# DrumidySynth.net
KiCad netlist of a schematic drawn in EAGLE
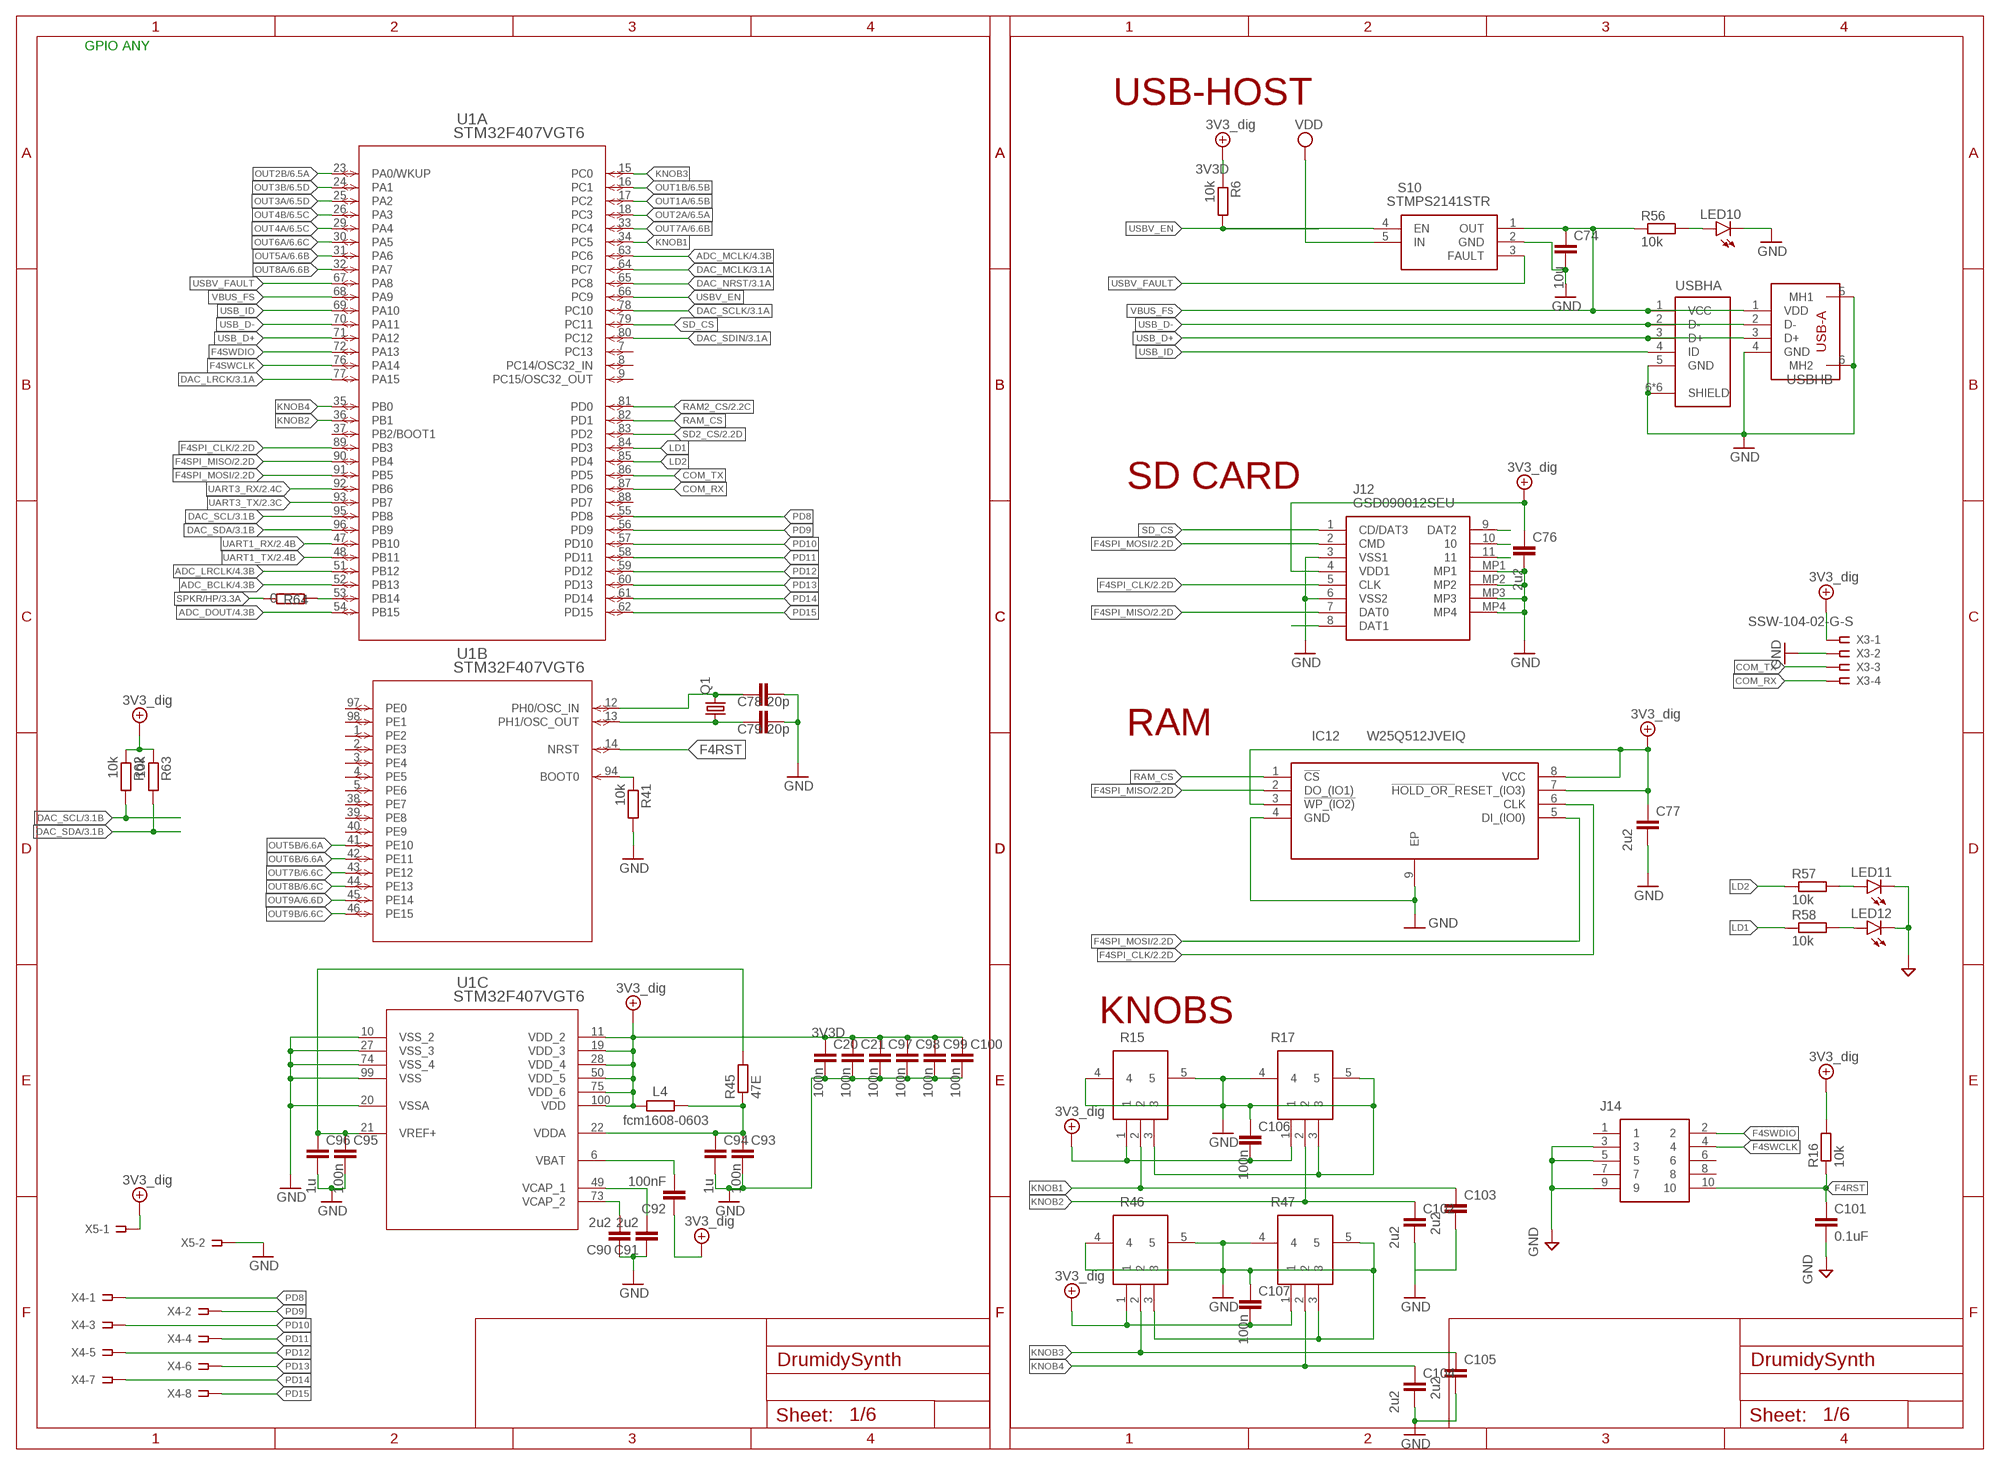
[diagram p0: schematic, sheet 1]
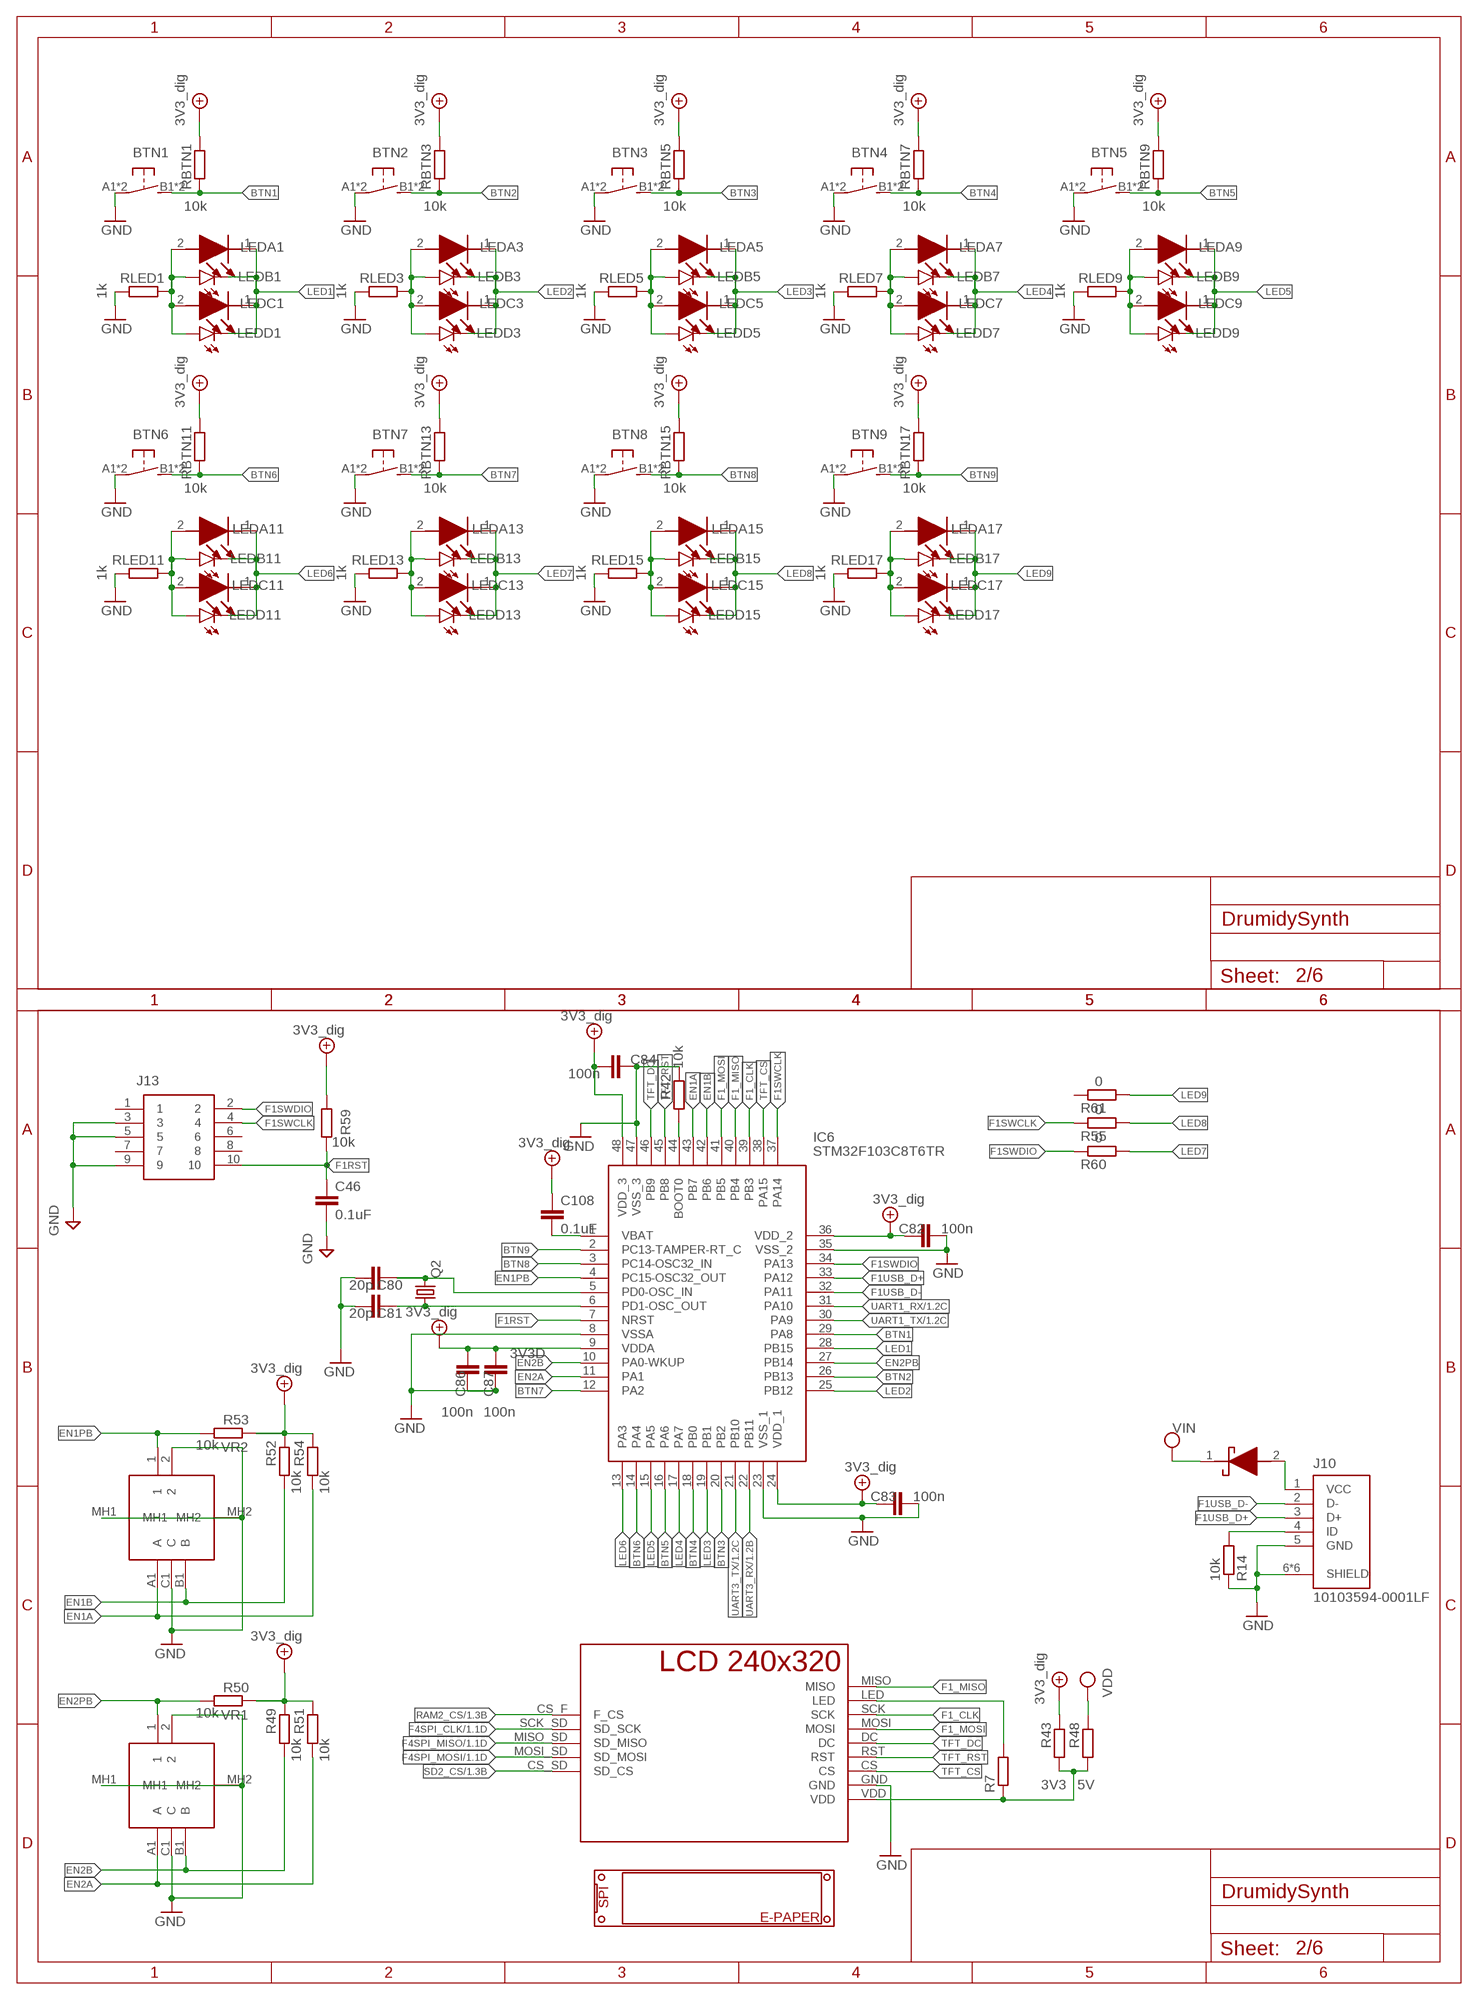
[diagram p1: schematic, sheet 2]
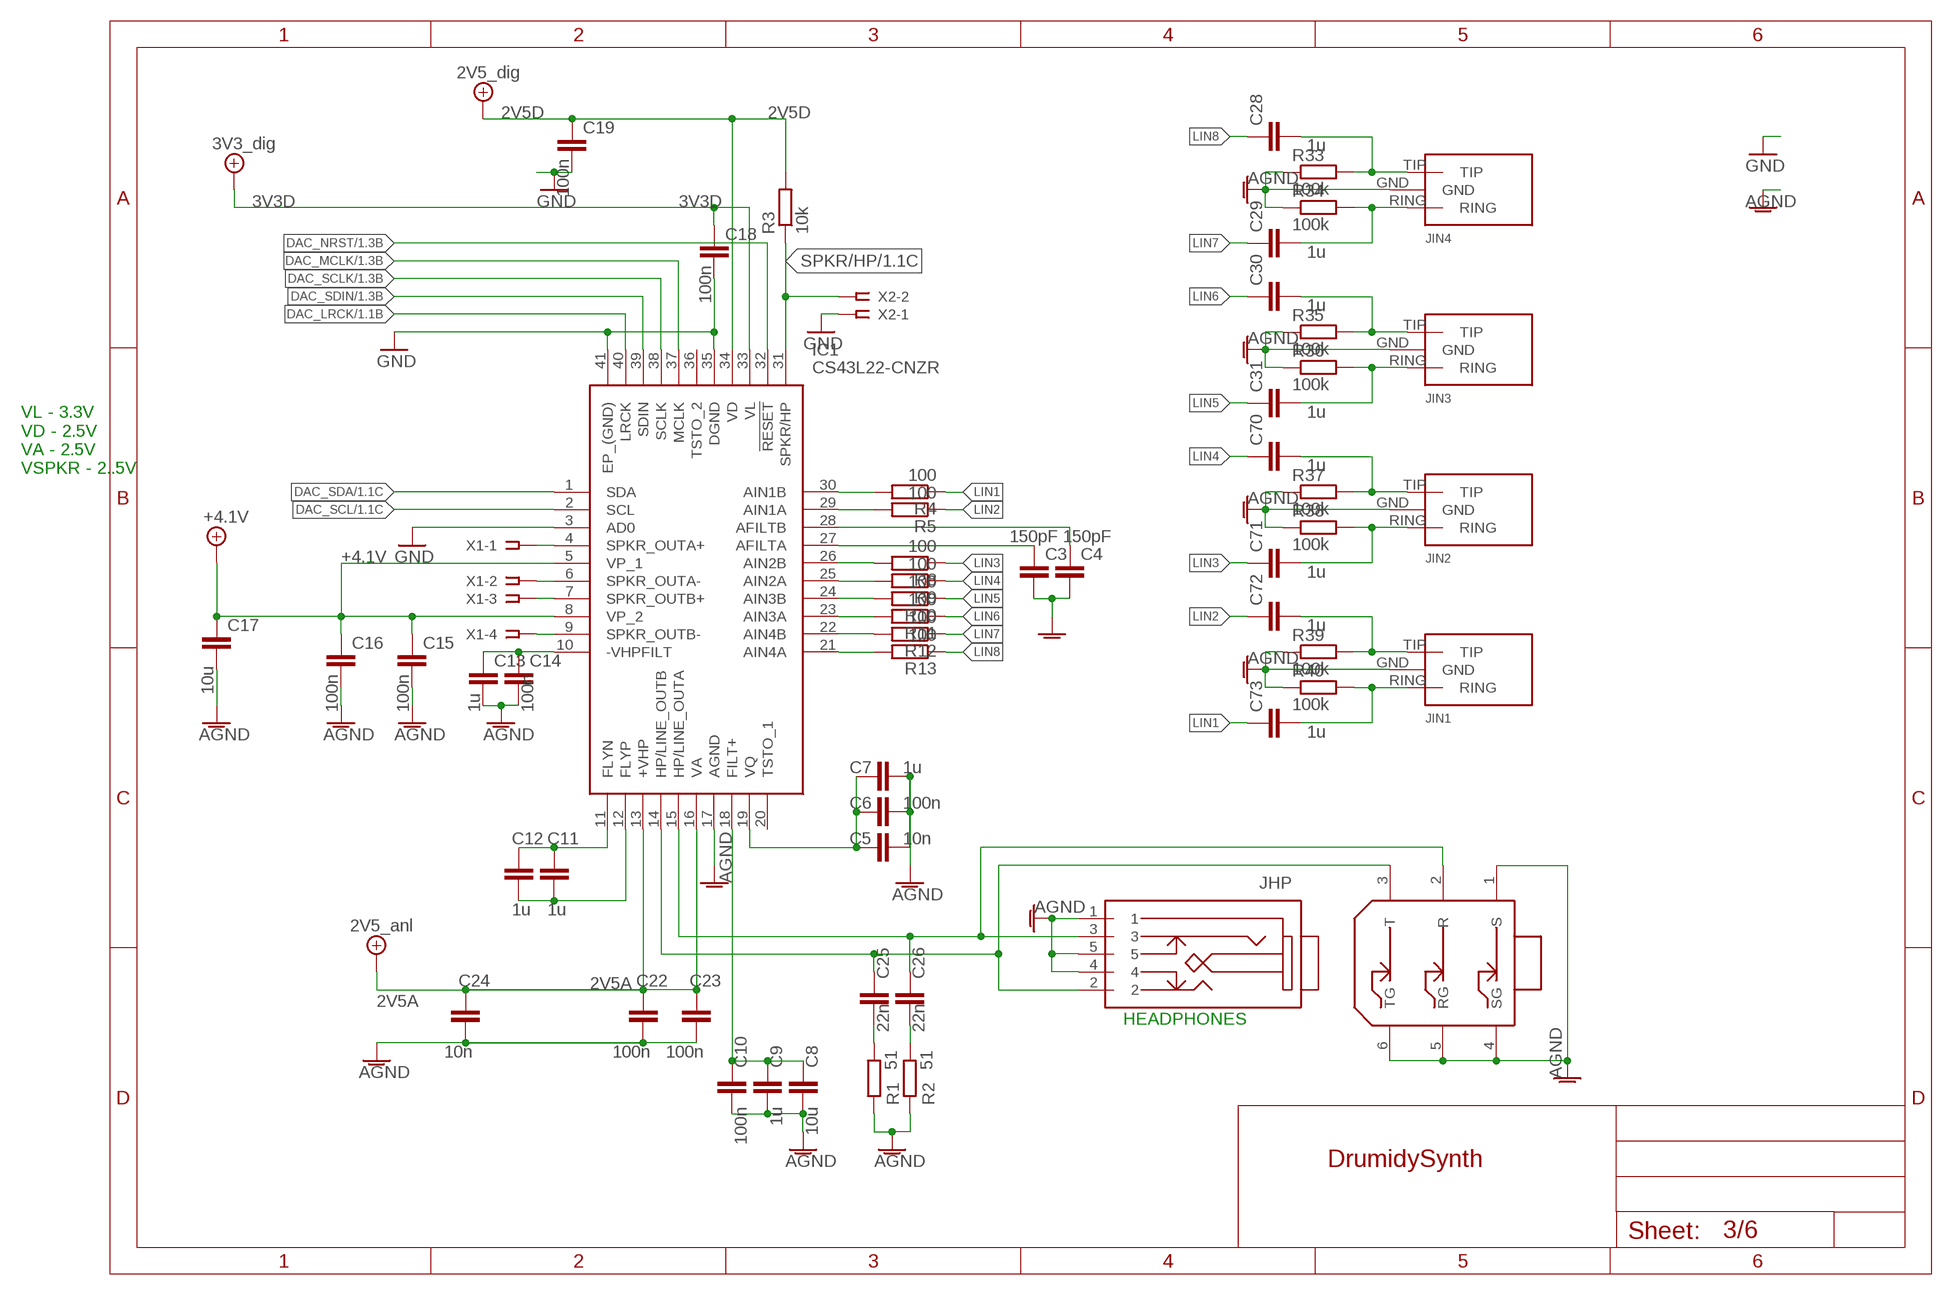
[diagram p2: schematic, sheet 3]
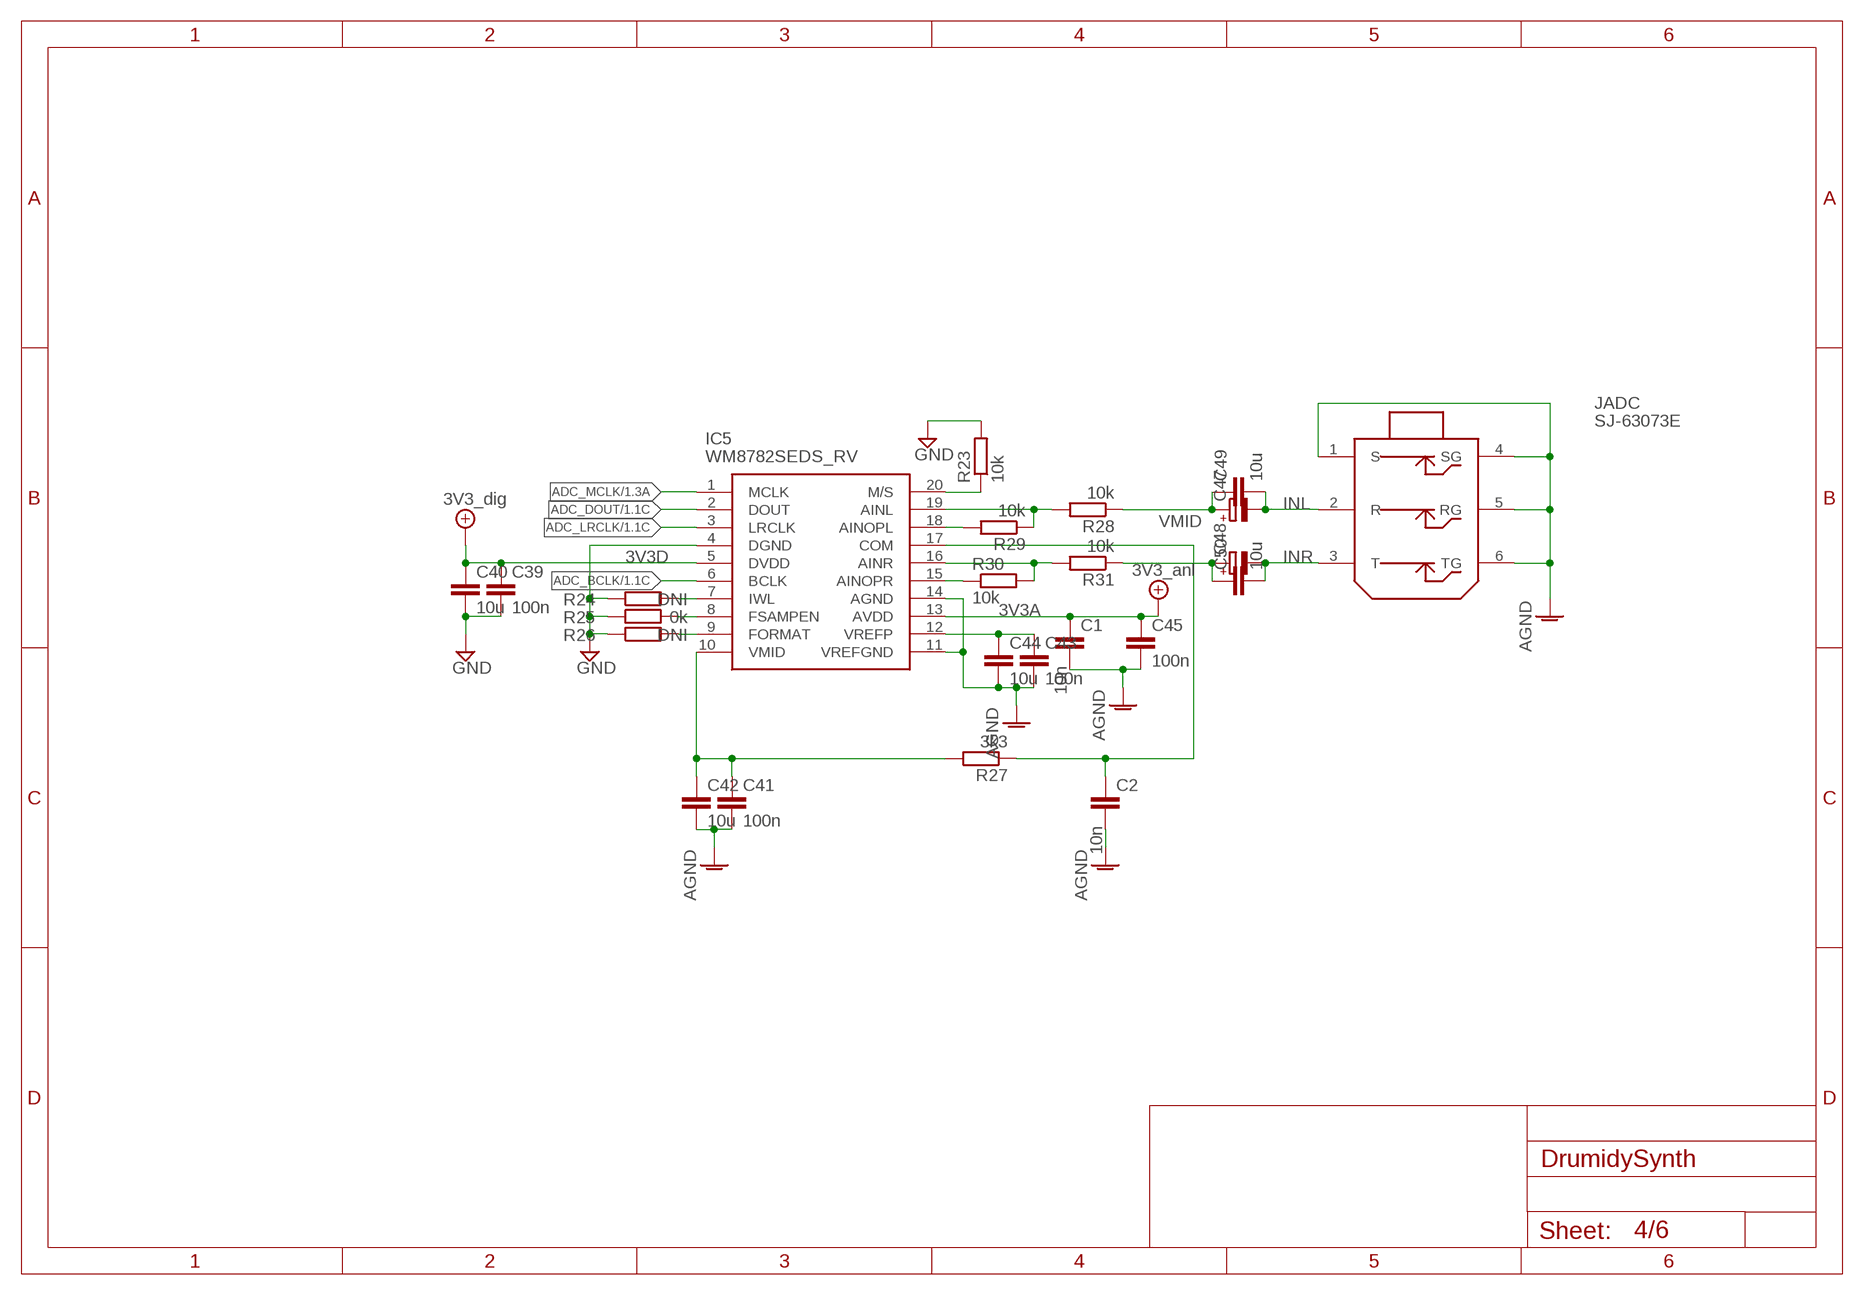
[diagram p3: schematic, sheet 4]
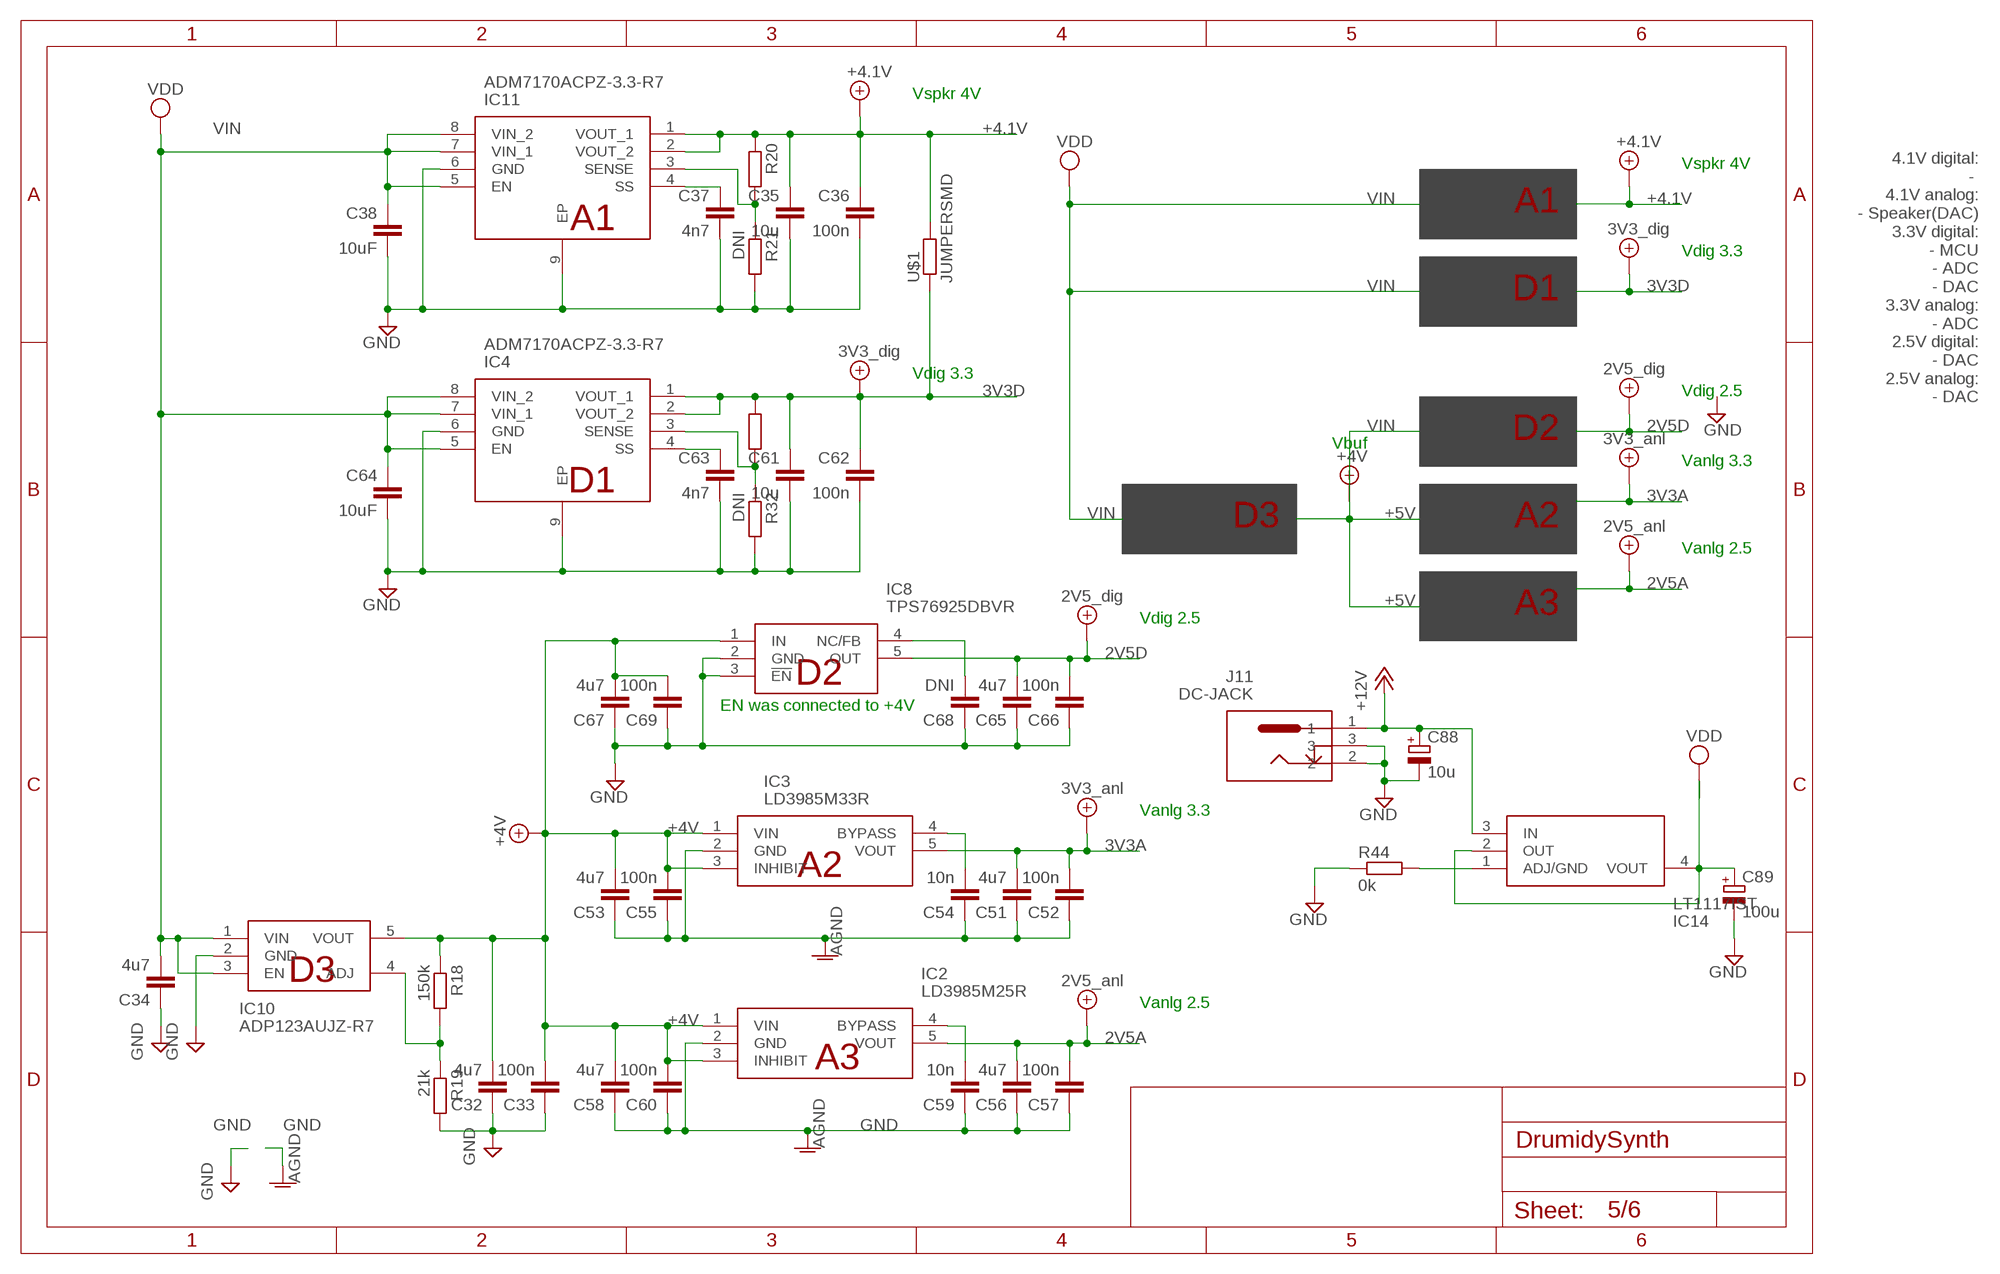
[diagram p4: schematic, sheet 5]
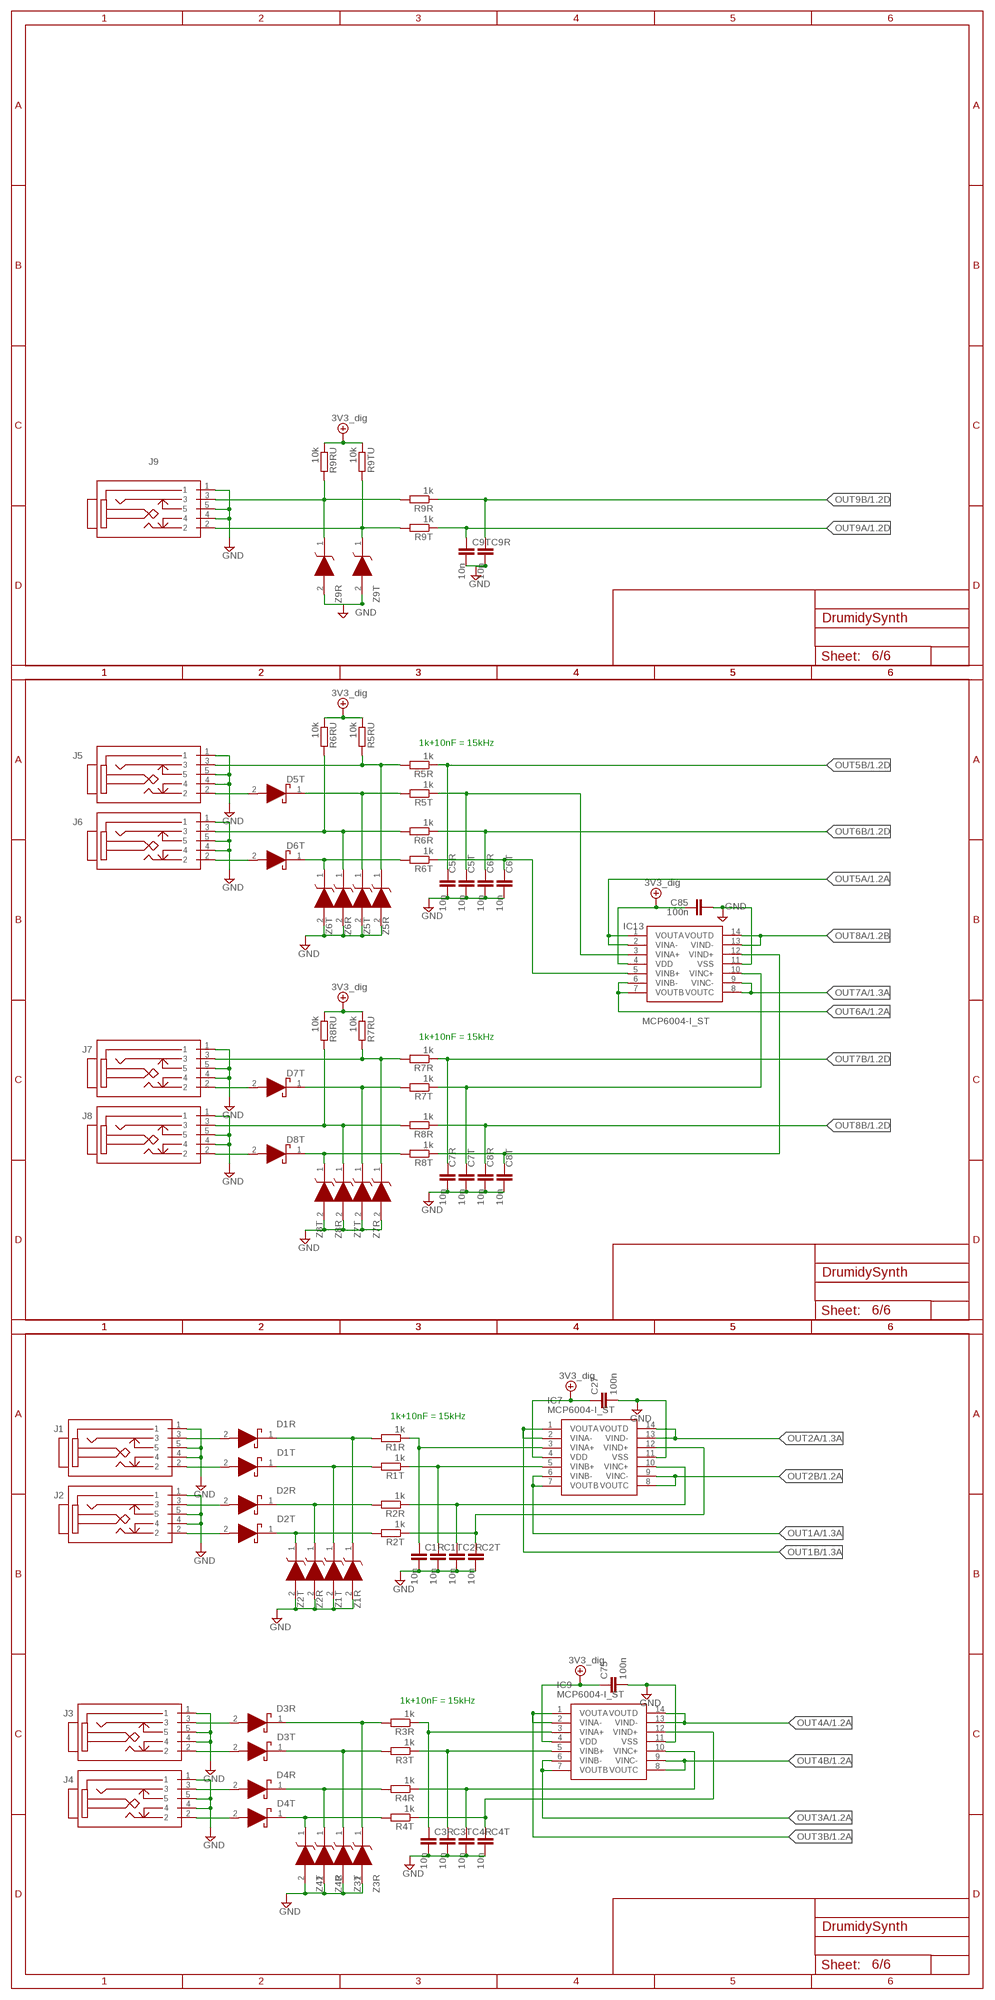
[diagram p5: schematic, sheet 6]

(export (version "E")
  (design (tool "Eeschema 10.0.6"))
  (components
    (comp (ref "C20")
      (value "100n")
      (footprint "eagle-import:C0603K")
      (libsource (lib "eagle-import") (part "C-EUC0603K"))
    )
    (comp (ref "C21")
      (value "100n")
      (footprint "eagle-import:C0603K")
      (libsource (lib "eagle-import") (part "C-EUC0603K"))
    )
    (comp (ref "C74")
      (value "10u")
      (footprint "eagle-import:C0805K")
      (libsource (lib "eagle-import") (part "C-EUC0805K"))
    )
    (comp (ref "C76")
      (value "2u2")
      (footprint "eagle-import:C0805K")
      (libsource (lib "eagle-import") (part "C-EUC0805K"))
    )
    (comp (ref "C77")
      (value "2u2")
      (footprint "eagle-import:C0805K")
      (libsource (lib "eagle-import") (part "C-EUC0805K"))
    )
    (comp (ref "C78")
      (value "20p")
      (footprint "eagle-import:C0402K")
      (libsource (lib "eagle-import") (part "C-EUC0402K"))
    )
    (comp (ref "C79")
      (value "20p")
      (footprint "eagle-import:C0402K")
      (libsource (lib "eagle-import") (part "C-EUC0402K"))
    )
    (comp (ref "C90")
      (value "2u2")
      (footprint "eagle-import:C0603K")
      (libsource (lib "eagle-import") (part "C-EUC0603K"))
    )
    (comp (ref "C91")
      (value "2u2")
      (footprint "eagle-import:C0603K")
      (libsource (lib "eagle-import") (part "C-EUC0603K"))
    )
    (comp (ref "C92")
      (value "100nF")
      (footprint "eagle-import:C0603K")
      (libsource (lib "eagle-import") (part "C-EUC0603K"))
    )
    (comp (ref "C93")
      (value "100n")
      (footprint "eagle-import:C0603K")
      (libsource (lib "eagle-import") (part "C-EUC0603K"))
    )
    (comp (ref "C94")
      (value "1u")
      (footprint "eagle-import:C0805K")
      (libsource (lib "eagle-import") (part "C-EUC0805K"))
    )
    (comp (ref "C95")
      (value "100n")
      (footprint "eagle-import:C0603K")
      (libsource (lib "eagle-import") (part "C-EUC0603K"))
    )
    (comp (ref "C96")
      (value "1u")
      (footprint "eagle-import:C0805K")
      (libsource (lib "eagle-import") (part "C-EUC0805K"))
    )
    (comp (ref "C97")
      (value "100n")
      (footprint "eagle-import:C0603K")
      (libsource (lib "eagle-import") (part "C-EUC0603K"))
    )
    (comp (ref "C98")
      (value "100n")
      (footprint "eagle-import:C0603K")
      (libsource (lib "eagle-import") (part "C-EUC0603K"))
    )
    (comp (ref "C99")
      (value "100n")
      (footprint "eagle-import:C0603K")
      (libsource (lib "eagle-import") (part "C-EUC0603K"))
    )
    (comp (ref "C100")
      (value "100n")
      (footprint "eagle-import:C0603K")
      (libsource (lib "eagle-import") (part "C-EUC0603K"))
    )
    (comp (ref "C101")
      (value "0.1uF")
      (footprint "eagle-import:C0402")
      (libsource (lib "eagle-import") (part "C-EUC0402"))
    )
    (comp (ref "C102")
      (value "2u2")
      (footprint "eagle-import:C0805K")
      (libsource (lib "eagle-import") (part "C-EUC0805K"))
    )
    (comp (ref "C103")
      (value "2u2")
      (footprint "eagle-import:C0805K")
      (libsource (lib "eagle-import") (part "C-EUC0805K"))
    )
    (comp (ref "C104")
      (value "2u2")
      (footprint "eagle-import:C0805K")
      (libsource (lib "eagle-import") (part "C-EUC0805K"))
    )
    (comp (ref "C105")
      (value "2u2")
      (footprint "eagle-import:C0805K")
      (libsource (lib "eagle-import") (part "C-EUC0805K"))
    )
    (comp (ref "C106")
      (value "100n")
      (footprint "eagle-import:C0603K")
      (libsource (lib "eagle-import") (part "C-EUC0603K"))
    )
    (comp (ref "C107")
      (value "100n")
      (footprint "eagle-import:C0603K")
      (libsource (lib "eagle-import") (part "C-EUC0603K"))
    )
    (comp (ref "IC12")
      (value "W25Q512JVEIQ")
      (footprint "eagle-import:SON127P800X600X80-9N")
      (fields (field (name "MOUSER_PART_NUMBER") "454-W25Q512JVEIQ"))
      (libsource (lib "eagle-import") (part "W25Q512JVEIQ"))
    )
    (comp (ref "J12")
      (value "GSD090012SEU")
      (footprint "eagle-import:GSD090012SEU")
      (fields (field (name "RS_PART_NUMBER") "2208512"))
      (libsource (lib "eagle-import") (part "GSD090012SEU"))
    )
    (comp (ref "J14")
      (value "FTSH-105-01-F-DV-K-A-P-TR")
      (footprint "eagle-import:FTSH-105-XX-YYY-DV-K-A-P-TR")
      (fields (field (name "MOUSER_PART_NUMBER") "200-FTSH1051FDVKAPTR"))
      (libsource (lib "eagle-import") (part "FTSH-105-01-F-DV-K-A-P-TR"))
    )
    (comp (ref "L4")
      (value "fcm1608-0603")
      (footprint "eagle-import:R0603")
      (libsource (lib "eagle-import") (part "R-EU_R0603"))
    )
    (comp (ref "LED10")
      (value "LEDCHIP-LED0603")
      (footprint "eagle-import:CHIP-LED0603")
      (libsource (lib "eagle-import") (part "LEDCHIP-LED0603"))
    )
    (comp (ref "LED11")
      (value "LEDCHIP-LED0603")
      (footprint "eagle-import:CHIP-LED0603")
      (libsource (lib "eagle-import") (part "LEDCHIP-LED0603"))
    )
    (comp (ref "LED12")
      (value "LEDCHIP-LED0603")
      (footprint "eagle-import:CHIP-LED0603")
      (libsource (lib "eagle-import") (part "LEDCHIP-LED0603"))
    )
    (comp (ref "Q1")
      (value "CRYSTALHC49S")
      (footprint "eagle-import:HC49_S")
      (libsource (lib "eagle-import") (part "CRYSTALHC49S"))
    )
    (comp (ref "R6")
      (value "10k")
      (footprint "eagle-import:R0603")
      (libsource (lib "eagle-import") (part "R-EU_R0603"))
    )
    (comp (ref "R15")
      (value "PTV09A-4025U-B103")
      (footprint "eagle-import:PTV09A4020FB103")
      (libsource (lib "eagle-import") (part "PTV09A-4025U-B103"))
    )
    (comp (ref "R16")
      (value "10k")
      (footprint "eagle-import:R0603")
      (libsource (lib "eagle-import") (part "R-EU_R0603"))
    )
    (comp (ref "R17")
      (value "PTV09A-4025U-B103")
      (footprint "eagle-import:PTV09A4020FB103")
      (libsource (lib "eagle-import") (part "PTV09A-4025U-B103"))
    )
    (comp (ref "R41")
      (value "10k")
      (footprint "eagle-import:R0603")
      (libsource (lib "eagle-import") (part "R-EU_R0603"))
    )
    (comp (ref "R45")
      (value "47E")
      (footprint "eagle-import:R0603")
      (libsource (lib "eagle-import") (part "R-EU_R0603"))
    )
    (comp (ref "R46")
      (value "PTV09A-4025U-B103")
      (footprint "eagle-import:PTV09A4020FB103")
      (libsource (lib "eagle-import") (part "PTV09A-4025U-B103"))
    )
    (comp (ref "R47")
      (value "PTV09A-4025U-B103")
      (footprint "eagle-import:PTV09A4020FB103")
      (libsource (lib "eagle-import") (part "PTV09A-4025U-B103"))
    )
    (comp (ref "R56")
      (value "10k")
      (footprint "eagle-import:R0603")
      (libsource (lib "eagle-import") (part "R-EU_R0603"))
    )
    (comp (ref "R57")
      (value "10k")
      (footprint "eagle-import:R0603")
      (libsource (lib "eagle-import") (part "R-EU_R0603"))
    )
    (comp (ref "R58")
      (value "10k")
      (footprint "eagle-import:R0603")
      (libsource (lib "eagle-import") (part "R-EU_R0603"))
    )
    (comp (ref "R62")
      (value "10k")
      (footprint "eagle-import:R0603")
      (libsource (lib "eagle-import") (part "R-EU_R0603"))
    )
    (comp (ref "R63")
      (value "10k")
      (footprint "eagle-import:R0603")
      (libsource (lib "eagle-import") (part "R-EU_R0603"))
    )
    (comp (ref "R64")
      (value "0")
      (footprint "eagle-import:R0603")
      (libsource (lib "eagle-import") (part "R-EU_R0603"))
    )
    (comp (ref "S10")
      (value "STMPS2141STR")
      (footprint "eagle-import:SOT95P280X145-5N")
      (fields (field (name "RS_PART_NUMBER") "8805406P"))
      (libsource (lib "eagle-import") (part "STMPS2141STR"))
    )
    (comp (ref "U1")
      (value "STM32F407VGT6")
      (footprint "eagle-import:LQFP100-14X14MM")
      (fields (field (name "COPYRIGHT") "Copyright (C) 2022 Ultra Librarian. All rights reserved."))
      (libsource (lib "eagle-import") (part "STM32F407VGT6"))
    )
    (comp (ref "USBHA")
      (value "10103594-0001LF")
      (footprint "eagle-import:AMPHENOL_10103594-0001LF")
      (fields (field (name "DIGI-KEY_PART_NUMBER") "609-4050-1-ND") (field (name "MF") "Amphenol ICC"))
      (libsource (lib "eagle-import") (part "10103594-0001LF"))
    )
    (comp (ref "USBHB")
      (value "USB-A(292303-7)")
      (footprint "eagle-import:2923037")
      (fields (field (name "MANUFACTURER_PART_NUMBER") "292303-7") (field (name "RS_PART_NUMBER") "9097864"))
      (libsource (lib "eagle-import") (part "USB-A(292303-7)"))
    )
    (comp (ref "X3")
      (value "SSW-104-02-G-S")
      (footprint "eagle-import:SSW-104-02-G-S")
      (fields (field (name "MF") "Samtec Inc."))
      (libsource (lib "eagle-import") (part "SSW-104-02-G-S"))
    )
    (comp (ref "X4")
      (value "SSW-104-02-G-D")
      (footprint "eagle-import:SSW-104-02-G-D")
      (fields (field (name "MF") "Samtec Inc."))
      (libsource (lib "eagle-import") (part "SSW-104-02-G-D"))
    )
    (comp (ref "X5")
      (value "SSW-102-02-G-S")
      (footprint "eagle-import:SSW-102-02-G-S")
      (fields (field (name "MF") "Samtec Inc."))
      (libsource (lib "eagle-import") (part "SSW-102-02-G-S"))
    )
    (comp (ref "C3")
      (value "150pF")
      (footprint "eagle-import:C0402K")
      (libsource (lib "eagle-import") (part "C-EUC0402K"))
    )
    (comp (ref "C4")
      (value "150pF")
      (footprint "eagle-import:C0402K")
      (libsource (lib "eagle-import") (part "C-EUC0402K"))
    )
    (comp (ref "C5")
      (value "10n")
      (footprint "eagle-import:C0402K")
      (libsource (lib "eagle-import") (part "C-EUC0402K"))
    )
    (comp (ref "C6")
      (value "100n")
      (footprint "eagle-import:C0603K")
      (libsource (lib "eagle-import") (part "C-EUC0603K"))
    )
    (comp (ref "C7")
      (value "1u")
      (footprint "eagle-import:C0603K")
      (libsource (lib "eagle-import") (part "C-EUC0603K"))
    )
    (comp (ref "C8")
      (value "10u")
      (footprint "eagle-import:C0805K")
      (libsource (lib "eagle-import") (part "C-EUC0805K"))
    )
    (comp (ref "C9")
      (value "1u")
      (footprint "eagle-import:C0603K")
      (libsource (lib "eagle-import") (part "C-EUC0603K"))
    )
    (comp (ref "C10")
      (value "100n")
      (footprint "eagle-import:C0603K")
      (libsource (lib "eagle-import") (part "C-EUC0603K"))
    )
    (comp (ref "C11")
      (value "1u")
      (footprint "eagle-import:C0603K")
      (libsource (lib "eagle-import") (part "C-EUC0603K"))
    )
    (comp (ref "C12")
      (value "1u")
      (footprint "eagle-import:C0603K")
      (libsource (lib "eagle-import") (part "C-EUC0603K"))
    )
    (comp (ref "C13")
      (value "1u")
      (footprint "eagle-import:C0603K")
      (libsource (lib "eagle-import") (part "C-EUC0603K"))
    )
    (comp (ref "C14")
      (value "100n")
      (footprint "eagle-import:C0603K")
      (libsource (lib "eagle-import") (part "C-EUC0603K"))
    )
    (comp (ref "C15")
      (value "100n")
      (footprint "eagle-import:C0603K")
      (libsource (lib "eagle-import") (part "C-EUC0603K"))
    )
    (comp (ref "C16")
      (value "100n")
      (footprint "eagle-import:C0603K")
      (libsource (lib "eagle-import") (part "C-EUC0603K"))
    )
    (comp (ref "C17")
      (value "10u")
      (footprint "eagle-import:C0805K")
      (libsource (lib "eagle-import") (part "C-EUC0805K"))
    )
    (comp (ref "C18")
      (value "100n")
      (footprint "eagle-import:C0603K")
      (libsource (lib "eagle-import") (part "C-EUC0603K"))
    )
    (comp (ref "C19")
      (value "100n")
      (footprint "eagle-import:C0603K")
      (libsource (lib "eagle-import") (part "C-EUC0603K"))
    )
    (comp (ref "C22")
      (value "100n")
      (footprint "eagle-import:C0603K")
      (libsource (lib "eagle-import") (part "C-EUC0603K"))
    )
    (comp (ref "C23")
      (value "100n")
      (footprint "eagle-import:C0603K")
      (libsource (lib "eagle-import") (part "C-EUC0603K"))
    )
    (comp (ref "C24")
      (value "10n")
      (footprint "eagle-import:C0402K")
      (libsource (lib "eagle-import") (part "C-EUC0402K"))
    )
    (comp (ref "C25")
      (value "22n")
      (footprint "eagle-import:C0603K")
      (libsource (lib "eagle-import") (part "C-EUC0603K"))
    )
    (comp (ref "C26")
      (value "22n")
      (footprint "eagle-import:C0603K")
      (libsource (lib "eagle-import") (part "C-EUC0603K"))
    )
    (comp (ref "C28")
      (value "1u")
      (footprint "eagle-import:C0603K")
      (libsource (lib "eagle-import") (part "C-EUC0603K"))
    )
    (comp (ref "C29")
      (value "1u")
      (footprint "eagle-import:C0603K")
      (libsource (lib "eagle-import") (part "C-EUC0603K"))
    )
    (comp (ref "C30")
      (value "1u")
      (footprint "eagle-import:C0603K")
      (libsource (lib "eagle-import") (part "C-EUC0603K"))
    )
    (comp (ref "C31")
      (value "1u")
      (footprint "eagle-import:C0603K")
      (libsource (lib "eagle-import") (part "C-EUC0603K"))
    )
    (comp (ref "C70")
      (value "1u")
      (footprint "eagle-import:C0603K")
      (libsource (lib "eagle-import") (part "C-EUC0603K"))
    )
    (comp (ref "C71")
      (value "1u")
      (footprint "eagle-import:C0603K")
      (libsource (lib "eagle-import") (part "C-EUC0603K"))
    )
    (comp (ref "C72")
      (value "1u")
      (footprint "eagle-import:C0603K")
      (libsource (lib "eagle-import") (part "C-EUC0603K"))
    )
    (comp (ref "C73")
      (value "1u")
      (footprint "eagle-import:C0603K")
      (libsource (lib "eagle-import") (part "C-EUC0603K"))
    )
    (comp (ref "IC1")
      (value "CS43L22-CNZR")
      (footprint "eagle-import:QFN50P600X600X100-41N")
      (libsource (lib "eagle-import") (part "CS43L22-CNZR"))
    )
    (comp (ref "JHP")
      (value "35RAPC2AVN4")
      (footprint "eagle-import:35RAPC2AVN4")
      (libsource (lib "eagle-import") (part "35RAPC2AVN4"))
    )
    (comp (ref "JIN1")
      (value "JACK35VERT")
      (footprint "eagle-import:JACK35VERT")
      (libsource (lib "eagle-import") (part "JACK35VERT"))
    )
    (comp (ref "JIN2")
      (value "JACK35VERT")
      (footprint "eagle-import:JACK35VERT")
      (libsource (lib "eagle-import") (part "JACK35VERT"))
    )
    (comp (ref "JIN3")
      (value "JACK35VERT")
      (footprint "eagle-import:JACK35VERT")
      (libsource (lib "eagle-import") (part "JACK35VERT"))
    )
    (comp (ref "JIN4")
      (value "JACK35VERT")
      (footprint "eagle-import:JACK35VERT")
      (libsource (lib "eagle-import") (part "JACK35VERT"))
    )
    (comp (ref "JOUT")
      (value "SJ-63073E")
      (footprint "eagle-import:SJ63073E")
      (fields (field (name "MOUSER_PART_NUMBER") "490-SJ-63073E"))
      (libsource (lib "eagle-import") (part "SJ-63073E"))
    )
    (comp (ref "R1")
      (value "51")
      (footprint "eagle-import:R0603")
      (libsource (lib "eagle-import") (part "R-EU_R0603"))
    )
    (comp (ref "R2")
      (value "51")
      (footprint "eagle-import:R0603")
      (libsource (lib "eagle-import") (part "R-EU_R0603"))
    )
    (comp (ref "R3")
      (value "10k")
      (footprint "eagle-import:R0603")
      (libsource (lib "eagle-import") (part "R-EU_R0603"))
    )
    (comp (ref "R4")
      (value "100")
      (footprint "eagle-import:R0603")
      (libsource (lib "eagle-import") (part "R-EU_R0603"))
    )
    (comp (ref "R5")
      (value "100")
      (footprint "eagle-import:R0603")
      (libsource (lib "eagle-import") (part "R-EU_R0603"))
    )
    (comp (ref "R8")
      (value "100")
      (footprint "eagle-import:R0603")
      (libsource (lib "eagle-import") (part "R-EU_R0603"))
    )
    (comp (ref "R9")
      (value "100")
      (footprint "eagle-import:R0603")
      (libsource (lib "eagle-import") (part "R-EU_R0603"))
    )
    (comp (ref "R10")
      (value "100")
      (footprint "eagle-import:R0603")
      (libsource (lib "eagle-import") (part "R-EU_R0603"))
    )
    (comp (ref "R11")
      (value "100")
      (footprint "eagle-import:R0603")
      (libsource (lib "eagle-import") (part "R-EU_R0603"))
    )
    (comp (ref "R12")
      (value "100")
      (footprint "eagle-import:R0603")
      (libsource (lib "eagle-import") (part "R-EU_R0603"))
    )
    (comp (ref "R13")
      (value "100")
      (footprint "eagle-import:R0603")
      (libsource (lib "eagle-import") (part "R-EU_R0603"))
    )
    (comp (ref "R33")
      (value "100k")
      (footprint "eagle-import:R0603")
      (libsource (lib "eagle-import") (part "R-EU_R0603"))
    )
    (comp (ref "R34")
      (value "100k")
      (footprint "eagle-import:R0603")
      (libsource (lib "eagle-import") (part "R-EU_R0603"))
    )
    (comp (ref "R35")
      (value "100k")
      (footprint "eagle-import:R0603")
      (libsource (lib "eagle-import") (part "R-EU_R0603"))
    )
    (comp (ref "R36")
      (value "100k")
      (footprint "eagle-import:R0603")
      (libsource (lib "eagle-import") (part "R-EU_R0603"))
    )
    (comp (ref "R37")
      (value "100k")
      (footprint "eagle-import:R0603")
      (libsource (lib "eagle-import") (part "R-EU_R0603"))
    )
    (comp (ref "R38")
      (value "100k")
      (footprint "eagle-import:R0603")
      (libsource (lib "eagle-import") (part "R-EU_R0603"))
    )
    (comp (ref "R39")
      (value "100k")
      (footprint "eagle-import:R0603")
      (libsource (lib "eagle-import") (part "R-EU_R0603"))
    )
    (comp (ref "R40")
      (value "100k")
      (footprint "eagle-import:R0603")
      (libsource (lib "eagle-import") (part "R-EU_R0603"))
    )
    (comp (ref "X1")
      (value "SSW-104-02-G-S")
      (footprint "eagle-import:SSW-104-02-G-S")
      (fields (field (name "MF") "Samtec Inc."))
      (libsource (lib "eagle-import") (part "SSW-104-02-G-S"))
    )
    (comp (ref "X2")
      (value "SSW-102-02-G-S")
      (footprint "eagle-import:SSW-102-02-G-S")
      (fields (field (name "MF") "Samtec Inc."))
      (libsource (lib "eagle-import") (part "SSW-102-02-G-S"))
    )
    (comp (ref "C32")
      (value "4u7")
      (footprint "eagle-import:C0603K")
      (libsource (lib "eagle-import") (part "C-EUC0603K"))
    )
    (comp (ref "C33")
      (value "100n")
      (footprint "eagle-import:C0402")
      (libsource (lib "eagle-import") (part "C-EUC0402"))
    )
    (comp (ref "C34")
      (value "4u7")
      (footprint "eagle-import:C0603K")
      (libsource (lib "eagle-import") (part "C-EUC0603K"))
    )
    (comp (ref "C35")
      (value "10u")
      (footprint "eagle-import:C0603")
      (libsource (lib "eagle-import") (part "C-EUC0603"))
    )
    (comp (ref "C36")
      (value "100n")
      (footprint "eagle-import:C0402K")
      (libsource (lib "eagle-import") (part "C-EUC0402K"))
    )
    (comp (ref "C37")
      (value "4n7")
      (footprint "eagle-import:C0402K")
      (libsource (lib "eagle-import") (part "C-EUC0402K"))
    )
    (comp (ref "C38")
      (value "10uF")
      (footprint "eagle-import:C0603")
      (libsource (lib "eagle-import") (part "C-EUC0603"))
    )
    (comp (ref "C51")
      (value "4u7")
      (footprint "eagle-import:C0603K")
      (libsource (lib "eagle-import") (part "C-EUC0603K"))
    )
    (comp (ref "C52")
      (value "100n")
      (footprint "eagle-import:C0402")
      (libsource (lib "eagle-import") (part "C-EUC0402"))
    )
    (comp (ref "C53")
      (value "4u7")
      (footprint "eagle-import:C0603K")
      (libsource (lib "eagle-import") (part "C-EUC0603K"))
    )
    (comp (ref "C54")
      (value "10n")
      (footprint "eagle-import:C0402K")
      (libsource (lib "eagle-import") (part "C-EUC0402K"))
    )
    (comp (ref "C55")
      (value "100n")
      (footprint "eagle-import:C0402")
      (libsource (lib "eagle-import") (part "C-EUC0402"))
    )
    (comp (ref "C56")
      (value "4u7")
      (footprint "eagle-import:C0603K")
      (libsource (lib "eagle-import") (part "C-EUC0603K"))
    )
    (comp (ref "C57")
      (value "100n")
      (footprint "eagle-import:C0402")
      (libsource (lib "eagle-import") (part "C-EUC0402"))
    )
    (comp (ref "C58")
      (value "4u7")
      (footprint "eagle-import:C0603K")
      (libsource (lib "eagle-import") (part "C-EUC0603K"))
    )
    (comp (ref "C59")
      (value "10n")
      (footprint "eagle-import:C0402K")
      (libsource (lib "eagle-import") (part "C-EUC0402K"))
    )
    (comp (ref "C60")
      (value "100n")
      (footprint "eagle-import:C0402")
      (libsource (lib "eagle-import") (part "C-EUC0402"))
    )
    (comp (ref "C61")
      (value "10u")
      (footprint "eagle-import:C0603")
      (libsource (lib "eagle-import") (part "C-EUC0603"))
    )
    (comp (ref "C62")
      (value "100n")
      (footprint "eagle-import:C0402K")
      (libsource (lib "eagle-import") (part "C-EUC0402K"))
    )
    (comp (ref "C63")
      (value "4n7")
      (footprint "eagle-import:C0402K")
      (libsource (lib "eagle-import") (part "C-EUC0402K"))
    )
    (comp (ref "C64")
      (value "10uF")
      (footprint "eagle-import:C0603")
      (libsource (lib "eagle-import") (part "C-EUC0603"))
    )
    (comp (ref "C65")
      (value "4u7")
      (footprint "eagle-import:C0603K")
      (libsource (lib "eagle-import") (part "C-EUC0603K"))
    )
    (comp (ref "C66")
      (value "100n")
      (footprint "eagle-import:C0402")
      (libsource (lib "eagle-import") (part "C-EUC0402"))
    )
    (comp (ref "C67")
      (value "4u7")
      (footprint "eagle-import:C0603K")
      (libsource (lib "eagle-import") (part "C-EUC0603K"))
    )
    (comp (ref "C68")
      (value "DNI")
      (footprint "eagle-import:C0402K")
      (libsource (lib "eagle-import") (part "C-EUC0402K"))
    )
    (comp (ref "C69")
      (value "100n")
      (footprint "eagle-import:C0402")
      (libsource (lib "eagle-import") (part "C-EUC0402"))
    )
    (comp (ref "C88")
      (value "10u")
      (footprint "eagle-import:E2,5-6")
      (libsource (lib "eagle-import") (part "CPOL-EUE2.5-6"))
    )
    (comp (ref "C89")
      (value "100u")
      (footprint "eagle-import:E2,5-6")
      (libsource (lib "eagle-import") (part "CPOL-EUE2.5-6"))
    )
    (comp (ref "IC2")
      (value "LD3985M25R")
      (footprint "eagle-import:SOT95P280X145-5N")
      (fields (field (name "RS_PART_NUMBER") "6868809P"))
      (libsource (lib "eagle-import") (part "LD3985M25R"))
    )
    (comp (ref "IC3")
      (value "LD3985M33R")
      (footprint "eagle-import:SOT95P280X145-5N")
      (fields (field (name "RS_PART_NUMBER") "6868802P"))
      (libsource (lib "eagle-import") (part "LD3985M33R"))
    )
    (comp (ref "IC4")
      (value "ADM7170ACPZ-3.3-R7")
      (footprint "eagle-import:SON50P300X300X80-9N")
      (fields (field (name "MOUSER_PART_NUMBER") "584-ADM7170ACPZ3.3R7"))
      (libsource (lib "eagle-import") (part "ADM7170ACPZ-3.3-R7"))
    )
    (comp (ref "IC8")
      (value "TPS76925DBVR")
      (footprint "eagle-import:SOT95P280X145-5N")
      (libsource (lib "eagle-import") (part "TPS76925DBVR"))
    )
    (comp (ref "IC10")
      (value "ADP123AUJZ-R7")
      (footprint "eagle-import:SOT95P280X100-5N")
      (fields (field (name "MOUSER_PART_NUMBER") "584-ADP123AUJZ-R7"))
      (libsource (lib "eagle-import") (part "ADP123AUJZ-R7"))
    )
    (comp (ref "IC11")
      (value "ADM7170ACPZ-3.3-R7")
      (footprint "eagle-import:SON50P300X300X80-9N")
      (fields (field (name "MOUSER_PART_NUMBER") "584-ADM7170ACPZ3.3R7"))
      (libsource (lib "eagle-import") (part "ADM7170ACPZ-3.3-R7"))
    )
    (comp (ref "IC14")
      (value "LT1117IST")
      (footprint "eagle-import:SOT230P700X180-4N")
      (fields
        (field (name "MANUFACTURER_PART_NUMBER") "LT1117IST-5#PBF")
        (field (name "RS_PART_NUMBER") "8846936P")
      )
      (libsource (lib "eagle-import") (part "LT1117IST"))
    )
    (comp (ref "J11")
      (value "DC-JACK")
      (footprint "eagle-import:PRT00119")
      (fields (field (name "MANUFACTURER_PART_NUMBER") "PRT-00119"))
      (libsource (lib "eagle-import") (part "DC-JACK"))
    )
    (comp (ref "R18")
      (value "150k")
      (footprint "eagle-import:R0603")
      (libsource (lib "eagle-import") (part "R-EU_R0603"))
    )
    (comp (ref "R19")
      (value "21k")
      (footprint "eagle-import:R0603")
      (libsource (lib "eagle-import") (part "R-EU_R0603"))
    )
    (comp (ref "R20")
      (value "0k")
      (footprint "eagle-import:R0603")
      (libsource (lib "eagle-import") (part "R-EU_R0603"))
    )
    (comp (ref "R21")
      (value "DNI")
      (footprint "eagle-import:R0603")
      (libsource (lib "eagle-import") (part "R-EU_R0603"))
    )
    (comp (ref "R22")
      (value "0k")
      (footprint "eagle-import:R0603")
      (libsource (lib "eagle-import") (part "R-EU_R0603"))
    )
    (comp (ref "R32")
      (value "DNI")
      (footprint "eagle-import:R0603")
      (libsource (lib "eagle-import") (part "R-EU_R0603"))
    )
    (comp (ref "R44")
      (value "0k")
      (footprint "eagle-import:R0603")
      (libsource (lib "eagle-import") (part "R-EU_R0603"))
    )
    (comp (ref "U$1")
      (value "JUMPERSMD")
      (footprint "eagle-import:JUMPERWIDE")
      (libsource (lib "eagle-import") (part "JUMPERSMD"))
    )
    (comp (ref "C1R")
      (value "10n")
      (footprint "eagle-import:C0603K")
      (libsource (lib "eagle-import") (part "C-EUC0603K"))
    )
    (comp (ref "C1T")
      (value "10n")
      (footprint "eagle-import:C0603K")
      (libsource (lib "eagle-import") (part "C-EUC0603K"))
    )
    (comp (ref "C2R")
      (value "10n")
      (footprint "eagle-import:C0603K")
      (libsource (lib "eagle-import") (part "C-EUC0603K"))
    )
    (comp (ref "C2T")
      (value "10n")
      (footprint "eagle-import:C0603K")
      (libsource (lib "eagle-import") (part "C-EUC0603K"))
    )
    (comp (ref "C3R")
      (value "10n")
      (footprint "eagle-import:C0603K")
      (libsource (lib "eagle-import") (part "C-EUC0603K"))
    )
    (comp (ref "C3T")
      (value "10n")
      (footprint "eagle-import:C0603K")
      (libsource (lib "eagle-import") (part "C-EUC0603K"))
    )
    (comp (ref "C4R")
      (value "10n")
      (footprint "eagle-import:C0603K")
      (libsource (lib "eagle-import") (part "C-EUC0603K"))
    )
    (comp (ref "C4T")
      (value "10n")
      (footprint "eagle-import:C0603K")
      (libsource (lib "eagle-import") (part "C-EUC0603K"))
    )
    (comp (ref "C5R")
      (value "10n")
      (footprint "eagle-import:C0603K")
      (libsource (lib "eagle-import") (part "C-EUC0603K"))
    )
    (comp (ref "C5T")
      (value "10n")
      (footprint "eagle-import:C0603K")
      (libsource (lib "eagle-import") (part "C-EUC0603K"))
    )
    (comp (ref "C6R")
      (value "10n")
      (footprint "eagle-import:C0603K")
      (libsource (lib "eagle-import") (part "C-EUC0603K"))
    )
    (comp (ref "C6T")
      (value "10n")
      (footprint "eagle-import:C0603K")
      (libsource (lib "eagle-import") (part "C-EUC0603K"))
    )
    (comp (ref "C7R")
      (value "10n")
      (footprint "eagle-import:C0603K")
      (libsource (lib "eagle-import") (part "C-EUC0603K"))
    )
    (comp (ref "C7T")
      (value "10n")
      (footprint "eagle-import:C0603K")
      (libsource (lib "eagle-import") (part "C-EUC0603K"))
    )
    (comp (ref "C8R")
      (value "10n")
      (footprint "eagle-import:C0603K")
      (libsource (lib "eagle-import") (part "C-EUC0603K"))
    )
    (comp (ref "C8T")
      (value "10n")
      (footprint "eagle-import:C0603K")
      (libsource (lib "eagle-import") (part "C-EUC0603K"))
    )
    (comp (ref "C9R")
      (value "10n")
      (footprint "eagle-import:C0603K")
      (libsource (lib "eagle-import") (part "C-EUC0603K"))
    )
    (comp (ref "C9T")
      (value "10n")
      (footprint "eagle-import:C0603K")
      (libsource (lib "eagle-import") (part "C-EUC0603K"))
    )
    (comp (ref "C27")
      (value "100n")
      (footprint "eagle-import:C0805")
      (libsource (lib "eagle-import") (part "C-EUC0805"))
    )
    (comp (ref "C75")
      (value "100n")
      (footprint "eagle-import:C0805")
      (libsource (lib "eagle-import") (part "C-EUC0805"))
    )
    (comp (ref "C85")
      (value "100n")
      (footprint "eagle-import:C0805")
      (libsource (lib "eagle-import") (part "C-EUC0805"))
    )
    (comp (ref "D1R")
      (value "BAT54J,115")
      (footprint "eagle-import:SODFL2512X80N")
      (fields (field (name "RS_PART_NUMBER") "7805363P"))
      (libsource (lib "eagle-import") (part "BAT54J,115"))
    )
    (comp (ref "D1T")
      (value "BAT54J,115")
      (footprint "eagle-import:SODFL2512X80N")
      (fields (field (name "RS_PART_NUMBER") "7805363P"))
      (libsource (lib "eagle-import") (part "BAT54J,115"))
    )
    (comp (ref "D2R")
      (value "BAT54J,115")
      (footprint "eagle-import:SODFL2512X80N")
      (fields (field (name "RS_PART_NUMBER") "7805363P"))
      (libsource (lib "eagle-import") (part "BAT54J,115"))
    )
    (comp (ref "D2T")
      (value "BAT54J,115")
      (footprint "eagle-import:SODFL2512X80N")
      (fields (field (name "RS_PART_NUMBER") "7805363P"))
      (libsource (lib "eagle-import") (part "BAT54J,115"))
    )
    (comp (ref "D3R")
      (value "BAT54J,115")
      (footprint "eagle-import:SODFL2512X80N")
      (fields (field (name "RS_PART_NUMBER") "7805363P"))
      (libsource (lib "eagle-import") (part "BAT54J,115"))
    )
    (comp (ref "D3T")
      (value "BAT54J,115")
      (footprint "eagle-import:SODFL2512X80N")
      (fields (field (name "RS_PART_NUMBER") "7805363P"))
      (libsource (lib "eagle-import") (part "BAT54J,115"))
    )
    (comp (ref "D4R")
      (value "BAT54J,115")
      (footprint "eagle-import:SODFL2512X80N")
      (fields (field (name "RS_PART_NUMBER") "7805363P"))
      (libsource (lib "eagle-import") (part "BAT54J,115"))
    )
    (comp (ref "D4T")
      (value "BAT54J,115")
      (footprint "eagle-import:SODFL2512X80N")
      (fields (field (name "RS_PART_NUMBER") "7805363P"))
      (libsource (lib "eagle-import") (part "BAT54J,115"))
    )
    (comp (ref "D5T")
      (value "BAT54J,115")
      (footprint "eagle-import:SODFL2512X80N")
      (fields (field (name "RS_PART_NUMBER") "7805363P"))
      (libsource (lib "eagle-import") (part "BAT54J,115"))
    )
    (comp (ref "D6T")
      (value "BAT54J,115")
      (footprint "eagle-import:SODFL2512X80N")
      (fields (field (name "RS_PART_NUMBER") "7805363P"))
      (libsource (lib "eagle-import") (part "BAT54J,115"))
    )
    (comp (ref "D7T")
      (value "BAT54J,115")
      (footprint "eagle-import:SODFL2512X80N")
      (fields (field (name "RS_PART_NUMBER") "7805363P"))
      (libsource (lib "eagle-import") (part "BAT54J,115"))
    )
    (comp (ref "D8T")
      (value "BAT54J,115")
      (footprint "eagle-import:SODFL2512X80N")
      (fields (field (name "RS_PART_NUMBER") "7805363P"))
      (libsource (lib "eagle-import") (part "BAT54J,115"))
    )
    (comp (ref "IC7")
      (value "MCP6004-I_ST")
      (footprint "eagle-import:SOP65P640X120-14N")
      (fields
        (field (name "ARROW_PART_NUMBER") "MCP6004-I/ST")
        (field (name "MOUSER_PART_NUMBER") "579-MCP6004-I/ST")
      )
      (libsource (lib "eagle-import") (part "MCP6004-I_ST"))
    )
    (comp (ref "IC9")
      (value "MCP6004-I_ST")
      (footprint "eagle-import:SOP65P640X120-14N")
      (fields
        (field (name "ARROW_PART_NUMBER") "MCP6004-I/ST")
        (field (name "MOUSER_PART_NUMBER") "579-MCP6004-I/ST")
      )
      (libsource (lib "eagle-import") (part "MCP6004-I_ST"))
    )
    (comp (ref "IC13")
      (value "MCP6004-I_ST")
      (footprint "eagle-import:SOP65P640X120-14N")
      (fields
        (field (name "ARROW_PART_NUMBER") "MCP6004-I/ST")
        (field (name "MOUSER_PART_NUMBER") "579-MCP6004-I/ST")
      )
      (libsource (lib "eagle-import") (part "MCP6004-I_ST"))
    )
    (comp (ref "J1")
      (value "35RAPC2AVN4")
      (footprint "eagle-import:35RAPC2AVN4")
      (libsource (lib "eagle-import") (part "35RAPC2AVN4"))
    )
    (comp (ref "J2")
      (value "35RAPC2AVN4")
      (footprint "eagle-import:35RAPC2AVN4")
      (libsource (lib "eagle-import") (part "35RAPC2AVN4"))
    )
    (comp (ref "J3")
      (value "35RAPC2AVN4")
      (footprint "eagle-import:35RAPC2AVN4")
      (libsource (lib "eagle-import") (part "35RAPC2AVN4"))
    )
    (comp (ref "J4")
      (value "35RAPC2AVN4")
      (footprint "eagle-import:35RAPC2AVN4")
      (libsource (lib "eagle-import") (part "35RAPC2AVN4"))
    )
    (comp (ref "J5")
      (value "35RAPC2AVN4")
      (footprint "eagle-import:35RAPC2AVN4")
      (libsource (lib "eagle-import") (part "35RAPC2AVN4"))
    )
    (comp (ref "J6")
      (value "35RAPC2AVN4")
      (footprint "eagle-import:35RAPC2AVN4")
      (libsource (lib "eagle-import") (part "35RAPC2AVN4"))
    )
    (comp (ref "J7")
      (value "35RAPC2AVN4")
      (footprint "eagle-import:35RAPC2AVN4")
      (libsource (lib "eagle-import") (part "35RAPC2AVN4"))
    )
    (comp (ref "J8")
      (value "35RAPC2AVN4")
      (footprint "eagle-import:35RAPC2AVN4")
      (libsource (lib "eagle-import") (part "35RAPC2AVN4"))
    )
    (comp (ref "J9")
      (value "35RAPC2AVN4")
      (footprint "eagle-import:35RAPC2AVN4")
      (libsource (lib "eagle-import") (part "35RAPC2AVN4"))
    )
    (comp (ref "R1R")
      (value "1k")
      (footprint "eagle-import:R0603")
      (libsource (lib "eagle-import") (part "R-EU_R0603"))
    )
    (comp (ref "R1T")
      (value "1k")
      (footprint "eagle-import:R0603")
      (libsource (lib "eagle-import") (part "R-EU_R0603"))
    )
    (comp (ref "R2R")
      (value "1k")
      (footprint "eagle-import:R0603")
      (libsource (lib "eagle-import") (part "R-EU_R0603"))
    )
    (comp (ref "R2T")
      (value "1k")
      (footprint "eagle-import:R0603")
      (libsource (lib "eagle-import") (part "R-EU_R0603"))
    )
    (comp (ref "R3R")
      (value "1k")
      (footprint "eagle-import:R0603")
      (libsource (lib "eagle-import") (part "R-EU_R0603"))
    )
    (comp (ref "R3T")
      (value "1k")
      (footprint "eagle-import:R0603")
      (libsource (lib "eagle-import") (part "R-EU_R0603"))
    )
    (comp (ref "R4R")
      (value "1k")
      (footprint "eagle-import:R0603")
      (libsource (lib "eagle-import") (part "R-EU_R0603"))
    )
    (comp (ref "R4T")
      (value "1k")
      (footprint "eagle-import:R0603")
      (libsource (lib "eagle-import") (part "R-EU_R0603"))
    )
    (comp (ref "R5R")
      (value "1k")
      (footprint "eagle-import:R0603")
      (libsource (lib "eagle-import") (part "R-EU_R0603"))
    )
    (comp (ref "R5RU")
      (value "10k")
      (footprint "eagle-import:R0603")
      (libsource (lib "eagle-import") (part "R-EU_R0603"))
    )
    (comp (ref "R5T")
      (value "1k")
      (footprint "eagle-import:R0603")
      (libsource (lib "eagle-import") (part "R-EU_R0603"))
    )
    (comp (ref "R6R")
      (value "1k")
      (footprint "eagle-import:R0603")
      (libsource (lib "eagle-import") (part "R-EU_R0603"))
    )
    (comp (ref "R6RU")
      (value "10k")
      (footprint "eagle-import:R0603")
      (libsource (lib "eagle-import") (part "R-EU_R0603"))
    )
    (comp (ref "R6T")
      (value "1k")
      (footprint "eagle-import:R0603")
      (libsource (lib "eagle-import") (part "R-EU_R0603"))
    )
    (comp (ref "R7R")
      (value "1k")
      (footprint "eagle-import:R0603")
      (libsource (lib "eagle-import") (part "R-EU_R0603"))
    )
    (comp (ref "R7RU")
      (value "10k")
      (footprint "eagle-import:R0603")
      (libsource (lib "eagle-import") (part "R-EU_R0603"))
    )
    (comp (ref "R7T")
      (value "1k")
      (footprint "eagle-import:R0603")
      (libsource (lib "eagle-import") (part "R-EU_R0603"))
    )
    (comp (ref "R8R")
      (value "1k")
      (footprint "eagle-import:R0603")
      (libsource (lib "eagle-import") (part "R-EU_R0603"))
    )
    (comp (ref "R8RU")
      (value "10k")
      (footprint "eagle-import:R0603")
      (libsource (lib "eagle-import") (part "R-EU_R0603"))
    )
    (comp (ref "R8T")
      (value "1k")
      (footprint "eagle-import:R0603")
      (libsource (lib "eagle-import") (part "R-EU_R0603"))
    )
    (comp (ref "R9R")
      (value "1k")
      (footprint "eagle-import:R0603")
      (libsource (lib "eagle-import") (part "R-EU_R0603"))
    )
    (comp (ref "R9RU")
      (value "10k")
      (footprint "eagle-import:R0603")
      (libsource (lib "eagle-import") (part "R-EU_R0603"))
    )
    (comp (ref "R9T")
      (value "1k")
      (footprint "eagle-import:R0603")
      (libsource (lib "eagle-import") (part "R-EU_R0603"))
    )
    (comp (ref "R9TU")
      (value "10k")
      (footprint "eagle-import:R0603")
      (libsource (lib "eagle-import") (part "R-EU_R0603"))
    )
    (comp (ref "Z1R")
      (value "MM3Z3V3T1G")
      (footprint "eagle-import:SOD2512X110N")
      (fields (field (name "RS_PART_NUMBER") "1841319P"))
      (libsource (lib "eagle-import") (part "MM3Z3V3T1G"))
    )
    (comp (ref "Z1T")
      (value "MM3Z3V3T1G")
      (footprint "eagle-import:SOD2512X110N")
      (fields (field (name "RS_PART_NUMBER") "1841319P"))
      (libsource (lib "eagle-import") (part "MM3Z3V3T1G"))
    )
    (comp (ref "Z2R")
      (value "MM3Z3V3T1G")
      (footprint "eagle-import:SOD2512X110N")
      (fields (field (name "RS_PART_NUMBER") "1841319P"))
      (libsource (lib "eagle-import") (part "MM3Z3V3T1G"))
    )
    (comp (ref "Z2T")
      (value "MM3Z3V3T1G")
      (footprint "eagle-import:SOD2512X110N")
      (fields (field (name "RS_PART_NUMBER") "1841319P"))
      (libsource (lib "eagle-import") (part "MM3Z3V3T1G"))
    )
    (comp (ref "Z3R")
      (value "MM3Z3V3T1G")
      (footprint "eagle-import:SOD2512X110N")
      (fields (field (name "RS_PART_NUMBER") "1841319P"))
      (libsource (lib "eagle-import") (part "MM3Z3V3T1G"))
    )
    (comp (ref "Z3T")
      (value "MM3Z3V3T1G")
      (footprint "eagle-import:SOD2512X110N")
      (fields (field (name "RS_PART_NUMBER") "1841319P"))
      (libsource (lib "eagle-import") (part "MM3Z3V3T1G"))
    )
    (comp (ref "Z4R")
      (value "MM3Z3V3T1G")
      (footprint "eagle-import:SOD2512X110N")
      (fields (field (name "RS_PART_NUMBER") "1841319P"))
      (libsource (lib "eagle-import") (part "MM3Z3V3T1G"))
    )
    (comp (ref "Z4T")
      (value "MM3Z3V3T1G")
      (footprint "eagle-import:SOD2512X110N")
      (fields (field (name "RS_PART_NUMBER") "1841319P"))
      (libsource (lib "eagle-import") (part "MM3Z3V3T1G"))
    )
    (comp (ref "Z5R")
      (value "MM3Z3V3T1G")
      (footprint "eagle-import:SOD2512X110N")
      (fields (field (name "RS_PART_NUMBER") "1841319P"))
      (libsource (lib "eagle-import") (part "MM3Z3V3T1G"))
    )
    (comp (ref "Z5T")
      (value "MM3Z3V3T1G")
      (footprint "eagle-import:SOD2512X110N")
      (fields (field (name "RS_PART_NUMBER") "1841319P"))
      (libsource (lib "eagle-import") (part "MM3Z3V3T1G"))
    )
    (comp (ref "Z6R")
      (value "MM3Z3V3T1G")
      (footprint "eagle-import:SOD2512X110N")
      (fields (field (name "RS_PART_NUMBER") "1841319P"))
      (libsource (lib "eagle-import") (part "MM3Z3V3T1G"))
    )
    (comp (ref "Z6T")
      (value "MM3Z3V3T1G")
      (footprint "eagle-import:SOD2512X110N")
      (fields (field (name "RS_PART_NUMBER") "1841319P"))
      (libsource (lib "eagle-import") (part "MM3Z3V3T1G"))
    )
    (comp (ref "Z7R")
      (value "MM3Z3V3T1G")
      (footprint "eagle-import:SOD2512X110N")
      (fields (field (name "RS_PART_NUMBER") "1841319P"))
      (libsource (lib "eagle-import") (part "MM3Z3V3T1G"))
    )
    (comp (ref "Z7T")
      (value "MM3Z3V3T1G")
      (footprint "eagle-import:SOD2512X110N")
      (fields (field (name "RS_PART_NUMBER") "1841319P"))
      (libsource (lib "eagle-import") (part "MM3Z3V3T1G"))
    )
    (comp (ref "Z8R")
      (value "MM3Z3V3T1G")
      (footprint "eagle-import:SOD2512X110N")
      (fields (field (name "RS_PART_NUMBER") "1841319P"))
      (libsource (lib "eagle-import") (part "MM3Z3V3T1G"))
    )
    (comp (ref "Z8T")
      (value "MM3Z3V3T1G")
      (footprint "eagle-import:SOD2512X110N")
      (fields (field (name "RS_PART_NUMBER") "1841319P"))
      (libsource (lib "eagle-import") (part "MM3Z3V3T1G"))
    )
    (comp (ref "Z9R")
      (value "MM3Z3V3T1G")
      (footprint "eagle-import:SOD2512X110N")
      (fields (field (name "RS_PART_NUMBER") "1841319P"))
      (libsource (lib "eagle-import") (part "MM3Z3V3T1G"))
    )
    (comp (ref "Z9T")
      (value "MM3Z3V3T1G")
      (footprint "eagle-import:SOD2512X110N")
      (fields (field (name "RS_PART_NUMBER") "1841319P"))
      (libsource (lib "eagle-import") (part "MM3Z3V3T1G"))
    )
    (comp (ref "C1")
      (value "10n")
      (footprint "eagle-import:C0402K")
      (libsource (lib "eagle-import") (part "C-EUC0402K"))
    )
    (comp (ref "C2")
      (value "10n")
      (footprint "eagle-import:C0402K")
      (libsource (lib "eagle-import") (part "C-EUC0402K"))
    )
    (comp (ref "C39")
      (value "100n")
      (footprint "eagle-import:C0603K")
      (libsource (lib "eagle-import") (part "C-EUC0603K"))
    )
    (comp (ref "C40")
      (value "10u")
      (footprint "eagle-import:C0603K")
      (libsource (lib "eagle-import") (part "C-EUC0603K"))
    )
    (comp (ref "C41")
      (value "100n")
      (footprint "eagle-import:C0603K")
      (libsource (lib "eagle-import") (part "C-EUC0603K"))
    )
    (comp (ref "C42")
      (value "10u")
      (footprint "eagle-import:C0603K")
      (libsource (lib "eagle-import") (part "C-EUC0603K"))
    )
    (comp (ref "C43")
      (value "100n")
      (footprint "eagle-import:C0603K")
      (libsource (lib "eagle-import") (part "C-EUC0603K"))
    )
    (comp (ref "C44")
      (value "10u")
      (footprint "eagle-import:C0603K")
      (libsource (lib "eagle-import") (part "C-EUC0603K"))
    )
    (comp (ref "C45")
      (value "100n")
      (footprint "eagle-import:C0603K")
      (libsource (lib "eagle-import") (part "C-EUC0603K"))
    )
    (comp (ref "C47")
      (value "CPOL-EUE2-5")
      (footprint "eagle-import:E2-5")
      (libsource (lib "eagle-import") (part "CPOL-EUE2-5"))
    )
    (comp (ref "C48")
      (value "CPOL-EUE2-5")
      (footprint "eagle-import:E2-5")
      (libsource (lib "eagle-import") (part "CPOL-EUE2-5"))
    )
    (comp (ref "C49")
      (value "10u")
      (footprint "eagle-import:C0805")
      (libsource (lib "eagle-import") (part "C-EUC0805"))
    )
    (comp (ref "C50")
      (value "10u")
      (footprint "eagle-import:C0805")
      (libsource (lib "eagle-import") (part "C-EUC0805"))
    )
    (comp (ref "IC5")
      (value "WM8782SEDS_RV")
      (footprint "eagle-import:SOP65P780X200-20N")
      (fields
        (field (name "MANUFACTURER_PART_NUMBER") "WM8782SEDS/RV")
        (field (name "MOUSER_PART_NUMBER") "238-WM8782SEDS/RV")
      )
      (libsource (lib "eagle-import") (part "WM8782SEDS_RV"))
    )
    (comp (ref "JADC")
      (value "SJ-63073E")
      (footprint "eagle-import:SJ63073E")
      (fields (field (name "MOUSER_PART_NUMBER") "490-SJ-63073E"))
      (libsource (lib "eagle-import") (part "SJ-63073E"))
    )
    (comp (ref "R23")
      (value "10k")
      (footprint "eagle-import:R0603")
      (libsource (lib "eagle-import") (part "R-EU_R0603"))
    )
    (comp (ref "R24")
      (value "DNI")
      (footprint "eagle-import:R0603")
      (libsource (lib "eagle-import") (part "R-EU_R0603"))
    )
    (comp (ref "R25")
      (value "0k")
      (footprint "eagle-import:R0603")
      (libsource (lib "eagle-import") (part "R-EU_R0603"))
    )
    (comp (ref "R26")
      (value "DNI")
      (footprint "eagle-import:R0603")
      (libsource (lib "eagle-import") (part "R-EU_R0603"))
    )
    (comp (ref "R27")
      (value "3k3")
      (footprint "eagle-import:R0603")
      (libsource (lib "eagle-import") (part "R-EU_R0603"))
    )
    (comp (ref "R28")
      (value "10k")
      (footprint "eagle-import:R0603")
      (libsource (lib "eagle-import") (part "R-EU_R0603"))
    )
    (comp (ref "R29")
      (value "10k")
      (footprint "eagle-import:R0603")
      (libsource (lib "eagle-import") (part "R-EU_R0603"))
    )
    (comp (ref "R30")
      (value "10k")
      (footprint "eagle-import:R0603")
      (libsource (lib "eagle-import") (part "R-EU_R0603"))
    )
    (comp (ref "R31")
      (value "10k")
      (footprint "eagle-import:R0603")
      (libsource (lib "eagle-import") (part "R-EU_R0603"))
    )
    (comp (ref "BTN1")
      (value "31-XX")
      (footprint "eagle-import:B3F-31XX")
      (fields (field (name "MPN") "B3F-3100"))
      (libsource (lib "eagle-import") (part "31-XX"))
    )
    (comp (ref "BTN2")
      (value "31-XX")
      (footprint "eagle-import:B3F-31XX")
      (fields (field (name "MPN") "B3F-3100"))
      (libsource (lib "eagle-import") (part "31-XX"))
    )
    (comp (ref "BTN3")
      (value "31-XX")
      (footprint "eagle-import:B3F-31XX")
      (fields (field (name "MPN") "B3F-3100"))
      (libsource (lib "eagle-import") (part "31-XX"))
    )
    (comp (ref "BTN4")
      (value "31-XX")
      (footprint "eagle-import:B3F-31XX")
      (fields (field (name "MPN") "B3F-3100"))
      (libsource (lib "eagle-import") (part "31-XX"))
    )
    (comp (ref "BTN5")
      (value "31-XX")
      (footprint "eagle-import:B3F-31XX")
      (fields (field (name "MPN") "B3F-3100"))
      (libsource (lib "eagle-import") (part "31-XX"))
    )
    (comp (ref "BTN6")
      (value "31-XX")
      (footprint "eagle-import:B3F-31XX")
      (fields (field (name "MPN") "B3F-3100"))
      (libsource (lib "eagle-import") (part "31-XX"))
    )
    (comp (ref "BTN7")
      (value "31-XX")
      (footprint "eagle-import:B3F-31XX")
      (fields (field (name "MPN") "B3F-3100"))
      (libsource (lib "eagle-import") (part "31-XX"))
    )
    (comp (ref "BTN8")
      (value "31-XX")
      (footprint "eagle-import:B3F-31XX")
      (fields (field (name "MPN") "B3F-3100"))
      (libsource (lib "eagle-import") (part "31-XX"))
    )
    (comp (ref "BTN9")
      (value "31-XX")
      (footprint "eagle-import:B3F-31XX")
      (fields (field (name "MPN") "B3F-3100"))
      (libsource (lib "eagle-import") (part "31-XX"))
    )
    (comp (ref "C46")
      (value "0.1uF")
      (footprint "eagle-import:C0402")
      (libsource (lib "eagle-import") (part "C-EUC0402"))
    )
    (comp (ref "C80")
      (value "20p")
      (footprint "eagle-import:C0402K")
      (libsource (lib "eagle-import") (part "C-EUC0402K"))
    )
    (comp (ref "C81")
      (value "20p")
      (footprint "eagle-import:C0402K")
      (libsource (lib "eagle-import") (part "C-EUC0402K"))
    )
    (comp (ref "C82")
      (value "100n")
      (footprint "eagle-import:C0603K")
      (libsource (lib "eagle-import") (part "C-EUC0603K"))
    )
    (comp (ref "C83")
      (value "100n")
      (footprint "eagle-import:C0603K")
      (libsource (lib "eagle-import") (part "C-EUC0603K"))
    )
    (comp (ref "C84")
      (value "100n")
      (footprint "eagle-import:C0603K")
      (libsource (lib "eagle-import") (part "C-EUC0603K"))
    )
    (comp (ref "C86")
      (value "100n")
      (footprint "eagle-import:C0603K")
      (libsource (lib "eagle-import") (part "C-EUC0603K"))
    )
    (comp (ref "C87")
      (value "100n")
      (footprint "eagle-import:C0603K")
      (libsource (lib "eagle-import") (part "C-EUC0603K"))
    )
    (comp (ref "C108")
      (value "0.1uF")
      (footprint "eagle-import:C0402")
      (libsource (lib "eagle-import") (part "C-EUC0402"))
    )
    (comp (ref "D1R1")
      (value "BAT54J,115")
      (footprint "eagle-import:SODFL2512X80N")
      (fields (field (name "RS_PART_NUMBER") "7805363P"))
      (libsource (lib "eagle-import") (part "BAT54J,115"))
    )
    (comp (ref "IC6")
      (value "STM32F103C8T6TR")
      (footprint "eagle-import:QFP50P900X900X160-48N")
      (libsource (lib "eagle-import") (part "STM32F103C8T6TR"))
    )
    (comp (ref "J10")
      (value "10103594-0001LF")
      (footprint "eagle-import:AMPHENOL_10103594-0001LF")
      (fields (field (name "DIGI-KEY_PART_NUMBER") "609-4050-1-ND") (field (name "MF") "Amphenol ICC"))
      (libsource (lib "eagle-import") (part "10103594-0001LF"))
    )
    (comp (ref "J13")
      (value "FTSH-105-01-F-DV-K-A-P-TR")
      (footprint "eagle-import:FTSH-105-XX-YYY-DV-K-A-P-TR")
      (fields (field (name "MOUSER_PART_NUMBER") "200-FTSH1051FDVKAPTR"))
      (libsource (lib "eagle-import") (part "FTSH-105-01-F-DV-K-A-P-TR"))
    )
    (comp (ref "LEDA1")
      (value "L-934HD")
      (footprint "eagle-import:T-1(3MM)_2")
      (fields (field (name "RS_PART_NUMBER") "2285922A"))
      (libsource (lib "eagle-import") (part "L-934HD"))
    )
    (comp (ref "LEDA3")
      (value "L-934HD")
      (footprint "eagle-import:T-1(3MM)_2")
      (fields (field (name "RS_PART_NUMBER") "2285922A"))
      (libsource (lib "eagle-import") (part "L-934HD"))
    )
    (comp (ref "LEDA5")
      (value "L-934HD")
      (footprint "eagle-import:T-1(3MM)_2")
      (fields (field (name "RS_PART_NUMBER") "2285922A"))
      (libsource (lib "eagle-import") (part "L-934HD"))
    )
    (comp (ref "LEDA7")
      (value "L-934HD")
      (footprint "eagle-import:T-1(3MM)_2")
      (fields (field (name "RS_PART_NUMBER") "2285922A"))
      (libsource (lib "eagle-import") (part "L-934HD"))
    )
    (comp (ref "LEDA9")
      (value "L-934HD")
      (footprint "eagle-import:T-1(3MM)_2")
      (fields (field (name "RS_PART_NUMBER") "2285922A"))
      (libsource (lib "eagle-import") (part "L-934HD"))
    )
    (comp (ref "LEDA11")
      (value "L-934HD")
      (footprint "eagle-import:T-1(3MM)_2")
      (fields (field (name "RS_PART_NUMBER") "2285922A"))
      (libsource (lib "eagle-import") (part "L-934HD"))
    )
    (comp (ref "LEDA13")
      (value "L-934HD")
      (footprint "eagle-import:T-1(3MM)_2")
      (fields (field (name "RS_PART_NUMBER") "2285922A"))
      (libsource (lib "eagle-import") (part "L-934HD"))
    )
    (comp (ref "LEDA15")
      (value "L-934HD")
      (footprint "eagle-import:T-1(3MM)_2")
      (fields (field (name "RS_PART_NUMBER") "2285922A"))
      (libsource (lib "eagle-import") (part "L-934HD"))
    )
    (comp (ref "LEDA17")
      (value "L-934HD")
      (footprint "eagle-import:T-1(3MM)_2")
      (fields (field (name "RS_PART_NUMBER") "2285922A"))
      (libsource (lib "eagle-import") (part "L-934HD"))
    )
    (comp (ref "LEDB1")
      (value "LEDCHIP-LED0603")
      (footprint "eagle-import:CHIP-LED0603")
      (libsource (lib "eagle-import") (part "LEDCHIP-LED0603"))
    )
    (comp (ref "LEDB3")
      (value "LEDCHIP-LED0603")
      (footprint "eagle-import:CHIP-LED0603")
      (libsource (lib "eagle-import") (part "LEDCHIP-LED0603"))
    )
    (comp (ref "LEDB5")
      (value "LEDCHIP-LED0603")
      (footprint "eagle-import:CHIP-LED0603")
      (libsource (lib "eagle-import") (part "LEDCHIP-LED0603"))
    )
    (comp (ref "LEDB7")
      (value "LEDCHIP-LED0603")
      (footprint "eagle-import:CHIP-LED0603")
      (libsource (lib "eagle-import") (part "LEDCHIP-LED0603"))
    )
    (comp (ref "LEDB9")
      (value "LEDCHIP-LED0603")
      (footprint "eagle-import:CHIP-LED0603")
      (libsource (lib "eagle-import") (part "LEDCHIP-LED0603"))
    )
    (comp (ref "LEDB11")
      (value "LEDCHIP-LED0603")
      (footprint "eagle-import:CHIP-LED0603")
      (libsource (lib "eagle-import") (part "LEDCHIP-LED0603"))
    )
    (comp (ref "LEDB13")
      (value "LEDCHIP-LED0603")
      (footprint "eagle-import:CHIP-LED0603")
      (libsource (lib "eagle-import") (part "LEDCHIP-LED0603"))
    )
    (comp (ref "LEDB15")
      (value "LEDCHIP-LED0603")
      (footprint "eagle-import:CHIP-LED0603")
      (libsource (lib "eagle-import") (part "LEDCHIP-LED0603"))
    )
    (comp (ref "LEDB17")
      (value "LEDCHIP-LED0603")
      (footprint "eagle-import:CHIP-LED0603")
      (libsource (lib "eagle-import") (part "LEDCHIP-LED0603"))
    )
    (comp (ref "LEDC1")
      (value "L-934HD")
      (footprint "eagle-import:T-1(3MM)_2")
      (fields (field (name "RS_PART_NUMBER") "2285922A"))
      (libsource (lib "eagle-import") (part "L-934HD"))
    )
    (comp (ref "LEDC3")
      (value "L-934HD")
      (footprint "eagle-import:T-1(3MM)_2")
      (fields (field (name "RS_PART_NUMBER") "2285922A"))
      (libsource (lib "eagle-import") (part "L-934HD"))
    )
    (comp (ref "LEDC5")
      (value "L-934HD")
      (footprint "eagle-import:T-1(3MM)_2")
      (fields (field (name "RS_PART_NUMBER") "2285922A"))
      (libsource (lib "eagle-import") (part "L-934HD"))
    )
    (comp (ref "LEDC7")
      (value "L-934HD")
      (footprint "eagle-import:T-1(3MM)_2")
      (fields (field (name "RS_PART_NUMBER") "2285922A"))
      (libsource (lib "eagle-import") (part "L-934HD"))
    )
    (comp (ref "LEDC9")
      (value "L-934HD")
      (footprint "eagle-import:T-1(3MM)_2")
      (fields (field (name "RS_PART_NUMBER") "2285922A"))
      (libsource (lib "eagle-import") (part "L-934HD"))
    )
    (comp (ref "LEDC11")
      (value "L-934HD")
      (footprint "eagle-import:T-1(3MM)_2")
      (fields (field (name "RS_PART_NUMBER") "2285922A"))
      (libsource (lib "eagle-import") (part "L-934HD"))
    )
    (comp (ref "LEDC13")
      (value "L-934HD")
      (footprint "eagle-import:T-1(3MM)_2")
      (fields (field (name "RS_PART_NUMBER") "2285922A"))
      (libsource (lib "eagle-import") (part "L-934HD"))
    )
    (comp (ref "LEDC15")
      (value "L-934HD")
      (footprint "eagle-import:T-1(3MM)_2")
      (fields (field (name "RS_PART_NUMBER") "2285922A"))
      (libsource (lib "eagle-import") (part "L-934HD"))
    )
    (comp (ref "LEDC17")
      (value "L-934HD")
      (footprint "eagle-import:T-1(3MM)_2")
      (fields (field (name "RS_PART_NUMBER") "2285922A"))
      (libsource (lib "eagle-import") (part "L-934HD"))
    )
    (comp (ref "LEDD1")
      (value "LEDCHIP-LED0603")
      (footprint "eagle-import:CHIP-LED0603")
      (libsource (lib "eagle-import") (part "LEDCHIP-LED0603"))
    )
    (comp (ref "LEDD3")
      (value "LEDCHIP-LED0603")
      (footprint "eagle-import:CHIP-LED0603")
      (libsource (lib "eagle-import") (part "LEDCHIP-LED0603"))
    )
    (comp (ref "LEDD5")
      (value "LEDCHIP-LED0603")
      (footprint "eagle-import:CHIP-LED0603")
      (libsource (lib "eagle-import") (part "LEDCHIP-LED0603"))
    )
    (comp (ref "LEDD7")
      (value "LEDCHIP-LED0603")
      (footprint "eagle-import:CHIP-LED0603")
      (libsource (lib "eagle-import") (part "LEDCHIP-LED0603"))
    )
    (comp (ref "LEDD9")
      (value "LEDCHIP-LED0603")
      (footprint "eagle-import:CHIP-LED0603")
      (libsource (lib "eagle-import") (part "LEDCHIP-LED0603"))
    )
    (comp (ref "LEDD11")
      (value "LEDCHIP-LED0603")
      (footprint "eagle-import:CHIP-LED0603")
      (libsource (lib "eagle-import") (part "LEDCHIP-LED0603"))
    )
    (comp (ref "LEDD13")
      (value "LEDCHIP-LED0603")
      (footprint "eagle-import:CHIP-LED0603")
      (libsource (lib "eagle-import") (part "LEDCHIP-LED0603"))
    )
    (comp (ref "LEDD15")
      (value "LEDCHIP-LED0603")
      (footprint "eagle-import:CHIP-LED0603")
      (libsource (lib "eagle-import") (part "LEDCHIP-LED0603"))
    )
    (comp (ref "LEDD17")
      (value "LEDCHIP-LED0603")
      (footprint "eagle-import:CHIP-LED0603")
      (libsource (lib "eagle-import") (part "LEDCHIP-LED0603"))
    )
    (comp (ref "Q2")
      (value "CRYSTALHC49S")
      (footprint "eagle-import:HC49_S")
      (libsource (lib "eagle-import") (part "CRYSTALHC49S"))
    )
    (comp (ref "R7")
      (value "R-EU_R0805")
      (footprint "eagle-import:R0805")
      (libsource (lib "eagle-import") (part "R-EU_R0805"))
    )
    (comp (ref "R14")
      (value "10k")
      (footprint "eagle-import:R0603")
      (libsource (lib "eagle-import") (part "R-EU_R0603"))
    )
    (comp (ref "R42")
      (value "10k")
      (footprint "eagle-import:R0603")
      (libsource (lib "eagle-import") (part "R-EU_R0603"))
    )
    (comp (ref "R43")
      (value "3V3")
      (footprint "eagle-import:R0603")
      (libsource (lib "eagle-import") (part "R-EU_R0603"))
    )
    (comp (ref "R48")
      (value "5V")
      (footprint "eagle-import:R0603")
      (libsource (lib "eagle-import") (part "R-EU_R0603"))
    )
    (comp (ref "R49")
      (value "10k")
      (footprint "eagle-import:R0603")
      (libsource (lib "eagle-import") (part "R-EU_R0603"))
    )
    (comp (ref "R50")
      (value "10k")
      (footprint "eagle-import:R0603")
      (libsource (lib "eagle-import") (part "R-EU_R0603"))
    )
    (comp (ref "R51")
      (value "10k")
      (footprint "eagle-import:R0603")
      (libsource (lib "eagle-import") (part "R-EU_R0603"))
    )
    (comp (ref "R52")
      (value "10k")
      (footprint "eagle-import:R0603")
      (libsource (lib "eagle-import") (part "R-EU_R0603"))
    )
    (comp (ref "R53")
      (value "10k")
      (footprint "eagle-import:R0603")
      (libsource (lib "eagle-import") (part "R-EU_R0603"))
    )
    (comp (ref "R54")
      (value "10k")
      (footprint "eagle-import:R0603")
      (libsource (lib "eagle-import") (part "R-EU_R0603"))
    )
    (comp (ref "R55")
      (value "0")
      (footprint "eagle-import:R0603")
      (libsource (lib "eagle-import") (part "R-EU_R0603"))
    )
    (comp (ref "R59")
      (value "10k")
      (footprint "eagle-import:R0603")
      (libsource (lib "eagle-import") (part "R-EU_R0603"))
    )
    (comp (ref "R60")
      (value "0")
      (footprint "eagle-import:R0603")
      (libsource (lib "eagle-import") (part "R-EU_R0603"))
    )
    (comp (ref "R61")
      (value "0")
      (footprint "eagle-import:R0603")
      (libsource (lib "eagle-import") (part "R-EU_R0603"))
    )
    (comp (ref "RBTN1")
      (value "10k")
      (footprint "eagle-import:R0603")
      (libsource (lib "eagle-import") (part "R-EU_R0603"))
    )
    (comp (ref "RBTN3")
      (value "10k")
      (footprint "eagle-import:R0603")
      (libsource (lib "eagle-import") (part "R-EU_R0603"))
    )
    (comp (ref "RBTN5")
      (value "10k")
      (footprint "eagle-import:R0603")
      (libsource (lib "eagle-import") (part "R-EU_R0603"))
    )
    (comp (ref "RBTN7")
      (value "10k")
      (footprint "eagle-import:R0603")
      (libsource (lib "eagle-import") (part "R-EU_R0603"))
    )
    (comp (ref "RBTN9")
      (value "10k")
      (footprint "eagle-import:R0603")
      (libsource (lib "eagle-import") (part "R-EU_R0603"))
    )
    (comp (ref "RBTN11")
      (value "10k")
      (footprint "eagle-import:R0603")
      (libsource (lib "eagle-import") (part "R-EU_R0603"))
    )
    (comp (ref "RBTN13")
      (value "10k")
      (footprint "eagle-import:R0603")
      (libsource (lib "eagle-import") (part "R-EU_R0603"))
    )
    (comp (ref "RBTN15")
      (value "10k")
      (footprint "eagle-import:R0603")
      (libsource (lib "eagle-import") (part "R-EU_R0603"))
    )
    (comp (ref "RBTN17")
      (value "10k")
      (footprint "eagle-import:R0603")
      (libsource (lib "eagle-import") (part "R-EU_R0603"))
    )
    (comp (ref "RLED1")
      (value "1k")
      (footprint "eagle-import:R0603")
      (libsource (lib "eagle-import") (part "R-EU_R0603"))
    )
    (comp (ref "RLED3")
      (value "1k")
      (footprint "eagle-import:R0603")
      (libsource (lib "eagle-import") (part "R-EU_R0603"))
    )
    (comp (ref "RLED5")
      (value "1k")
      (footprint "eagle-import:R0603")
      (libsource (lib "eagle-import") (part "R-EU_R0603"))
    )
    (comp (ref "RLED7")
      (value "1k")
      (footprint "eagle-import:R0603")
      (libsource (lib "eagle-import") (part "R-EU_R0603"))
    )
    (comp (ref "RLED9")
      (value "1k")
      (footprint "eagle-import:R0603")
      (libsource (lib "eagle-import") (part "R-EU_R0603"))
    )
    (comp (ref "RLED11")
      (value "1k")
      (footprint "eagle-import:R0603")
      (libsource (lib "eagle-import") (part "R-EU_R0603"))
    )
    (comp (ref "RLED13")
      (value "1k")
      (footprint "eagle-import:R0603")
      (libsource (lib "eagle-import") (part "R-EU_R0603"))
    )
    (comp (ref "RLED15")
      (value "1k")
      (footprint "eagle-import:R0603")
      (libsource (lib "eagle-import") (part "R-EU_R0603"))
    )
    (comp (ref "RLED17")
      (value "1k")
      (footprint "eagle-import:R0603")
      (libsource (lib "eagle-import") (part "R-EU_R0603"))
    )
    (comp (ref "U$2")
      (value "TFT-SD")
      (footprint "eagle-import:TFTQVGA")
      (libsource (lib "eagle-import") (part "TFT-SD"))
    )
    (comp (ref "U$3")
      (value "EPAPER2.9")
      (footprint "eagle-import:EPAPERLCDNOPIN")
      (libsource (lib "eagle-import") (part "EPAPER2.9"))
    )
    (comp (ref "VR1")
      (value "PEC11R-4220F-S0024")
      (footprint "eagle-import:PEC11R4220FS0024")
      (fields (field (name "RS_PART_NUMBER") "7377767P"))
      (libsource (lib "eagle-import") (part "PEC11R-4220F-S0024"))
    )
    (comp (ref "VR2")
      (value "PEC11R-4220F-S0024")
      (footprint "eagle-import:PEC11R4220FS0024")
      (fields (field (name "RS_PART_NUMBER") "7377767P"))
      (libsource (lib "eagle-import") (part "PEC11R-4220F-S0024"))
    )
  )
  (nets
    (net (code "1") (name "+4.1V") (class "Default")
      (node (ref "C15") (pin "1") (pinfunction "1_1") (pintype "passive"))
      (node (ref "C16") (pin "1") (pinfunction "1_1") (pintype "passive"))
      (node (ref "C17") (pin "1") (pinfunction "1_1") (pintype "passive"))
      (node (ref "C35") (pin "1") (pinfunction "1_1") (pintype "passive"))
      (node (ref "C36") (pin "1") (pinfunction "1_1") (pintype "passive"))
      (node (ref "IC1") (pin "5") (pinfunction "VP_1_5") (pintype "bidirectional"))
      (node (ref "IC1") (pin "8") (pinfunction "VP_2_8") (pintype "bidirectional"))
      (node (ref "IC11") (pin "1") (pinfunction "VOUT_1_1") (pintype "bidirectional"))
      (node (ref "IC11") (pin "2") (pinfunction "VOUT_2_2") (pintype "bidirectional"))
      (node (ref "R20") (pin "1") (pinfunction "1_1") (pintype "passive"))
      (node (ref "U$1") (pin "P$2") (pinfunction "2_P$2") (pintype "passive"))
    )
    (net (code "2") (name "+4V") (class "Default")
      (node (ref "C32") (pin "2") (pinfunction "2_2") (pintype "passive"))
      (node (ref "C33") (pin "2") (pinfunction "2_2") (pintype "passive"))
      (node (ref "C53") (pin "2") (pinfunction "2_2") (pintype "passive"))
      (node (ref "C55") (pin "2") (pinfunction "2_2") (pintype "passive"))
      (node (ref "C58") (pin "2") (pinfunction "2_2") (pintype "passive"))
      (node (ref "C60") (pin "2") (pinfunction "2_2") (pintype "passive"))
      (node (ref "C67") (pin "2") (pinfunction "2_2") (pintype "passive"))
      (node (ref "C69") (pin "2") (pinfunction "2_2") (pintype "passive"))
      (node (ref "IC10") (pin "5") (pinfunction "VOUT_5") (pintype "bidirectional"))
      (node (ref "IC2") (pin "1") (pinfunction "VIN_1") (pintype "bidirectional"))
      (node (ref "IC2") (pin "3") (pinfunction "INHIBIT_3") (pintype "bidirectional"))
      (node (ref "IC3") (pin "1") (pinfunction "VIN_1") (pintype "bidirectional"))
      (node (ref "IC3") (pin "3") (pinfunction "INHIBIT_3") (pintype "bidirectional"))
      (node (ref "IC8") (pin "1") (pinfunction "IN_1") (pintype "bidirectional"))
      (node (ref "R18") (pin "1") (pinfunction "1_1") (pintype "passive"))
    )
    (net (code "3") (name "+12V") (class "Default")
      (node (ref "C88") (pin "+") (pinfunction "+_+") (pintype "passive"))
      (node (ref "IC14") (pin "3") (pinfunction "IN_3") (pintype "bidirectional"))
      (node (ref "J11") (pin "1") (pinfunction "1_1") (pintype "bidirectional"))
    )
    (net (code "4") (name "2V5A") (class "Default")
      (node (ref "C22") (pin "1") (pinfunction "1_1") (pintype "passive"))
      (node (ref "C23") (pin "1") (pinfunction "1_1") (pintype "passive"))
      (node (ref "C24") (pin "1") (pinfunction "1_1") (pintype "passive"))
      (node (ref "C56") (pin "2") (pinfunction "2_2") (pintype "passive"))
      (node (ref "C57") (pin "2") (pinfunction "2_2") (pintype "passive"))
      (node (ref "IC1") (pin "13") (pinfunction "+VHP_13") (pintype "bidirectional"))
      (node (ref "IC1") (pin "16") (pinfunction "VA_16") (pintype "bidirectional"))
      (node (ref "IC2") (pin "5") (pinfunction "VOUT_5") (pintype "bidirectional"))
    )
    (net (code "5") (name "2V5D") (class "Default")
      (node (ref "C19") (pin "1") (pinfunction "1_1") (pintype "passive"))
      (node (ref "C65") (pin "2") (pinfunction "2_2") (pintype "passive"))
      (node (ref "C66") (pin "2") (pinfunction "2_2") (pintype "passive"))
      (node (ref "IC1") (pin "34") (pinfunction "VD_34") (pintype "bidirectional"))
      (node (ref "IC8") (pin "5") (pinfunction "OUT_5") (pintype "bidirectional"))
      (node (ref "R3") (pin "2") (pinfunction "2_2") (pintype "passive"))
    )
    (net (code "6") (name "3V3A") (class "Default")
      (node (ref "C1") (pin "1") (pinfunction "1_1") (pintype "passive"))
      (node (ref "C45") (pin "1") (pinfunction "1_1") (pintype "passive"))
      (node (ref "C51") (pin "2") (pinfunction "2_2") (pintype "passive"))
      (node (ref "C52") (pin "2") (pinfunction "2_2") (pintype "passive"))
      (node (ref "IC3") (pin "5") (pinfunction "VOUT_5") (pintype "bidirectional"))
      (node (ref "IC5") (pin "13") (pinfunction "AVDD_13") (pintype "bidirectional"))
    )
    (net (code "7") (name "3V3D") (class "Default")
      (node (ref "C100") (pin "1") (pinfunction "1_1") (pintype "passive"))
      (node (ref "C106") (pin "2") (pinfunction "2_2") (pintype "passive"))
      (node (ref "C107") (pin "2") (pinfunction "2_2") (pintype "passive"))
      (node (ref "C108") (pin "1") (pinfunction "1_1") (pintype "passive"))
      (node (ref "C18") (pin "1") (pinfunction "1_1") (pintype "passive"))
      (node (ref "C20") (pin "1") (pinfunction "1_1") (pintype "passive"))
      (node (ref "C21") (pin "1") (pinfunction "1_1") (pintype "passive"))
      (node (ref "C27") (pin "1") (pinfunction "1_1") (pintype "passive"))
      (node (ref "C39") (pin "1") (pinfunction "1_1") (pintype "passive"))
      (node (ref "C40") (pin "1") (pinfunction "1_1") (pintype "passive"))
      (node (ref "C61") (pin "1") (pinfunction "1_1") (pintype "passive"))
      (node (ref "C62") (pin "1") (pinfunction "1_1") (pintype "passive"))
      (node (ref "C75") (pin "1") (pinfunction "1_1") (pintype "passive"))
      (node (ref "C76") (pin "1") (pinfunction "1_1") (pintype "passive"))
      (node (ref "C77") (pin "1") (pinfunction "1_1") (pintype "passive"))
      (node (ref "C82") (pin "1") (pinfunction "1_1") (pintype "passive"))
      (node (ref "C83") (pin "1") (pinfunction "1_1") (pintype "passive"))
      (node (ref "C84") (pin "2") (pinfunction "2_2") (pintype "passive"))
      (node (ref "C85") (pin "1") (pinfunction "1_1") (pintype "passive"))
      (node (ref "C86") (pin "2") (pinfunction "2_2") (pintype "passive"))
      (node (ref "C87") (pin "2") (pinfunction "2_2") (pintype "passive"))
      (node (ref "C92") (pin "1") (pinfunction "1_1") (pintype "passive"))
      (node (ref "C97") (pin "1") (pinfunction "1_1") (pintype "passive"))
      (node (ref "C98") (pin "1") (pinfunction "1_1") (pintype "passive"))
      (node (ref "C99") (pin "1") (pinfunction "1_1") (pintype "passive"))
      (node (ref "IC1") (pin "33") (pinfunction "VL_33") (pintype "bidirectional"))
      (node (ref "IC12") (pin "3") (pinfunction "~{WP_(IO2})_3") (pintype "bidirectional"))
      (node (ref "IC12") (pin "7") (pinfunction "~{HOLD_OR_}RESET_(IO3)_7") (pintype "bidirectional"))
      (node (ref "IC12") (pin "8") (pinfunction "VCC_8") (pintype "bidirectional"))
      (node (ref "IC13") (pin "4") (pinfunction "VDD_4") (pintype "bidirectional"))
      (node (ref "IC4") (pin "1") (pinfunction "VOUT_1_1") (pintype "bidirectional"))
      (node (ref "IC4") (pin "2") (pinfunction "VOUT_2_2") (pintype "bidirectional"))
      (node (ref "IC5") (pin "5") (pinfunction "DVDD_5") (pintype "bidirectional"))
      (node (ref "IC6") (pin "24") (pinfunction "VDD_1_24") (pintype "bidirectional"))
      (node (ref "IC6") (pin "36") (pinfunction "VDD_2_36") (pintype "bidirectional"))
      (node (ref "IC6") (pin "48") (pinfunction "VDD_3_48") (pintype "bidirectional"))
      (node (ref "IC6") (pin "9") (pinfunction "VDDA_9") (pintype "bidirectional"))
      (node (ref "IC7") (pin "4") (pinfunction "VDD_4") (pintype "bidirectional"))
      (node (ref "IC9") (pin "4") (pinfunction "VDD_4") (pintype "bidirectional"))
      (node (ref "J12") (pin "4") (pinfunction "VDD1_4") (pintype "bidirectional"))
      (node (ref "L4") (pin "2") (pinfunction "2_2") (pintype "passive"))
      (node (ref "R15") (pin "1") (pinfunction "1_1") (pintype "bidirectional"))
      (node (ref "R16") (pin "2") (pinfunction "2_2") (pintype "passive"))
      (node (ref "R17") (pin "1") (pinfunction "1_1") (pintype "bidirectional"))
      (node (ref "R22") (pin "1") (pinfunction "1_1") (pintype "passive"))
      (node (ref "R43") (pin "1") (pinfunction "1_1") (pintype "passive"))
      (node (ref "R46") (pin "1") (pinfunction "1_1") (pintype "bidirectional"))
      (node (ref "R47") (pin "1") (pinfunction "1_1") (pintype "bidirectional"))
      (node (ref "R49") (pin "1") (pinfunction "1_1") (pintype "passive"))
      (node (ref "R50") (pin "1") (pinfunction "1_1") (pintype "passive"))
      (node (ref "R51") (pin "1") (pinfunction "1_1") (pintype "passive"))
      (node (ref "R52") (pin "1") (pinfunction "1_1") (pintype "passive"))
      (node (ref "R53") (pin "1") (pinfunction "1_1") (pintype "passive"))
      (node (ref "R54") (pin "1") (pinfunction "1_1") (pintype "passive"))
      (node (ref "R59") (pin "2") (pinfunction "2_2") (pintype "passive"))
      (node (ref "R5RU") (pin "1") (pinfunction "1_1") (pintype "passive"))
      (node (ref "R6") (pin "1") (pinfunction "1_1") (pintype "passive"))
      (node (ref "R62") (pin "1") (pinfunction "1_1") (pintype "passive"))
      (node (ref "R63") (pin "1") (pinfunction "1_1") (pintype "passive"))
      (node (ref "R6RU") (pin "1") (pinfunction "1_1") (pintype "passive"))
      (node (ref "R7RU") (pin "1") (pinfunction "1_1") (pintype "passive"))
      (node (ref "R8RU") (pin "1") (pinfunction "1_1") (pintype "passive"))
      (node (ref "R9RU") (pin "1") (pinfunction "1_1") (pintype "passive"))
      (node (ref "R9TU") (pin "1") (pinfunction "1_1") (pintype "passive"))
      (node (ref "RBTN1") (pin "1") (pinfunction "1_1") (pintype "passive"))
      (node (ref "RBTN11") (pin "1") (pinfunction "1_1") (pintype "passive"))
      (node (ref "RBTN13") (pin "1") (pinfunction "1_1") (pintype "passive"))
      (node (ref "RBTN15") (pin "1") (pinfunction "1_1") (pintype "passive"))
      (node (ref "RBTN17") (pin "1") (pinfunction "1_1") (pintype "passive"))
      (node (ref "RBTN3") (pin "1") (pinfunction "1_1") (pintype "passive"))
      (node (ref "RBTN5") (pin "1") (pinfunction "1_1") (pintype "passive"))
      (node (ref "RBTN7") (pin "1") (pinfunction "1_1") (pintype "passive"))
      (node (ref "RBTN9") (pin "1") (pinfunction "1_1") (pintype "passive"))
      (node (ref "U$1") (pin "P$1") (pinfunction "1_P$1") (pintype "passive"))
      (node (ref "U1") (pin "100") (pinfunction "VDD_100") (pintype "power_in"))
      (node (ref "U1") (pin "11") (pinfunction "VDD_2_11") (pintype "power_in"))
      (node (ref "U1") (pin "19") (pinfunction "VDD_3_19") (pintype "power_in"))
      (node (ref "U1") (pin "28") (pinfunction "VDD_4_28") (pintype "power_in"))
      (node (ref "U1") (pin "50") (pinfunction "VDD_5_50") (pintype "power_in"))
      (node (ref "U1") (pin "75") (pinfunction "VDD_6_75") (pintype "power_in"))
      (node (ref "X3") (pin "1") (pinfunction "1_1") (pintype "passive"))
      (node (ref "X5") (pin "1") (pinfunction "1_1") (pintype "passive"))
    )
    (net (code "8") (name "ADC_BCLK") (class "Default")
      (node (ref "IC5") (pin "6") (pinfunction "BCLK_6") (pintype "bidirectional"))
      (node (ref "U1") (pin "52") (pinfunction "PB13_52") (pintype "bidirectional"))
    )
    (net (code "9") (name "ADC_DOUT") (class "Default")
      (node (ref "IC5") (pin "2") (pinfunction "DOUT_2") (pintype "bidirectional"))
      (node (ref "U1") (pin "54") (pinfunction "PB15_54") (pintype "bidirectional"))
    )
    (net (code "10") (name "ADC_LRCLK") (class "Default")
      (node (ref "IC5") (pin "3") (pinfunction "LRCLK_3") (pintype "bidirectional"))
      (node (ref "U1") (pin "51") (pinfunction "PB12_51") (pintype "bidirectional"))
    )
    (net (code "11") (name "ADC_MCLK") (class "Default")
      (node (ref "IC5") (pin "1") (pinfunction "MCLK_1") (pintype "bidirectional"))
      (node (ref "U1") (pin "63") (pinfunction "PC6_63") (pintype "bidirectional"))
    )
    (net (code "12") (name "BTN1") (class "Default")
      (node (ref "BTN1") (pin "B1") (pinfunction "S_B1") (pintype "passive"))
      (node (ref "BTN1") (pin "B2") (pinfunction "S_B2") (pintype "passive"))
      (node (ref "IC6") (pin "29") (pinfunction "PA8_29") (pintype "bidirectional"))
      (node (ref "RBTN1") (pin "2") (pinfunction "2_2") (pintype "passive"))
    )
    (net (code "13") (name "BTN2") (class "Default")
      (node (ref "BTN2") (pin "B1") (pinfunction "S_B1") (pintype "passive"))
      (node (ref "BTN2") (pin "B2") (pinfunction "S_B2") (pintype "passive"))
      (node (ref "IC6") (pin "26") (pinfunction "PB13_26") (pintype "bidirectional"))
      (node (ref "RBTN3") (pin "2") (pinfunction "2_2") (pintype "passive"))
    )
    (net (code "14") (name "BTN3") (class "Default")
      (node (ref "BTN3") (pin "B1") (pinfunction "S_B1") (pintype "passive"))
      (node (ref "BTN3") (pin "B2") (pinfunction "S_B2") (pintype "passive"))
      (node (ref "IC6") (pin "20") (pinfunction "PB2_20") (pintype "bidirectional"))
      (node (ref "RBTN5") (pin "2") (pinfunction "2_2") (pintype "passive"))
    )
    (net (code "15") (name "BTN4") (class "Default")
      (node (ref "BTN4") (pin "B1") (pinfunction "S_B1") (pintype "passive"))
      (node (ref "BTN4") (pin "B2") (pinfunction "S_B2") (pintype "passive"))
      (node (ref "IC6") (pin "18") (pinfunction "PB0_18") (pintype "bidirectional"))
      (node (ref "RBTN7") (pin "2") (pinfunction "2_2") (pintype "passive"))
    )
    (net (code "16") (name "BTN5") (class "Default")
      (node (ref "BTN5") (pin "B1") (pinfunction "S_B1") (pintype "passive"))
      (node (ref "BTN5") (pin "B2") (pinfunction "S_B2") (pintype "passive"))
      (node (ref "IC6") (pin "16") (pinfunction "PA6_16") (pintype "bidirectional"))
      (node (ref "RBTN9") (pin "2") (pinfunction "2_2") (pintype "passive"))
    )
    (net (code "17") (name "BTN6") (class "Default")
      (node (ref "BTN6") (pin "B1") (pinfunction "S_B1") (pintype "passive"))
      (node (ref "BTN6") (pin "B2") (pinfunction "S_B2") (pintype "passive"))
      (node (ref "IC6") (pin "14") (pinfunction "PA4_14") (pintype "bidirectional"))
      (node (ref "RBTN11") (pin "2") (pinfunction "2_2") (pintype "passive"))
    )
    (net (code "18") (name "BTN7") (class "Default")
      (node (ref "BTN7") (pin "B1") (pinfunction "S_B1") (pintype "passive"))
      (node (ref "BTN7") (pin "B2") (pinfunction "S_B2") (pintype "passive"))
      (node (ref "IC6") (pin "12") (pinfunction "PA2_12") (pintype "bidirectional"))
      (node (ref "RBTN13") (pin "2") (pinfunction "2_2") (pintype "passive"))
    )
    (net (code "19") (name "BTN8") (class "Default")
      (node (ref "BTN8") (pin "B1") (pinfunction "S_B1") (pintype "passive"))
      (node (ref "BTN8") (pin "B2") (pinfunction "S_B2") (pintype "passive"))
      (node (ref "IC6") (pin "3") (pinfunction "PC14-OSC32_IN_3") (pintype "bidirectional"))
      (node (ref "RBTN15") (pin "2") (pinfunction "2_2") (pintype "passive"))
    )
    (net (code "20") (name "BTN9") (class "Default")
      (node (ref "BTN9") (pin "B1") (pinfunction "S_B1") (pintype "passive"))
      (node (ref "BTN9") (pin "B2") (pinfunction "S_B2") (pintype "passive"))
      (node (ref "IC6") (pin "2") (pinfunction "PC13-TAMPER-RT_C_2") (pintype "bidirectional"))
      (node (ref "RBTN17") (pin "2") (pinfunction "2_2") (pintype "passive"))
    )
    (net (code "21") (name "COM_RX") (class "Default")
      (node (ref "U1") (pin "87") (pinfunction "PD6_87") (pintype "bidirectional"))
      (node (ref "X3") (pin "4") (pinfunction "1_4") (pintype "passive"))
    )
    (net (code "22") (name "COM_TX") (class "Default")
      (node (ref "U1") (pin "86") (pinfunction "PD5_86") (pintype "bidirectional"))
      (node (ref "X3") (pin "3") (pinfunction "1_3") (pintype "passive"))
    )
    (net (code "23") (name "DAC_LRCK") (class "Default")
      (node (ref "IC1") (pin "40") (pinfunction "LRCK_40") (pintype "bidirectional"))
      (node (ref "U1") (pin "77") (pinfunction "PA15_77") (pintype "bidirectional"))
    )
    (net (code "24") (name "DAC_MCLK") (class "Default")
      (node (ref "IC1") (pin "37") (pinfunction "MCLK_37") (pintype "bidirectional"))
      (node (ref "U1") (pin "64") (pinfunction "PC7_64") (pintype "bidirectional"))
    )
    (net (code "25") (name "DAC_NRST") (class "Default")
      (node (ref "IC1") (pin "32") (pinfunction "~{RESET}_32") (pintype "bidirectional"))
      (node (ref "U1") (pin "65") (pinfunction "PC8_65") (pintype "bidirectional"))
    )
    (net (code "26") (name "DAC_SCL") (class "Default")
      (node (ref "IC1") (pin "2") (pinfunction "SCL_2") (pintype "bidirectional"))
      (node (ref "R62") (pin "2") (pinfunction "2_2") (pintype "passive"))
      (node (ref "U1") (pin "95") (pinfunction "PB8_95") (pintype "bidirectional"))
    )
    (net (code "27") (name "DAC_SCLK") (class "Default")
      (node (ref "IC1") (pin "38") (pinfunction "SCLK_38") (pintype "bidirectional"))
      (node (ref "U1") (pin "78") (pinfunction "PC10_78") (pintype "bidirectional"))
    )
    (net (code "28") (name "DAC_SDA") (class "Default")
      (node (ref "IC1") (pin "1") (pinfunction "SDA_1") (pintype "bidirectional"))
      (node (ref "R63") (pin "2") (pinfunction "2_2") (pintype "passive"))
      (node (ref "U1") (pin "96") (pinfunction "PB9_96") (pintype "bidirectional"))
    )
    (net (code "29") (name "DAC_SDIN") (class "Default")
      (node (ref "IC1") (pin "39") (pinfunction "SDIN_39") (pintype "bidirectional"))
      (node (ref "U1") (pin "80") (pinfunction "PC12_80") (pintype "bidirectional"))
    )
    (net (code "30") (name "EN1A") (class "Default")
      (node (ref "IC6") (pin "43") (pinfunction "PB7_43") (pintype "bidirectional"))
      (node (ref "R54") (pin "2") (pinfunction "2_2") (pintype "passive"))
      (node (ref "VR2") (pin "A1") (pinfunction "A_A1") (pintype "bidirectional"))
    )
    (net (code "31") (name "EN1B") (class "Default")
      (node (ref "IC6") (pin "42") (pinfunction "PB6_42") (pintype "bidirectional"))
      (node (ref "R52") (pin "2") (pinfunction "2_2") (pintype "passive"))
      (node (ref "VR2") (pin "B1") (pinfunction "B_B1") (pintype "bidirectional"))
    )
    (net (code "32") (name "EN1PB") (class "Default")
      (node (ref "IC6") (pin "4") (pinfunction "PC15-OSC32_OUT_4") (pintype "bidirectional"))
      (node (ref "R53") (pin "2") (pinfunction "2_2") (pintype "passive"))
      (node (ref "VR2") (pin "1") (pinfunction "1_1") (pintype "bidirectional"))
    )
    (net (code "33") (name "EN2A") (class "Default")
      (node (ref "IC6") (pin "11") (pinfunction "PA1_11") (pintype "bidirectional"))
      (node (ref "R51") (pin "2") (pinfunction "2_2") (pintype "passive"))
      (node (ref "VR1") (pin "A1") (pinfunction "A_A1") (pintype "bidirectional"))
    )
    (net (code "34") (name "EN2B") (class "Default")
      (node (ref "IC6") (pin "10") (pinfunction "PA0-WKUP_10") (pintype "bidirectional"))
      (node (ref "R49") (pin "2") (pinfunction "2_2") (pintype "passive"))
      (node (ref "VR1") (pin "B1") (pinfunction "B_B1") (pintype "bidirectional"))
    )
    (net (code "35") (name "EN2PB") (class "Default")
      (node (ref "IC6") (pin "27") (pinfunction "PB14_27") (pintype "bidirectional"))
      (node (ref "R50") (pin "2") (pinfunction "2_2") (pintype "passive"))
      (node (ref "VR1") (pin "1") (pinfunction "1_1") (pintype "bidirectional"))
    )
    (net (code "36") (name "F1RST") (class "Default")
      (node (ref "C46") (pin "1") (pinfunction "1_1") (pintype "passive"))
      (node (ref "IC6") (pin "7") (pinfunction "NRST_7") (pintype "bidirectional"))
      (node (ref "J13") (pin "10") (pinfunction "10_10") (pintype "bidirectional"))
      (node (ref "R59") (pin "1") (pinfunction "1_1") (pintype "passive"))
    )
    (net (code "37") (name "F1SWCLK") (class "Default")
      (node (ref "IC6") (pin "37") (pinfunction "PA14_37") (pintype "bidirectional"))
      (node (ref "J13") (pin "4") (pinfunction "4_4") (pintype "bidirectional"))
      (node (ref "R55") (pin "1") (pinfunction "1_1") (pintype "passive"))
    )
    (net (code "38") (name "F1SWDIO") (class "Default")
      (node (ref "IC6") (pin "34") (pinfunction "PA13_34") (pintype "bidirectional"))
      (node (ref "J13") (pin "2") (pinfunction "2_2") (pintype "bidirectional"))
      (node (ref "R60") (pin "1") (pinfunction "1_1") (pintype "passive"))
    )
    (net (code "39") (name "F1USB_D+") (class "Default")
      (node (ref "IC6") (pin "33") (pinfunction "PA12_33") (pintype "bidirectional"))
      (node (ref "J10") (pin "3") (pinfunction "D+_3") (pintype "bidirectional"))
    )
    (net (code "40") (name "F1USB_D-") (class "Default")
      (node (ref "IC6") (pin "32") (pinfunction "PA11_32") (pintype "bidirectional"))
      (node (ref "J10") (pin "2") (pinfunction "D-_2") (pintype "bidirectional"))
    )
    (net (code "41") (name "F1_CLK") (class "Default")
      (node (ref "IC6") (pin "39") (pinfunction "PB3_39") (pintype "bidirectional"))
      (node (ref "U$2") (pin "SCK") (pinfunction "SCK_SCK") (pintype "bidirectional"))
    )
    (net (code "42") (name "F1_MISO") (class "Default")
      (node (ref "IC6") (pin "40") (pinfunction "PB4_40") (pintype "bidirectional"))
      (node (ref "U$2") (pin "MISO") (pinfunction "MISO_MISO") (pintype "bidirectional"))
    )
    (net (code "43") (name "F1_MOSI") (class "Default")
      (node (ref "IC6") (pin "41") (pinfunction "PB5_41") (pintype "bidirectional"))
      (node (ref "U$2") (pin "MOSI") (pinfunction "MOSI_MOSI") (pintype "bidirectional"))
    )
    (net (code "44") (name "F4RST") (class "Default")
      (node (ref "C101") (pin "1") (pinfunction "1_1") (pintype "passive"))
      (node (ref "J14") (pin "10") (pinfunction "10_10") (pintype "bidirectional"))
      (node (ref "R16") (pin "1") (pinfunction "1_1") (pintype "passive"))
      (node (ref "U1") (pin "14") (pinfunction "NRST_14") (pintype "bidirectional"))
    )
    (net (code "45") (name "F4SPI_CLK") (class "Default")
      (node (ref "IC12") (pin "6") (pinfunction "CLK_6") (pintype "bidirectional"))
      (node (ref "J12") (pin "5") (pinfunction "CLK_5") (pintype "bidirectional"))
      (node (ref "U$2") (pin "SCK_SD") (pinfunction "SD_SCK_SCK_SD") (pintype "bidirectional"))
      (node (ref "U1") (pin "89") (pinfunction "PB3_89") (pintype "bidirectional"))
    )
    (net (code "46") (name "F4SPI_MISO") (class "Default")
      (node (ref "IC12") (pin "2") (pinfunction "DO_(IO1)_2") (pintype "bidirectional"))
      (node (ref "J12") (pin "7") (pinfunction "DAT0_7") (pintype "bidirectional"))
      (node (ref "U$2") (pin "MISO_SD") (pinfunction "SD_MISO_MISO_SD") (pintype "bidirectional"))
      (node (ref "U1") (pin "90") (pinfunction "PB4_90") (pintype "bidirectional"))
    )
    (net (code "47") (name "F4SPI_MOSI") (class "Default")
      (node (ref "IC12") (pin "5") (pinfunction "DI_(IO0)_5") (pintype "bidirectional"))
      (node (ref "J12") (pin "2") (pinfunction "CMD_2") (pintype "bidirectional"))
      (node (ref "U$2") (pin "MOSI_SD") (pinfunction "SD_MOSI_MOSI_SD") (pintype "bidirectional"))
      (node (ref "U1") (pin "91") (pinfunction "PB5_91") (pintype "bidirectional"))
    )
    (net (code "48") (name "F4SWCLK") (class "Default")
      (node (ref "J14") (pin "4") (pinfunction "4_4") (pintype "bidirectional"))
      (node (ref "U1") (pin "76") (pinfunction "PA14_76") (pintype "bidirectional"))
    )
    (net (code "49") (name "F4SWDIO") (class "Default")
      (node (ref "J14") (pin "2") (pinfunction "2_2") (pintype "bidirectional"))
      (node (ref "U1") (pin "72") (pinfunction "PA13_72") (pintype "bidirectional"))
    )
    (net (code "50") (name "GND") (class "Default")
      (node (ref "BTN1") (pin "A1") (pinfunction "P_A1") (pintype "passive"))
      (node (ref "BTN1") (pin "A2") (pinfunction "P_A2") (pintype "passive"))
      (node (ref "BTN2") (pin "A1") (pinfunction "P_A1") (pintype "passive"))
      (node (ref "BTN2") (pin "A2") (pinfunction "P_A2") (pintype "passive"))
      (node (ref "BTN3") (pin "A1") (pinfunction "P_A1") (pintype "passive"))
      (node (ref "BTN3") (pin "A2") (pinfunction "P_A2") (pintype "passive"))
      (node (ref "BTN4") (pin "A1") (pinfunction "P_A1") (pintype "passive"))
      (node (ref "BTN4") (pin "A2") (pinfunction "P_A2") (pintype "passive"))
      (node (ref "BTN5") (pin "A1") (pinfunction "P_A1") (pintype "passive"))
      (node (ref "BTN5") (pin "A2") (pinfunction "P_A2") (pintype "passive"))
      (node (ref "BTN6") (pin "A1") (pinfunction "P_A1") (pintype "passive"))
      (node (ref "BTN6") (pin "A2") (pinfunction "P_A2") (pintype "passive"))
      (node (ref "BTN7") (pin "A1") (pinfunction "P_A1") (pintype "passive"))
      (node (ref "BTN7") (pin "A2") (pinfunction "P_A2") (pintype "passive"))
      (node (ref "BTN8") (pin "A1") (pinfunction "P_A1") (pintype "passive"))
      (node (ref "BTN8") (pin "A2") (pinfunction "P_A2") (pintype "passive"))
      (node (ref "BTN9") (pin "A1") (pinfunction "P_A1") (pintype "passive"))
      (node (ref "BTN9") (pin "A2") (pinfunction "P_A2") (pintype "passive"))
      (node (ref "C1") (pin "2") (pinfunction "2_2") (pintype "passive"))
      (node (ref "C10") (pin "2") (pinfunction "2_2") (pintype "passive"))
      (node (ref "C100") (pin "2") (pinfunction "2_2") (pintype "passive"))
      (node (ref "C101") (pin "2") (pinfunction "2_2") (pintype "passive"))
      (node (ref "C102") (pin "2") (pinfunction "2_2") (pintype "passive"))
      (node (ref "C103") (pin "2") (pinfunction "2_2") (pintype "passive"))
      (node (ref "C104") (pin "2") (pinfunction "2_2") (pintype "passive"))
      (node (ref "C105") (pin "2") (pinfunction "2_2") (pintype "passive"))
      (node (ref "C106") (pin "1") (pinfunction "1_1") (pintype "passive"))
      (node (ref "C107") (pin "1") (pinfunction "1_1") (pintype "passive"))
      (node (ref "C13") (pin "2") (pinfunction "2_2") (pintype "passive"))
      (node (ref "C14") (pin "2") (pinfunction "2_2") (pintype "passive"))
      (node (ref "C15") (pin "2") (pinfunction "2_2") (pintype "passive"))
      (node (ref "C16") (pin "2") (pinfunction "2_2") (pintype "passive"))
      (node (ref "C17") (pin "2") (pinfunction "2_2") (pintype "passive"))
      (node (ref "C18") (pin "2") (pinfunction "2_2") (pintype "passive"))
      (node (ref "C19") (pin "2") (pinfunction "2_2") (pintype "passive"))
      (node (ref "C1R") (pin "2") (pinfunction "2_2") (pintype "passive"))
      (node (ref "C1T") (pin "2") (pinfunction "2_2") (pintype "passive"))
      (node (ref "C2") (pin "2") (pinfunction "2_2") (pintype "passive"))
      (node (ref "C20") (pin "2") (pinfunction "2_2") (pintype "passive"))
      (node (ref "C21") (pin "2") (pinfunction "2_2") (pintype "passive"))
      (node (ref "C22") (pin "2") (pinfunction "2_2") (pintype "passive"))
      (node (ref "C23") (pin "2") (pinfunction "2_2") (pintype "passive"))
      (node (ref "C24") (pin "2") (pinfunction "2_2") (pintype "passive"))
      (node (ref "C27") (pin "2") (pinfunction "2_2") (pintype "passive"))
      (node (ref "C2R") (pin "2") (pinfunction "2_2") (pintype "passive"))
      (node (ref "C2T") (pin "2") (pinfunction "2_2") (pintype "passive"))
      (node (ref "C3") (pin "2") (pinfunction "2_2") (pintype "passive"))
      (node (ref "C32") (pin "1") (pinfunction "1_1") (pintype "passive"))
      (node (ref "C33") (pin "1") (pinfunction "1_1") (pintype "passive"))
      (node (ref "C34") (pin "1") (pinfunction "1_1") (pintype "passive"))
      (node (ref "C35") (pin "2") (pinfunction "2_2") (pintype "passive"))
      (node (ref "C36") (pin "2") (pinfunction "2_2") (pintype "passive"))
      (node (ref "C37") (pin "2") (pinfunction "2_2") (pintype "passive"))
      (node (ref "C38") (pin "2") (pinfunction "2_2") (pintype "passive"))
      (node (ref "C39") (pin "2") (pinfunction "2_2") (pintype "passive"))
      (node (ref "C3R") (pin "2") (pinfunction "2_2") (pintype "passive"))
      (node (ref "C3T") (pin "2") (pinfunction "2_2") (pintype "passive"))
      (node (ref "C4") (pin "2") (pinfunction "2_2") (pintype "passive"))
      (node (ref "C40") (pin "2") (pinfunction "2_2") (pintype "passive"))
      (node (ref "C41") (pin "2") (pinfunction "2_2") (pintype "passive"))
      (node (ref "C42") (pin "2") (pinfunction "2_2") (pintype "passive"))
      (node (ref "C43") (pin "2") (pinfunction "2_2") (pintype "passive"))
      (node (ref "C44") (pin "2") (pinfunction "2_2") (pintype "passive"))
      (node (ref "C45") (pin "2") (pinfunction "2_2") (pintype "passive"))
      (node (ref "C46") (pin "2") (pinfunction "2_2") (pintype "passive"))
      (node (ref "C4R") (pin "2") (pinfunction "2_2") (pintype "passive"))
      (node (ref "C4T") (pin "2") (pinfunction "2_2") (pintype "passive"))
      (node (ref "C5") (pin "2") (pinfunction "2_2") (pintype "passive"))
      (node (ref "C51") (pin "1") (pinfunction "1_1") (pintype "passive"))
      (node (ref "C52") (pin "1") (pinfunction "1_1") (pintype "passive"))
      (node (ref "C53") (pin "1") (pinfunction "1_1") (pintype "passive"))
      (node (ref "C54") (pin "1") (pinfunction "1_1") (pintype "passive"))
      (node (ref "C55") (pin "1") (pinfunction "1_1") (pintype "passive"))
      (node (ref "C56") (pin "1") (pinfunction "1_1") (pintype "passive"))
      (node (ref "C57") (pin "1") (pinfunction "1_1") (pintype "passive"))
      (node (ref "C58") (pin "1") (pinfunction "1_1") (pintype "passive"))
      (node (ref "C59") (pin "1") (pinfunction "1_1") (pintype "passive"))
      (node (ref "C5R") (pin "2") (pinfunction "2_2") (pintype "passive"))
      (node (ref "C5T") (pin "2") (pinfunction "2_2") (pintype "passive"))
      (node (ref "C6") (pin "2") (pinfunction "2_2") (pintype "passive"))
      (node (ref "C60") (pin "1") (pinfunction "1_1") (pintype "passive"))
      (node (ref "C61") (pin "2") (pinfunction "2_2") (pintype "passive"))
      (node (ref "C62") (pin "2") (pinfunction "2_2") (pintype "passive"))
      (node (ref "C63") (pin "2") (pinfunction "2_2") (pintype "passive"))
      (node (ref "C64") (pin "2") (pinfunction "2_2") (pintype "passive"))
      (node (ref "C65") (pin "1") (pinfunction "1_1") (pintype "passive"))
      (node (ref "C66") (pin "1") (pinfunction "1_1") (pintype "passive"))
      (node (ref "C67") (pin "1") (pinfunction "1_1") (pintype "passive"))
      (node (ref "C68") (pin "1") (pinfunction "1_1") (pintype "passive"))
      (node (ref "C69") (pin "1") (pinfunction "1_1") (pintype "passive"))
      (node (ref "C6R") (pin "2") (pinfunction "2_2") (pintype "passive"))
      (node (ref "C6T") (pin "2") (pinfunction "2_2") (pintype "passive"))
      (node (ref "C7") (pin "2") (pinfunction "2_2") (pintype "passive"))
      (node (ref "C74") (pin "2") (pinfunction "2_2") (pintype "passive"))
      (node (ref "C75") (pin "2") (pinfunction "2_2") (pintype "passive"))
      (node (ref "C76") (pin "2") (pinfunction "2_2") (pintype "passive"))
      (node (ref "C77") (pin "2") (pinfunction "2_2") (pintype "passive"))
      (node (ref "C78") (pin "2") (pinfunction "2_2") (pintype "passive"))
      (node (ref "C79") (pin "2") (pinfunction "2_2") (pintype "passive"))
      (node (ref "C7R") (pin "2") (pinfunction "2_2") (pintype "passive"))
      (node (ref "C7T") (pin "2") (pinfunction "2_2") (pintype "passive"))
      (node (ref "C8") (pin "2") (pinfunction "2_2") (pintype "passive"))
      (node (ref "C80") (pin "2") (pinfunction "2_2") (pintype "passive"))
      (node (ref "C81") (pin "2") (pinfunction "2_2") (pintype "passive"))
      (node (ref "C82") (pin "2") (pinfunction "2_2") (pintype "passive"))
      (node (ref "C83") (pin "2") (pinfunction "2_2") (pintype "passive"))
      (node (ref "C84") (pin "1") (pinfunction "1_1") (pintype "passive"))
      (node (ref "C85") (pin "2") (pinfunction "2_2") (pintype "passive"))
      (node (ref "C86") (pin "1") (pinfunction "1_1") (pintype "passive"))
      (node (ref "C87") (pin "1") (pinfunction "1_1") (pintype "passive"))
      (node (ref "C88") (pin "-") (pinfunction "-_-") (pintype "passive"))
      (node (ref "C89") (pin "-") (pinfunction "-_-") (pintype "passive"))
      (node (ref "C8R") (pin "2") (pinfunction "2_2") (pintype "passive"))
      (node (ref "C8T") (pin "2") (pinfunction "2_2") (pintype "passive"))
      (node (ref "C9") (pin "2") (pinfunction "2_2") (pintype "passive"))
      (node (ref "C90") (pin "1") (pinfunction "1_1") (pintype "passive"))
      (node (ref "C91") (pin "1") (pinfunction "1_1") (pintype "passive"))
      (node (ref "C93") (pin "2") (pinfunction "2_2") (pintype "passive"))
      (node (ref "C94") (pin "2") (pinfunction "2_2") (pintype "passive"))
      (node (ref "C95") (pin "2") (pinfunction "2_2") (pintype "passive"))
      (node (ref "C96") (pin "2") (pinfunction "2_2") (pintype "passive"))
      (node (ref "C97") (pin "2") (pinfunction "2_2") (pintype "passive"))
      (node (ref "C98") (pin "2") (pinfunction "2_2") (pintype "passive"))
      (node (ref "C99") (pin "2") (pinfunction "2_2") (pintype "passive"))
      (node (ref "C9R") (pin "2") (pinfunction "2_2") (pintype "passive"))
      (node (ref "C9T") (pin "2") (pinfunction "2_2") (pintype "passive"))
      (node (ref "IC1") (pin "17") (pinfunction "AGND_17") (pintype "bidirectional"))
      (node (ref "IC1") (pin "3") (pinfunction "AD0_3") (pintype "bidirectional"))
      (node (ref "IC1") (pin "35") (pinfunction "DGND_35") (pintype "bidirectional"))
      (node (ref "IC1") (pin "41") (pinfunction "EP_(GND)_41") (pintype "bidirectional"))
      (node (ref "IC10") (pin "2") (pinfunction "GND_2") (pintype "bidirectional"))
      (node (ref "IC11") (pin "6") (pinfunction "GND_6") (pintype "bidirectional"))
      (node (ref "IC11") (pin "9") (pinfunction "EP_9") (pintype "bidirectional"))
      (node (ref "IC12") (pin "4") (pinfunction "GND_4") (pintype "bidirectional"))
      (node (ref "IC12") (pin "9") (pinfunction "EP_9") (pintype "bidirectional"))
      (node (ref "IC13") (pin "11") (pinfunction "VSS_11") (pintype "bidirectional"))
      (node (ref "IC2") (pin "2") (pinfunction "GND_2") (pintype "bidirectional"))
      (node (ref "IC3") (pin "2") (pinfunction "GND_2") (pintype "bidirectional"))
      (node (ref "IC4") (pin "6") (pinfunction "GND_6") (pintype "bidirectional"))
      (node (ref "IC4") (pin "9") (pinfunction "EP_9") (pintype "bidirectional"))
      (node (ref "IC5") (pin "11") (pinfunction "VREFGND_11") (pintype "bidirectional"))
      (node (ref "IC5") (pin "14") (pinfunction "AGND_14") (pintype "bidirectional"))
      (node (ref "IC5") (pin "4") (pinfunction "DGND_4") (pintype "bidirectional"))
      (node (ref "IC6") (pin "23") (pinfunction "VSS_1_23") (pintype "bidirectional"))
      (node (ref "IC6") (pin "35") (pinfunction "VSS_2_35") (pintype "bidirectional"))
      (node (ref "IC6") (pin "47") (pinfunction "VSS_3_47") (pintype "bidirectional"))
      (node (ref "IC6") (pin "8") (pinfunction "VSSA_8") (pintype "bidirectional"))
      (node (ref "IC7") (pin "11") (pinfunction "VSS_11") (pintype "bidirectional"))
      (node (ref "IC8") (pin "2") (pinfunction "GND_2") (pintype "bidirectional"))
      (node (ref "IC8") (pin "3") (pinfunction "~{EN}_3") (pintype "bidirectional"))
      (node (ref "IC9") (pin "11") (pinfunction "VSS_11") (pintype "bidirectional"))
      (node (ref "J1") (pin "1") (pinfunction "1_1") (pintype "bidirectional"))
      (node (ref "J1") (pin "4") (pinfunction "4_4") (pintype "bidirectional"))
      (node (ref "J1") (pin "5") (pinfunction "5_5") (pintype "bidirectional"))
      (node (ref "J10") (pin "5") (pinfunction "GND_5") (pintype "power_in"))
      (node (ref "J10") (pin "6") (pinfunction "SHIELD_6") (pintype "passive"))
      (node (ref "J10") (pin "7") (pinfunction "SHIELD_7") (pintype "passive"))
      (node (ref "J10") (pin "8") (pinfunction "SHIELD_8") (pintype "passive"))
      (node (ref "J10") (pin "9") (pinfunction "SHIELD_9") (pintype "passive"))
      (node (ref "J10") (pin "S1") (pinfunction "SHIELD_S1") (pintype "passive"))
      (node (ref "J10") (pin "S2") (pinfunction "SHIELD_S2") (pintype "passive"))
      (node (ref "J11") (pin "2") (pinfunction "2_2") (pintype "bidirectional"))
      (node (ref "J11") (pin "3") (pinfunction "3_3") (pintype "bidirectional"))
      (node (ref "J12") (pin "3") (pinfunction "VSS1_3") (pintype "bidirectional"))
      (node (ref "J12") (pin "6") (pinfunction "VSS2_6") (pintype "bidirectional"))
      (node (ref "J12") (pin "MP1") (pinfunction "MP1_MP1") (pintype "bidirectional"))
      (node (ref "J12") (pin "MP2") (pinfunction "MP2_MP2") (pintype "bidirectional"))
      (node (ref "J12") (pin "MP3") (pinfunction "MP3_MP3") (pintype "bidirectional"))
      (node (ref "J12") (pin "MP4") (pinfunction "MP4_MP4") (pintype "bidirectional"))
      (node (ref "J13") (pin "3") (pinfunction "3_3") (pintype "bidirectional"))
      (node (ref "J13") (pin "5") (pinfunction "5_5") (pintype "bidirectional"))
      (node (ref "J13") (pin "9") (pinfunction "9_9") (pintype "bidirectional"))
      (node (ref "J14") (pin "3") (pinfunction "3_3") (pintype "bidirectional"))
      (node (ref "J14") (pin "5") (pinfunction "5_5") (pintype "bidirectional"))
      (node (ref "J14") (pin "9") (pinfunction "9_9") (pintype "bidirectional"))
      (node (ref "J2") (pin "1") (pinfunction "1_1") (pintype "bidirectional"))
      (node (ref "J2") (pin "4") (pinfunction "4_4") (pintype "bidirectional"))
      (node (ref "J2") (pin "5") (pinfunction "5_5") (pintype "bidirectional"))
      (node (ref "J3") (pin "1") (pinfunction "1_1") (pintype "bidirectional"))
      (node (ref "J3") (pin "4") (pinfunction "4_4") (pintype "bidirectional"))
      (node (ref "J3") (pin "5") (pinfunction "5_5") (pintype "bidirectional"))
      (node (ref "J4") (pin "1") (pinfunction "1_1") (pintype "bidirectional"))
      (node (ref "J4") (pin "4") (pinfunction "4_4") (pintype "bidirectional"))
      (node (ref "J4") (pin "5") (pinfunction "5_5") (pintype "bidirectional"))
      (node (ref "J5") (pin "1") (pinfunction "1_1") (pintype "bidirectional"))
      (node (ref "J5") (pin "4") (pinfunction "4_4") (pintype "bidirectional"))
      (node (ref "J5") (pin "5") (pinfunction "5_5") (pintype "bidirectional"))
      (node (ref "J6") (pin "1") (pinfunction "1_1") (pintype "bidirectional"))
      (node (ref "J6") (pin "4") (pinfunction "4_4") (pintype "bidirectional"))
      (node (ref "J6") (pin "5") (pinfunction "5_5") (pintype "bidirectional"))
      (node (ref "J7") (pin "1") (pinfunction "1_1") (pintype "bidirectional"))
      (node (ref "J7") (pin "4") (pinfunction "4_4") (pintype "bidirectional"))
      (node (ref "J7") (pin "5") (pinfunction "5_5") (pintype "bidirectional"))
      (node (ref "J8") (pin "1") (pinfunction "1_1") (pintype "bidirectional"))
      (node (ref "J8") (pin "4") (pinfunction "4_4") (pintype "bidirectional"))
      (node (ref "J8") (pin "5") (pinfunction "5_5") (pintype "bidirectional"))
      (node (ref "J9") (pin "1") (pinfunction "1_1") (pintype "bidirectional"))
      (node (ref "J9") (pin "4") (pinfunction "4_4") (pintype "bidirectional"))
      (node (ref "J9") (pin "5") (pinfunction "5_5") (pintype "bidirectional"))
      (node (ref "JADC") (pin "1") (pinfunction "S_1") (pintype "bidirectional"))
      (node (ref "JADC") (pin "4") (pinfunction "SG_4") (pintype "bidirectional"))
      (node (ref "JADC") (pin "5") (pinfunction "RG_5") (pintype "bidirectional"))
      (node (ref "JADC") (pin "6") (pinfunction "TG_6") (pintype "bidirectional"))
      (node (ref "JHP") (pin "1") (pinfunction "1_1") (pintype "bidirectional"))
      (node (ref "JHP") (pin "4") (pinfunction "4_4") (pintype "bidirectional"))
      (node (ref "JHP") (pin "5") (pinfunction "5_5") (pintype "bidirectional"))
      (node (ref "JIN1") (pin "GND") (pinfunction "GND_GND") (pintype "bidirectional"))
      (node (ref "JIN2") (pin "GND") (pinfunction "GND_GND") (pintype "bidirectional"))
      (node (ref "JIN3") (pin "GND") (pinfunction "GND_GND") (pintype "bidirectional"))
      (node (ref "JIN4") (pin "GND") (pinfunction "GND_GND") (pintype "bidirectional"))
      (node (ref "JOUT") (pin "1") (pinfunction "S_1") (pintype "bidirectional"))
      (node (ref "JOUT") (pin "4") (pinfunction "SG_4") (pintype "bidirectional"))
      (node (ref "JOUT") (pin "5") (pinfunction "RG_5") (pintype "bidirectional"))
      (node (ref "JOUT") (pin "6") (pinfunction "TG_6") (pintype "bidirectional"))
      (node (ref "LED10") (pin "C") (pinfunction "C_C") (pintype "passive"))
      (node (ref "LED11") (pin "C") (pinfunction "C_C") (pintype "passive"))
      (node (ref "LED12") (pin "C") (pinfunction "C_C") (pintype "passive"))
      (node (ref "R1") (pin "1") (pinfunction "1_1") (pintype "passive"))
      (node (ref "R14") (pin "1") (pinfunction "1_1") (pintype "passive"))
      (node (ref "R15") (pin "3") (pinfunction "3_3") (pintype "bidirectional"))
      (node (ref "R15") (pin "4") (pinfunction "4_4") (pintype "bidirectional"))
      (node (ref "R15") (pin "5") (pinfunction "5_5") (pintype "bidirectional"))
      (node (ref "R17") (pin "3") (pinfunction "3_3") (pintype "bidirectional"))
      (node (ref "R17") (pin "4") (pinfunction "4_4") (pintype "bidirectional"))
      (node (ref "R17") (pin "5") (pinfunction "5_5") (pintype "bidirectional"))
      (node (ref "R19") (pin "2") (pinfunction "2_2") (pintype "passive"))
      (node (ref "R2") (pin "1") (pinfunction "1_1") (pintype "passive"))
      (node (ref "R21") (pin "2") (pinfunction "2_2") (pintype "passive"))
      (node (ref "R23") (pin "2") (pinfunction "2_2") (pintype "passive"))
      (node (ref "R24") (pin "1") (pinfunction "1_1") (pintype "passive"))
      (node (ref "R25") (pin "1") (pinfunction "1_1") (pintype "passive"))
      (node (ref "R26") (pin "1") (pinfunction "1_1") (pintype "passive"))
      (node (ref "R32") (pin "2") (pinfunction "2_2") (pintype "passive"))
      (node (ref "R33") (pin "1") (pinfunction "1_1") (pintype "passive"))
      (node (ref "R34") (pin "1") (pinfunction "1_1") (pintype "passive"))
      (node (ref "R35") (pin "1") (pinfunction "1_1") (pintype "passive"))
      (node (ref "R36") (pin "1") (pinfunction "1_1") (pintype "passive"))
      (node (ref "R37") (pin "1") (pinfunction "1_1") (pintype "passive"))
      (node (ref "R38") (pin "1") (pinfunction "1_1") (pintype "passive"))
      (node (ref "R39") (pin "1") (pinfunction "1_1") (pintype "passive"))
      (node (ref "R40") (pin "1") (pinfunction "1_1") (pintype "passive"))
      (node (ref "R41") (pin "2") (pinfunction "2_2") (pintype "passive"))
      (node (ref "R42") (pin "1") (pinfunction "1_1") (pintype "passive"))
      (node (ref "R44") (pin "1") (pinfunction "1_1") (pintype "passive"))
      (node (ref "R46") (pin "3") (pinfunction "3_3") (pintype "bidirectional"))
      (node (ref "R46") (pin "4") (pinfunction "4_4") (pintype "bidirectional"))
      (node (ref "R46") (pin "5") (pinfunction "5_5") (pintype "bidirectional"))
      (node (ref "R47") (pin "3") (pinfunction "3_3") (pintype "bidirectional"))
      (node (ref "R47") (pin "4") (pinfunction "4_4") (pintype "bidirectional"))
      (node (ref "R47") (pin "5") (pinfunction "5_5") (pintype "bidirectional"))
      (node (ref "RLED1") (pin "2") (pinfunction "2_2") (pintype "passive"))
      (node (ref "RLED11") (pin "2") (pinfunction "2_2") (pintype "passive"))
      (node (ref "RLED13") (pin "2") (pinfunction "2_2") (pintype "passive"))
      (node (ref "RLED15") (pin "2") (pinfunction "2_2") (pintype "passive"))
      (node (ref "RLED17") (pin "2") (pinfunction "2_2") (pintype "passive"))
      (node (ref "RLED3") (pin "2") (pinfunction "2_2") (pintype "passive"))
      (node (ref "RLED5") (pin "2") (pinfunction "2_2") (pintype "passive"))
      (node (ref "RLED7") (pin "2") (pinfunction "2_2") (pintype "passive"))
      (node (ref "RLED9") (pin "2") (pinfunction "2_2") (pintype "passive"))
      (node (ref "S10") (pin "2") (pinfunction "GND_2") (pintype "bidirectional"))
      (node (ref "U$2") (pin "GND") (pinfunction "GND_GND") (pintype "bidirectional"))
      (node (ref "U1") (pin "10") (pinfunction "VSS_2_10") (pintype "power_in"))
      (node (ref "U1") (pin "20") (pinfunction "VSSA_20") (pintype "power_in"))
      (node (ref "U1") (pin "27") (pinfunction "VSS_3_27") (pintype "power_in"))
      (node (ref "U1") (pin "74") (pinfunction "VSS_4_74") (pintype "power_in"))
      (node (ref "U1") (pin "99") (pinfunction "VSS_99") (pintype "power_in"))
      (node (ref "USBHA") (pin "5") (pinfunction "GND_5") (pintype "power_in"))
      (node (ref "USBHA") (pin "6") (pinfunction "SHIELD_6") (pintype "passive"))
      (node (ref "USBHA") (pin "7") (pinfunction "SHIELD_7") (pintype "passive"))
      (node (ref "USBHA") (pin "8") (pinfunction "SHIELD_8") (pintype "passive"))
      (node (ref "USBHA") (pin "9") (pinfunction "SHIELD_9") (pintype "passive"))
      (node (ref "USBHA") (pin "S1") (pinfunction "SHIELD_S1") (pintype "passive"))
      (node (ref "USBHA") (pin "S2") (pinfunction "SHIELD_S2") (pintype "passive"))
      (node (ref "USBHB") (pin "4") (pinfunction "GND_4") (pintype "bidirectional"))
      (node (ref "USBHB") (pin "5") (pinfunction "MH1_5") (pintype "bidirectional"))
      (node (ref "USBHB") (pin "6") (pinfunction "MH2_6") (pintype "bidirectional"))
      (node (ref "VR1") (pin "2") (pinfunction "2_2") (pintype "bidirectional"))
      (node (ref "VR1") (pin "C1") (pinfunction "C_C1") (pintype "bidirectional"))
      (node (ref "VR1") (pin "MH1") (pinfunction "MH1_MH1") (pintype "bidirectional"))
      (node (ref "VR1") (pin "MH2") (pinfunction "MH2_MH2") (pintype "bidirectional"))
      (node (ref "VR2") (pin "2") (pinfunction "2_2") (pintype "bidirectional"))
      (node (ref "VR2") (pin "C1") (pinfunction "C_C1") (pintype "bidirectional"))
      (node (ref "VR2") (pin "MH1") (pinfunction "MH1_MH1") (pintype "bidirectional"))
      (node (ref "VR2") (pin "MH2") (pinfunction "MH2_MH2") (pintype "bidirectional"))
      (node (ref "X2") (pin "1") (pinfunction "1_1") (pintype "passive"))
      (node (ref "X3") (pin "2") (pinfunction "1_2") (pintype "passive"))
      (node (ref "X5") (pin "2") (pinfunction "1_2") (pintype "passive"))
      (node (ref "Z1R") (pin "2") (pinfunction "A_2") (pintype "bidirectional"))
      (node (ref "Z1T") (pin "2") (pinfunction "A_2") (pintype "bidirectional"))
      (node (ref "Z2R") (pin "2") (pinfunction "A_2") (pintype "bidirectional"))
      (node (ref "Z2T") (pin "2") (pinfunction "A_2") (pintype "bidirectional"))
      (node (ref "Z3R") (pin "2") (pinfunction "A_2") (pintype "bidirectional"))
      (node (ref "Z3T") (pin "2") (pinfunction "A_2") (pintype "bidirectional"))
      (node (ref "Z4R") (pin "2") (pinfunction "A_2") (pintype "bidirectional"))
      (node (ref "Z4T") (pin "2") (pinfunction "A_2") (pintype "bidirectional"))
      (node (ref "Z5R") (pin "2") (pinfunction "A_2") (pintype "bidirectional"))
      (node (ref "Z5T") (pin "2") (pinfunction "A_2") (pintype "bidirectional"))
      (node (ref "Z6R") (pin "2") (pinfunction "A_2") (pintype "bidirectional"))
      (node (ref "Z6T") (pin "2") (pinfunction "A_2") (pintype "bidirectional"))
      (node (ref "Z7R") (pin "2") (pinfunction "A_2") (pintype "bidirectional"))
      (node (ref "Z7T") (pin "2") (pinfunction "A_2") (pintype "bidirectional"))
      (node (ref "Z8R") (pin "2") (pinfunction "A_2") (pintype "bidirectional"))
      (node (ref "Z8T") (pin "2") (pinfunction "A_2") (pintype "bidirectional"))
      (node (ref "Z9R") (pin "2") (pinfunction "A_2") (pintype "bidirectional"))
      (node (ref "Z9T") (pin "2") (pinfunction "A_2") (pintype "bidirectional"))
    )
    (net (code "51") (name "INL") (class "Default")
      (node (ref "C47") (pin "-") (pinfunction "-_-") (pintype "passive"))
      (node (ref "C49") (pin "2") (pinfunction "2_2") (pintype "passive"))
      (node (ref "JADC") (pin "2") (pinfunction "R_2") (pintype "bidirectional"))
    )
    (net (code "52") (name "INR") (class "Default")
      (node (ref "C48") (pin "-") (pinfunction "-_-") (pintype "passive"))
      (node (ref "C50") (pin "2") (pinfunction "2_2") (pintype "passive"))
      (node (ref "JADC") (pin "3") (pinfunction "T_3") (pintype "bidirectional"))
    )
    (net (code "53") (name "KNOB1") (class "Default")
      (node (ref "C103") (pin "1") (pinfunction "1_1") (pintype "passive"))
      (node (ref "R15") (pin "2") (pinfunction "2_2") (pintype "bidirectional"))
      (node (ref "U1") (pin "34") (pinfunction "PC5_34") (pintype "bidirectional"))
    )
    (net (code "54") (name "KNOB2") (class "Default")
      (node (ref "C102") (pin "1") (pinfunction "1_1") (pintype "passive"))
      (node (ref "R17") (pin "2") (pinfunction "2_2") (pintype "bidirectional"))
      (node (ref "U1") (pin "36") (pinfunction "PB1_36") (pintype "bidirectional"))
    )
    (net (code "55") (name "KNOB3") (class "Default")
      (node (ref "C105") (pin "1") (pinfunction "1_1") (pintype "passive"))
      (node (ref "R46") (pin "2") (pinfunction "2_2") (pintype "bidirectional"))
      (node (ref "U1") (pin "15") (pinfunction "PC0_15") (pintype "bidirectional"))
    )
    (net (code "56") (name "KNOB4") (class "Default")
      (node (ref "C104") (pin "1") (pinfunction "1_1") (pintype "passive"))
      (node (ref "R47") (pin "2") (pinfunction "2_2") (pintype "bidirectional"))
      (node (ref "U1") (pin "35") (pinfunction "PB0_35") (pintype "bidirectional"))
    )
    (net (code "57") (name "LD1") (class "Default")
      (node (ref "R58") (pin "1") (pinfunction "1_1") (pintype "passive"))
      (node (ref "U1") (pin "84") (pinfunction "PD3_84") (pintype "bidirectional"))
    )
    (net (code "58") (name "LD2") (class "Default")
      (node (ref "R57") (pin "1") (pinfunction "1_1") (pintype "passive"))
      (node (ref "U1") (pin "85") (pinfunction "PD4_85") (pintype "bidirectional"))
    )
    (net (code "59") (name "LED1") (class "Default")
      (node (ref "IC6") (pin "28") (pinfunction "PB15_28") (pintype "bidirectional"))
      (node (ref "LEDA1") (pin "1") (pinfunction "K_1") (pintype "bidirectional"))
      (node (ref "LEDB1") (pin "C") (pinfunction "C_C") (pintype "passive"))
      (node (ref "LEDC1") (pin "1") (pinfunction "K_1") (pintype "bidirectional"))
      (node (ref "LEDD1") (pin "C") (pinfunction "C_C") (pintype "passive"))
    )
    (net (code "60") (name "LED2") (class "Default")
      (node (ref "IC6") (pin "25") (pinfunction "PB12_25") (pintype "bidirectional"))
      (node (ref "LEDA3") (pin "1") (pinfunction "K_1") (pintype "bidirectional"))
      (node (ref "LEDB3") (pin "C") (pinfunction "C_C") (pintype "passive"))
      (node (ref "LEDC3") (pin "1") (pinfunction "K_1") (pintype "bidirectional"))
      (node (ref "LEDD3") (pin "C") (pinfunction "C_C") (pintype "passive"))
    )
    (net (code "61") (name "LED3") (class "Default")
      (node (ref "IC6") (pin "19") (pinfunction "PB1_19") (pintype "bidirectional"))
      (node (ref "LEDA5") (pin "1") (pinfunction "K_1") (pintype "bidirectional"))
      (node (ref "LEDB5") (pin "C") (pinfunction "C_C") (pintype "passive"))
      (node (ref "LEDC5") (pin "1") (pinfunction "K_1") (pintype "bidirectional"))
      (node (ref "LEDD5") (pin "C") (pinfunction "C_C") (pintype "passive"))
    )
    (net (code "62") (name "LED4") (class "Default")
      (node (ref "IC6") (pin "17") (pinfunction "PA7_17") (pintype "bidirectional"))
      (node (ref "LEDA7") (pin "1") (pinfunction "K_1") (pintype "bidirectional"))
      (node (ref "LEDB7") (pin "C") (pinfunction "C_C") (pintype "passive"))
      (node (ref "LEDC7") (pin "1") (pinfunction "K_1") (pintype "bidirectional"))
      (node (ref "LEDD7") (pin "C") (pinfunction "C_C") (pintype "passive"))
    )
    (net (code "63") (name "LED5") (class "Default")
      (node (ref "IC6") (pin "15") (pinfunction "PA5_15") (pintype "bidirectional"))
      (node (ref "LEDA9") (pin "1") (pinfunction "K_1") (pintype "bidirectional"))
      (node (ref "LEDB9") (pin "C") (pinfunction "C_C") (pintype "passive"))
      (node (ref "LEDC9") (pin "1") (pinfunction "K_1") (pintype "bidirectional"))
      (node (ref "LEDD9") (pin "C") (pinfunction "C_C") (pintype "passive"))
    )
    (net (code "64") (name "LED6") (class "Default")
      (node (ref "IC6") (pin "13") (pinfunction "PA3_13") (pintype "bidirectional"))
      (node (ref "LEDA11") (pin "1") (pinfunction "K_1") (pintype "bidirectional"))
      (node (ref "LEDB11") (pin "C") (pinfunction "C_C") (pintype "passive"))
      (node (ref "LEDC11") (pin "1") (pinfunction "K_1") (pintype "bidirectional"))
      (node (ref "LEDD11") (pin "C") (pinfunction "C_C") (pintype "passive"))
    )
    (net (code "65") (name "LED7") (class "Default")
      (node (ref "LEDA13") (pin "1") (pinfunction "K_1") (pintype "bidirectional"))
      (node (ref "LEDB13") (pin "C") (pinfunction "C_C") (pintype "passive"))
      (node (ref "LEDC13") (pin "1") (pinfunction "K_1") (pintype "bidirectional"))
      (node (ref "LEDD13") (pin "C") (pinfunction "C_C") (pintype "passive"))
      (node (ref "R60") (pin "2") (pinfunction "2_2") (pintype "passive"))
    )
    (net (code "66") (name "LED8") (class "Default")
      (node (ref "LEDA15") (pin "1") (pinfunction "K_1") (pintype "bidirectional"))
      (node (ref "LEDB15") (pin "C") (pinfunction "C_C") (pintype "passive"))
      (node (ref "LEDC15") (pin "1") (pinfunction "K_1") (pintype "bidirectional"))
      (node (ref "LEDD15") (pin "C") (pinfunction "C_C") (pintype "passive"))
      (node (ref "R55") (pin "2") (pinfunction "2_2") (pintype "passive"))
    )
    (net (code "67") (name "LED9") (class "Default")
      (node (ref "LEDA17") (pin "1") (pinfunction "K_1") (pintype "bidirectional"))
      (node (ref "LEDB17") (pin "C") (pinfunction "C_C") (pintype "passive"))
      (node (ref "LEDC17") (pin "1") (pinfunction "K_1") (pintype "bidirectional"))
      (node (ref "LEDD17") (pin "C") (pinfunction "C_C") (pintype "passive"))
      (node (ref "R61") (pin "2") (pinfunction "2_2") (pintype "passive"))
    )
    (net (code "68") (name "LIN1") (class "Default")
      (node (ref "C73") (pin "1") (pinfunction "1_1") (pintype "passive"))
      (node (ref "R4") (pin "1") (pinfunction "1_1") (pintype "passive"))
    )
    (net (code "69") (name "LIN2") (class "Default")
      (node (ref "C72") (pin "1") (pinfunction "1_1") (pintype "passive"))
      (node (ref "R5") (pin "1") (pinfunction "1_1") (pintype "passive"))
    )
    (net (code "70") (name "LIN3") (class "Default")
      (node (ref "C71") (pin "1") (pinfunction "1_1") (pintype "passive"))
      (node (ref "R8") (pin "1") (pinfunction "1_1") (pintype "passive"))
    )
    (net (code "71") (name "LIN4") (class "Default")
      (node (ref "C70") (pin "1") (pinfunction "1_1") (pintype "passive"))
      (node (ref "R9") (pin "1") (pinfunction "1_1") (pintype "passive"))
    )
    (net (code "72") (name "LIN5") (class "Default")
      (node (ref "C31") (pin "1") (pinfunction "1_1") (pintype "passive"))
      (node (ref "R10") (pin "1") (pinfunction "1_1") (pintype "passive"))
    )
    (net (code "73") (name "LIN6") (class "Default")
      (node (ref "C30") (pin "1") (pinfunction "1_1") (pintype "passive"))
      (node (ref "R11") (pin "1") (pinfunction "1_1") (pintype "passive"))
    )
    (net (code "74") (name "LIN7") (class "Default")
      (node (ref "C29") (pin "1") (pinfunction "1_1") (pintype "passive"))
      (node (ref "R12") (pin "1") (pinfunction "1_1") (pintype "passive"))
    )
    (net (code "75") (name "LIN8") (class "Default")
      (node (ref "C28") (pin "1") (pinfunction "1_1") (pintype "passive"))
      (node (ref "R13") (pin "1") (pinfunction "1_1") (pintype "passive"))
    )
    (net (code "76") (name "Net-(C25-Pad2)") (class "Default")
      (node (ref "C25") (pin "2") (pinfunction "2_2") (pintype "passive"))
      (node (ref "R1") (pin "2") (pinfunction "2_2") (pintype "passive"))
    )
    (net (code "77") (name "Net-(C26-Pad2)") (class "Default")
      (node (ref "C26") (pin "2") (pinfunction "2_2") (pintype "passive"))
      (node (ref "R2") (pin "2") (pinfunction "2_2") (pintype "passive"))
    )
    (net (code "78") (name "Net-(C28-Pad2)") (class "Default")
      (node (ref "C28") (pin "2") (pinfunction "2_2") (pintype "passive"))
      (node (ref "JIN4") (pin "TIP") (pinfunction "TIP_TIP") (pintype "bidirectional"))
      (node (ref "R33") (pin "2") (pinfunction "2_2") (pintype "passive"))
    )
    (net (code "79") (name "Net-(C29-Pad2)") (class "Default")
      (node (ref "C29") (pin "2") (pinfunction "2_2") (pintype "passive"))
      (node (ref "JIN4") (pin "RING") (pinfunction "RING_RING") (pintype "bidirectional"))
      (node (ref "R34") (pin "2") (pinfunction "2_2") (pintype "passive"))
    )
    (net (code "80") (name "Net-(C30-Pad2)") (class "Default")
      (node (ref "C30") (pin "2") (pinfunction "2_2") (pintype "passive"))
      (node (ref "JIN3") (pin "TIP") (pinfunction "TIP_TIP") (pintype "bidirectional"))
      (node (ref "R35") (pin "2") (pinfunction "2_2") (pintype "passive"))
    )
    (net (code "81") (name "Net-(C31-Pad2)") (class "Default")
      (node (ref "C31") (pin "2") (pinfunction "2_2") (pintype "passive"))
      (node (ref "JIN3") (pin "RING") (pinfunction "RING_RING") (pintype "bidirectional"))
      (node (ref "R36") (pin "2") (pinfunction "2_2") (pintype "passive"))
    )
    (net (code "82") (name "Net-(C47-Pad+)") (class "Default")
      (node (ref "C47") (pin "+") (pinfunction "+_+") (pintype "passive"))
      (node (ref "C49") (pin "1") (pinfunction "1_1") (pintype "passive"))
      (node (ref "R28") (pin "1") (pinfunction "1_1") (pintype "passive"))
    )
    (net (code "83") (name "Net-(C48-Pad+)") (class "Default")
      (node (ref "C48") (pin "+") (pinfunction "+_+") (pintype "passive"))
      (node (ref "C50") (pin "1") (pinfunction "1_1") (pintype "passive"))
      (node (ref "R31") (pin "1") (pinfunction "1_1") (pintype "passive"))
    )
    (net (code "84") (name "Net-(C70-Pad2)") (class "Default")
      (node (ref "C70") (pin "2") (pinfunction "2_2") (pintype "passive"))
      (node (ref "JIN2") (pin "TIP") (pinfunction "TIP_TIP") (pintype "bidirectional"))
      (node (ref "R37") (pin "2") (pinfunction "2_2") (pintype "passive"))
    )
    (net (code "85") (name "Net-(C71-Pad2)") (class "Default")
      (node (ref "C71") (pin "2") (pinfunction "2_2") (pintype "passive"))
      (node (ref "JIN2") (pin "RING") (pinfunction "RING_RING") (pintype "bidirectional"))
      (node (ref "R38") (pin "2") (pinfunction "2_2") (pintype "passive"))
    )
    (net (code "86") (name "Net-(C72-Pad2)") (class "Default")
      (node (ref "C72") (pin "2") (pinfunction "2_2") (pintype "passive"))
      (node (ref "JIN1") (pin "TIP") (pinfunction "TIP_TIP") (pintype "bidirectional"))
      (node (ref "R39") (pin "2") (pinfunction "2_2") (pintype "passive"))
    )
    (net (code "87") (name "Net-(C73-Pad2)") (class "Default")
      (node (ref "C73") (pin "2") (pinfunction "2_2") (pintype "passive"))
      (node (ref "JIN1") (pin "RING") (pinfunction "RING_RING") (pintype "bidirectional"))
      (node (ref "R40") (pin "2") (pinfunction "2_2") (pintype "passive"))
    )
    (net (code "88") (name "Net-(D1R-A)") (class "Default")
      (node (ref "D1R") (pin "2") (pinfunction "A_2") (pintype "bidirectional"))
      (node (ref "J1") (pin "3") (pinfunction "3_3") (pintype "bidirectional"))
    )
    (net (code "89") (name "Net-(D1R-K)") (class "Default")
      (node (ref "D1R") (pin "1") (pinfunction "K_1") (pintype "bidirectional"))
      (node (ref "R1R") (pin "2") (pinfunction "2_2") (pintype "passive"))
      (node (ref "Z1R") (pin "1") (pinfunction "K_1") (pintype "bidirectional"))
    )
    (net (code "90") (name "Net-(D1R1-A)") (class "Default")
      (node (ref "D1R1") (pin "2") (pinfunction "A_2") (pintype "bidirectional"))
      (node (ref "J10") (pin "1") (pinfunction "VCC_1") (pintype "power_in"))
    )
    (net (code "91") (name "Net-(D1T-A)") (class "Default")
      (node (ref "D1T") (pin "2") (pinfunction "A_2") (pintype "bidirectional"))
      (node (ref "J1") (pin "2") (pinfunction "2_2") (pintype "bidirectional"))
    )
    (net (code "92") (name "Net-(D1T-K)") (class "Default")
      (node (ref "D1T") (pin "1") (pinfunction "K_1") (pintype "bidirectional"))
      (node (ref "R1T") (pin "2") (pinfunction "2_2") (pintype "passive"))
      (node (ref "Z1T") (pin "1") (pinfunction "K_1") (pintype "bidirectional"))
    )
    (net (code "93") (name "Net-(D2R-A)") (class "Default")
      (node (ref "D2R") (pin "2") (pinfunction "A_2") (pintype "bidirectional"))
      (node (ref "J2") (pin "3") (pinfunction "3_3") (pintype "bidirectional"))
    )
    (net (code "94") (name "Net-(D2R-K)") (class "Default")
      (node (ref "D2R") (pin "1") (pinfunction "K_1") (pintype "bidirectional"))
      (node (ref "R2R") (pin "2") (pinfunction "2_2") (pintype "passive"))
      (node (ref "Z2R") (pin "1") (pinfunction "K_1") (pintype "bidirectional"))
    )
    (net (code "95") (name "Net-(D2T-A)") (class "Default")
      (node (ref "D2T") (pin "2") (pinfunction "A_2") (pintype "bidirectional"))
      (node (ref "J2") (pin "2") (pinfunction "2_2") (pintype "bidirectional"))
    )
    (net (code "96") (name "Net-(D2T-K)") (class "Default")
      (node (ref "D2T") (pin "1") (pinfunction "K_1") (pintype "bidirectional"))
      (node (ref "R2T") (pin "2") (pinfunction "2_2") (pintype "passive"))
      (node (ref "Z2T") (pin "1") (pinfunction "K_1") (pintype "bidirectional"))
    )
    (net (code "97") (name "Net-(D3R-A)") (class "Default")
      (node (ref "D3R") (pin "2") (pinfunction "A_2") (pintype "bidirectional"))
      (node (ref "J3") (pin "3") (pinfunction "3_3") (pintype "bidirectional"))
    )
    (net (code "98") (name "Net-(D3R-K)") (class "Default")
      (node (ref "D3R") (pin "1") (pinfunction "K_1") (pintype "bidirectional"))
      (node (ref "R3R") (pin "2") (pinfunction "2_2") (pintype "passive"))
      (node (ref "Z3R") (pin "1") (pinfunction "K_1") (pintype "bidirectional"))
    )
    (net (code "99") (name "Net-(D3T-A)") (class "Default")
      (node (ref "D3T") (pin "2") (pinfunction "A_2") (pintype "bidirectional"))
      (node (ref "J3") (pin "2") (pinfunction "2_2") (pintype "bidirectional"))
    )
    (net (code "100") (name "Net-(D3T-K)") (class "Default")
      (node (ref "D3T") (pin "1") (pinfunction "K_1") (pintype "bidirectional"))
      (node (ref "R3T") (pin "2") (pinfunction "2_2") (pintype "passive"))
      (node (ref "Z3T") (pin "1") (pinfunction "K_1") (pintype "bidirectional"))
    )
    (net (code "101") (name "Net-(D4R-A)") (class "Default")
      (node (ref "D4R") (pin "2") (pinfunction "A_2") (pintype "bidirectional"))
      (node (ref "J4") (pin "3") (pinfunction "3_3") (pintype "bidirectional"))
    )
    (net (code "102") (name "Net-(D4R-K)") (class "Default")
      (node (ref "D4R") (pin "1") (pinfunction "K_1") (pintype "bidirectional"))
      (node (ref "R4R") (pin "2") (pinfunction "2_2") (pintype "passive"))
      (node (ref "Z4R") (pin "1") (pinfunction "K_1") (pintype "bidirectional"))
    )
    (net (code "103") (name "Net-(D4T-A)") (class "Default")
      (node (ref "D4T") (pin "2") (pinfunction "A_2") (pintype "bidirectional"))
      (node (ref "J4") (pin "2") (pinfunction "2_2") (pintype "bidirectional"))
    )
    (net (code "104") (name "Net-(D4T-K)") (class "Default")
      (node (ref "D4T") (pin "1") (pinfunction "K_1") (pintype "bidirectional"))
      (node (ref "R4T") (pin "2") (pinfunction "2_2") (pintype "passive"))
      (node (ref "Z4T") (pin "1") (pinfunction "K_1") (pintype "bidirectional"))
    )
    (net (code "105") (name "Net-(D5T-A)") (class "Default")
      (node (ref "D5T") (pin "2") (pinfunction "A_2") (pintype "bidirectional"))
      (node (ref "J5") (pin "2") (pinfunction "2_2") (pintype "bidirectional"))
    )
    (net (code "106") (name "Net-(D5T-K)") (class "Default")
      (node (ref "D5T") (pin "1") (pinfunction "K_1") (pintype "bidirectional"))
      (node (ref "R5T") (pin "2") (pinfunction "2_2") (pintype "passive"))
      (node (ref "Z5T") (pin "1") (pinfunction "K_1") (pintype "bidirectional"))
    )
    (net (code "107") (name "Net-(D6T-A)") (class "Default")
      (node (ref "D6T") (pin "2") (pinfunction "A_2") (pintype "bidirectional"))
      (node (ref "J6") (pin "2") (pinfunction "2_2") (pintype "bidirectional"))
    )
    (net (code "108") (name "Net-(D6T-K)") (class "Default")
      (node (ref "D6T") (pin "1") (pinfunction "K_1") (pintype "bidirectional"))
      (node (ref "R6T") (pin "2") (pinfunction "2_2") (pintype "passive"))
      (node (ref "Z6T") (pin "1") (pinfunction "K_1") (pintype "bidirectional"))
    )
    (net (code "109") (name "Net-(D7T-A)") (class "Default")
      (node (ref "D7T") (pin "2") (pinfunction "A_2") (pintype "bidirectional"))
      (node (ref "J7") (pin "2") (pinfunction "2_2") (pintype "bidirectional"))
    )
    (net (code "110") (name "Net-(D7T-K)") (class "Default")
      (node (ref "D7T") (pin "1") (pinfunction "K_1") (pintype "bidirectional"))
      (node (ref "R7T") (pin "2") (pinfunction "2_2") (pintype "passive"))
      (node (ref "Z7T") (pin "1") (pinfunction "K_1") (pintype "bidirectional"))
    )
    (net (code "111") (name "Net-(D8T-A)") (class "Default")
      (node (ref "D8T") (pin "2") (pinfunction "A_2") (pintype "bidirectional"))
      (node (ref "J8") (pin "2") (pinfunction "2_2") (pintype "bidirectional"))
    )
    (net (code "112") (name "Net-(D8T-K)") (class "Default")
      (node (ref "D8T") (pin "1") (pinfunction "K_1") (pintype "bidirectional"))
      (node (ref "R8T") (pin "2") (pinfunction "2_2") (pintype "passive"))
      (node (ref "Z8T") (pin "1") (pinfunction "K_1") (pintype "bidirectional"))
    )
    (net (code "113") (name "Net-(IC1--VHPFILT)") (class "Default")
      (node (ref "C13") (pin "1") (pinfunction "1_1") (pintype "passive"))
      (node (ref "C14") (pin "1") (pinfunction "1_1") (pintype "passive"))
      (node (ref "IC1") (pin "10") (pinfunction "-VHPFILT_10") (pintype "bidirectional"))
    )
    (net (code "114") (name "Net-(IC1-AFILTA)") (class "Default")
      (node (ref "C3") (pin "1") (pinfunction "1_1") (pintype "passive"))
      (node (ref "IC1") (pin "27") (pinfunction "AFILTA_27") (pintype "bidirectional"))
    )
    (net (code "115") (name "Net-(IC1-AFILTB)") (class "Default")
      (node (ref "C4") (pin "1") (pinfunction "1_1") (pintype "passive"))
      (node (ref "IC1") (pin "28") (pinfunction "AFILTB_28") (pintype "bidirectional"))
    )
    (net (code "116") (name "Net-(IC1-AIN1A)") (class "Default")
      (node (ref "IC1") (pin "29") (pinfunction "AIN1A_29") (pintype "bidirectional"))
      (node (ref "R5") (pin "2") (pinfunction "2_2") (pintype "passive"))
    )
    (net (code "117") (name "Net-(IC1-AIN1B)") (class "Default")
      (node (ref "IC1") (pin "30") (pinfunction "AIN1B_30") (pintype "bidirectional"))
      (node (ref "R4") (pin "2") (pinfunction "2_2") (pintype "passive"))
    )
    (net (code "118") (name "Net-(IC1-AIN2A)") (class "Default")
      (node (ref "IC1") (pin "25") (pinfunction "AIN2A_25") (pintype "bidirectional"))
      (node (ref "R9") (pin "2") (pinfunction "2_2") (pintype "passive"))
    )
    (net (code "119") (name "Net-(IC1-AIN2B)") (class "Default")
      (node (ref "IC1") (pin "26") (pinfunction "AIN2B_26") (pintype "bidirectional"))
      (node (ref "R8") (pin "2") (pinfunction "2_2") (pintype "passive"))
    )
    (net (code "120") (name "Net-(IC1-AIN3A)") (class "Default")
      (node (ref "IC1") (pin "23") (pinfunction "AIN3A_23") (pintype "bidirectional"))
      (node (ref "R11") (pin "2") (pinfunction "2_2") (pintype "passive"))
    )
    (net (code "121") (name "Net-(IC1-AIN3B)") (class "Default")
      (node (ref "IC1") (pin "24") (pinfunction "AIN3B_24") (pintype "bidirectional"))
      (node (ref "R10") (pin "2") (pinfunction "2_2") (pintype "passive"))
    )
    (net (code "122") (name "Net-(IC1-AIN4A)") (class "Default")
      (node (ref "IC1") (pin "21") (pinfunction "AIN4A_21") (pintype "bidirectional"))
      (node (ref "R13") (pin "2") (pinfunction "2_2") (pintype "passive"))
    )
    (net (code "123") (name "Net-(IC1-AIN4B)") (class "Default")
      (node (ref "IC1") (pin "22") (pinfunction "AIN4B_22") (pintype "bidirectional"))
      (node (ref "R12") (pin "2") (pinfunction "2_2") (pintype "passive"))
    )
    (net (code "124") (name "Net-(IC1-FILT+)") (class "Default")
      (node (ref "C10") (pin "1") (pinfunction "1_1") (pintype "passive"))
      (node (ref "C8") (pin "1") (pinfunction "1_1") (pintype "passive"))
      (node (ref "C9") (pin "1") (pinfunction "1_1") (pintype "passive"))
      (node (ref "IC1") (pin "18") (pinfunction "FILT+_18") (pintype "bidirectional"))
    )
    (net (code "125") (name "Net-(IC1-FLYN)") (class "Default")
      (node (ref "C11") (pin "1") (pinfunction "1_1") (pintype "passive"))
      (node (ref "C12") (pin "1") (pinfunction "1_1") (pintype "passive"))
      (node (ref "IC1") (pin "11") (pinfunction "FLYN_11") (pintype "bidirectional"))
    )
    (net (code "126") (name "Net-(IC1-FLYP)") (class "Default")
      (node (ref "C11") (pin "2") (pinfunction "2_2") (pintype "passive"))
      (node (ref "C12") (pin "2") (pinfunction "2_2") (pintype "passive"))
      (node (ref "IC1") (pin "12") (pinfunction "FLYP_12") (pintype "bidirectional"))
    )
    (net (code "127") (name "Net-(IC1-HP{slash}LINE_OUTA)") (class "Default")
      (node (ref "C26") (pin "1") (pinfunction "1_1") (pintype "passive"))
      (node (ref "IC1") (pin "15") (pinfunction "HP/LINE_OUTA_15") (pintype "bidirectional"))
      (node (ref "JHP") (pin "3") (pinfunction "3_3") (pintype "bidirectional"))
      (node (ref "JOUT") (pin "2") (pinfunction "R_2") (pintype "bidirectional"))
    )
    (net (code "128") (name "Net-(IC1-HP{slash}LINE_OUTB)") (class "Default")
      (node (ref "C25") (pin "1") (pinfunction "1_1") (pintype "passive"))
      (node (ref "IC1") (pin "14") (pinfunction "HP/LINE_OUTB_14") (pintype "bidirectional"))
      (node (ref "JHP") (pin "2") (pinfunction "2_2") (pintype "bidirectional"))
      (node (ref "JOUT") (pin "3") (pinfunction "T_3") (pintype "bidirectional"))
    )
    (net (code "129") (name "Net-(IC1-SPKR_OUTA+)") (class "Default")
      (node (ref "IC1") (pin "4") (pinfunction "SPKR_OUTA+_4") (pintype "bidirectional"))
      (node (ref "X1") (pin "1") (pinfunction "1_1") (pintype "passive"))
    )
    (net (code "130") (name "Net-(IC1-SPKR_OUTA-)") (class "Default")
      (node (ref "IC1") (pin "6") (pinfunction "SPKR_OUTA-_6") (pintype "bidirectional"))
      (node (ref "X1") (pin "2") (pinfunction "1_2") (pintype "passive"))
    )
    (net (code "131") (name "Net-(IC1-SPKR_OUTB+)") (class "Default")
      (node (ref "IC1") (pin "7") (pinfunction "SPKR_OUTB+_7") (pintype "bidirectional"))
      (node (ref "X1") (pin "3") (pinfunction "1_3") (pintype "passive"))
    )
    (net (code "132") (name "Net-(IC1-SPKR_OUTB-)") (class "Default")
      (node (ref "IC1") (pin "9") (pinfunction "SPKR_OUTB-_9") (pintype "bidirectional"))
      (node (ref "X1") (pin "4") (pinfunction "1_4") (pintype "passive"))
    )
    (net (code "133") (name "Net-(IC1-VQ)") (class "Default")
      (node (ref "C5") (pin "1") (pinfunction "1_1") (pintype "passive"))
      (node (ref "C6") (pin "1") (pinfunction "1_1") (pintype "passive"))
      (node (ref "C7") (pin "1") (pinfunction "1_1") (pintype "passive"))
      (node (ref "IC1") (pin "19") (pinfunction "VQ_19") (pintype "bidirectional"))
    )
    (net (code "134") (name "Net-(IC2-BYPASS)") (class "Default")
      (node (ref "C59") (pin "2") (pinfunction "2_2") (pintype "passive"))
      (node (ref "IC2") (pin "4") (pinfunction "BYPASS_4") (pintype "bidirectional"))
    )
    (net (code "135") (name "Net-(IC3-BYPASS)") (class "Default")
      (node (ref "C54") (pin "2") (pinfunction "2_2") (pintype "passive"))
      (node (ref "IC3") (pin "4") (pinfunction "BYPASS_4") (pintype "bidirectional"))
    )
    (net (code "136") (name "Net-(IC4-SENSE)") (class "Default")
      (node (ref "IC4") (pin "3") (pinfunction "SENSE_3") (pintype "bidirectional"))
      (node (ref "R22") (pin "2") (pinfunction "2_2") (pintype "passive"))
      (node (ref "R32") (pin "1") (pinfunction "1_1") (pintype "passive"))
    )
    (net (code "137") (name "Net-(IC4-SS)") (class "Default")
      (node (ref "C63") (pin "1") (pinfunction "1_1") (pintype "passive"))
      (node (ref "IC4") (pin "4") (pinfunction "SS_4") (pintype "bidirectional"))
    )
    (net (code "138") (name "Net-(IC5-AINL)") (class "Default")
      (node (ref "IC5") (pin "19") (pinfunction "AINL_19") (pintype "bidirectional"))
      (node (ref "R28") (pin "2") (pinfunction "2_2") (pintype "passive"))
      (node (ref "R29") (pin "1") (pinfunction "1_1") (pintype "passive"))
    )
    (net (code "139") (name "Net-(IC5-AINOPL)") (class "Default")
      (node (ref "IC5") (pin "18") (pinfunction "AINOPL_18") (pintype "bidirectional"))
      (node (ref "R29") (pin "2") (pinfunction "2_2") (pintype "passive"))
    )
    (net (code "140") (name "Net-(IC5-AINOPR)") (class "Default")
      (node (ref "IC5") (pin "15") (pinfunction "AINOPR_15") (pintype "bidirectional"))
      (node (ref "R30") (pin "1") (pinfunction "1_1") (pintype "passive"))
    )
    (net (code "141") (name "Net-(IC5-AINR)") (class "Default")
      (node (ref "IC5") (pin "16") (pinfunction "AINR_16") (pintype "bidirectional"))
      (node (ref "R30") (pin "2") (pinfunction "2_2") (pintype "passive"))
      (node (ref "R31") (pin "2") (pinfunction "2_2") (pintype "passive"))
    )
    (net (code "142") (name "Net-(IC5-COM)") (class "Default")
      (node (ref "C2") (pin "1") (pinfunction "1_1") (pintype "passive"))
      (node (ref "IC5") (pin "17") (pinfunction "COM_17") (pintype "bidirectional"))
      (node (ref "R27") (pin "1") (pinfunction "1_1") (pintype "passive"))
    )
    (net (code "143") (name "Net-(IC5-FORMAT)") (class "Default")
      (node (ref "IC5") (pin "9") (pinfunction "FORMAT_9") (pintype "bidirectional"))
      (node (ref "R26") (pin "2") (pinfunction "2_2") (pintype "passive"))
    )
    (net (code "144") (name "Net-(IC5-FSAMPEN)") (class "Default")
      (node (ref "IC5") (pin "8") (pinfunction "FSAMPEN_8") (pintype "bidirectional"))
      (node (ref "R25") (pin "2") (pinfunction "2_2") (pintype "passive"))
    )
    (net (code "145") (name "Net-(IC5-IWL)") (class "Default")
      (node (ref "IC5") (pin "7") (pinfunction "IWL_7") (pintype "bidirectional"))
      (node (ref "R24") (pin "2") (pinfunction "2_2") (pintype "passive"))
    )
    (net (code "146") (name "Net-(IC5-M{slash}S)") (class "Default")
      (node (ref "IC5") (pin "20") (pinfunction "M/S_20") (pintype "bidirectional"))
      (node (ref "R23") (pin "1") (pinfunction "1_1") (pintype "passive"))
    )
    (net (code "147") (name "Net-(IC5-VREFP)") (class "Default")
      (node (ref "C43") (pin "1") (pinfunction "1_1") (pintype "passive"))
      (node (ref "C44") (pin "1") (pinfunction "1_1") (pintype "passive"))
      (node (ref "IC5") (pin "12") (pinfunction "VREFP_12") (pintype "bidirectional"))
    )
    (net (code "148") (name "Net-(IC6-BOOT0)") (class "Default")
      (node (ref "IC6") (pin "44") (pinfunction "BOOT0_44") (pintype "bidirectional"))
      (node (ref "R42") (pin "2") (pinfunction "2_2") (pintype "passive"))
    )
    (net (code "149") (name "Net-(IC6-PD0-OSC_IN)") (class "Default")
      (node (ref "C80") (pin "1") (pinfunction "1_1") (pintype "passive"))
      (node (ref "IC6") (pin "5") (pinfunction "PD0-OSC_IN_5") (pintype "bidirectional"))
      (node (ref "Q2") (pin "2") (pinfunction "2_2") (pintype "passive"))
    )
    (net (code "150") (name "Net-(IC6-PD1-OSC_OUT)") (class "Default")
      (node (ref "C81") (pin "1") (pinfunction "1_1") (pintype "passive"))
      (node (ref "IC6") (pin "6") (pinfunction "PD1-OSC_OUT_6") (pintype "bidirectional"))
      (node (ref "Q2") (pin "1") (pinfunction "1_1") (pintype "passive"))
    )
    (net (code "151") (name "Net-(IC6-VBAT)") (class "Default")
      (node (ref "C108") (pin "2") (pinfunction "2_2") (pintype "passive"))
      (node (ref "IC6") (pin "1") (pinfunction "VBAT_1") (pintype "bidirectional"))
    )
    (net (code "152") (name "Net-(IC7-VINA+)") (class "Default")
      (node (ref "C1R") (pin "1") (pinfunction "1_1") (pintype "passive"))
      (node (ref "IC7") (pin "3") (pinfunction "VINA+_3") (pintype "bidirectional"))
      (node (ref "R1R") (pin "1") (pinfunction "1_1") (pintype "passive"))
    )
    (net (code "153") (name "Net-(IC7-VINB+)") (class "Default")
      (node (ref "C1T") (pin "1") (pinfunction "1_1") (pintype "passive"))
      (node (ref "IC7") (pin "5") (pinfunction "VINB+_5") (pintype "bidirectional"))
      (node (ref "R1T") (pin "1") (pinfunction "1_1") (pintype "passive"))
    )
    (net (code "154") (name "Net-(IC7-VINC+)") (class "Default")
      (node (ref "C2R") (pin "1") (pinfunction "1_1") (pintype "passive"))
      (node (ref "IC7") (pin "10") (pinfunction "VINC+_10") (pintype "bidirectional"))
      (node (ref "R2R") (pin "1") (pinfunction "1_1") (pintype "passive"))
    )
    (net (code "155") (name "Net-(IC7-VIND+)") (class "Default")
      (node (ref "C2T") (pin "1") (pinfunction "1_1") (pintype "passive"))
      (node (ref "IC7") (pin "12") (pinfunction "VIND+_12") (pintype "bidirectional"))
      (node (ref "R2T") (pin "1") (pinfunction "1_1") (pintype "passive"))
    )
    (net (code "156") (name "Net-(IC8-NC{slash}FB)") (class "Default")
      (node (ref "C68") (pin "2") (pinfunction "2_2") (pintype "passive"))
      (node (ref "IC8") (pin "4") (pinfunction "NC/FB_4") (pintype "bidirectional"))
    )
    (net (code "157") (name "Net-(IC9-VINA+)") (class "Default")
      (node (ref "C3R") (pin "1") (pinfunction "1_1") (pintype "passive"))
      (node (ref "IC9") (pin "3") (pinfunction "VINA+_3") (pintype "bidirectional"))
      (node (ref "R3R") (pin "1") (pinfunction "1_1") (pintype "passive"))
    )
    (net (code "158") (name "Net-(IC9-VINB+)") (class "Default")
      (node (ref "C3T") (pin "1") (pinfunction "1_1") (pintype "passive"))
      (node (ref "IC9") (pin "5") (pinfunction "VINB+_5") (pintype "bidirectional"))
      (node (ref "R3T") (pin "1") (pinfunction "1_1") (pintype "passive"))
    )
    (net (code "159") (name "Net-(IC9-VINC+)") (class "Default")
      (node (ref "C4R") (pin "1") (pinfunction "1_1") (pintype "passive"))
      (node (ref "IC9") (pin "10") (pinfunction "VINC+_10") (pintype "bidirectional"))
      (node (ref "R4R") (pin "1") (pinfunction "1_1") (pintype "passive"))
    )
    (net (code "160") (name "Net-(IC9-VIND+)") (class "Default")
      (node (ref "C4T") (pin "1") (pinfunction "1_1") (pintype "passive"))
      (node (ref "IC9") (pin "12") (pinfunction "VIND+_12") (pintype "bidirectional"))
      (node (ref "R4T") (pin "1") (pinfunction "1_1") (pintype "passive"))
    )
    (net (code "161") (name "Net-(IC10-ADJ)") (class "Default")
      (node (ref "IC10") (pin "4") (pinfunction "ADJ_4") (pintype "bidirectional"))
      (node (ref "R18") (pin "2") (pinfunction "2_2") (pintype "passive"))
      (node (ref "R19") (pin "1") (pinfunction "1_1") (pintype "passive"))
    )
    (net (code "162") (name "Net-(IC11-SENSE)") (class "Default")
      (node (ref "IC11") (pin "3") (pinfunction "SENSE_3") (pintype "bidirectional"))
      (node (ref "R20") (pin "2") (pinfunction "2_2") (pintype "passive"))
      (node (ref "R21") (pin "1") (pinfunction "1_1") (pintype "passive"))
    )
    (net (code "163") (name "Net-(IC11-SS)") (class "Default")
      (node (ref "C37") (pin "1") (pinfunction "1_1") (pintype "passive"))
      (node (ref "IC11") (pin "4") (pinfunction "SS_4") (pintype "bidirectional"))
    )
    (net (code "164") (name "Net-(IC13-VINA+)") (class "Default")
      (node (ref "C5T") (pin "1") (pinfunction "1_1") (pintype "passive"))
      (node (ref "IC13") (pin "3") (pinfunction "VINA+_3") (pintype "bidirectional"))
      (node (ref "R5T") (pin "1") (pinfunction "1_1") (pintype "passive"))
    )
    (net (code "165") (name "Net-(IC13-VINB+)") (class "Default")
      (node (ref "C6T") (pin "1") (pinfunction "1_1") (pintype "passive"))
      (node (ref "IC13") (pin "5") (pinfunction "VINB+_5") (pintype "bidirectional"))
      (node (ref "R6T") (pin "1") (pinfunction "1_1") (pintype "passive"))
    )
    (net (code "166") (name "Net-(IC13-VINC+)") (class "Default")
      (node (ref "C7T") (pin "1") (pinfunction "1_1") (pintype "passive"))
      (node (ref "IC13") (pin "10") (pinfunction "VINC+_10") (pintype "bidirectional"))
      (node (ref "R7T") (pin "1") (pinfunction "1_1") (pintype "passive"))
    )
    (net (code "167") (name "Net-(IC13-VIND+)") (class "Default")
      (node (ref "C8T") (pin "1") (pinfunction "1_1") (pintype "passive"))
      (node (ref "IC13") (pin "12") (pinfunction "VIND+_12") (pintype "bidirectional"))
      (node (ref "R8T") (pin "1") (pinfunction "1_1") (pintype "passive"))
    )
    (net (code "168") (name "Net-(IC14-ADJ{slash}GND)") (class "Default")
      (node (ref "IC14") (pin "1") (pinfunction "ADJ/GND_1") (pintype "bidirectional"))
      (node (ref "R44") (pin "2") (pinfunction "2_2") (pintype "passive"))
    )
    (net (code "169") (name "Net-(J10-ID)") (class "Default")
      (node (ref "J10") (pin "4") (pinfunction "ID_4") (pintype "bidirectional"))
      (node (ref "R14") (pin "2") (pinfunction "2_2") (pintype "passive"))
    )
    (net (code "170") (name "Net-(LED10-PadA)") (class "Default")
      (node (ref "LED10") (pin "A") (pinfunction "A_A") (pintype "passive"))
      (node (ref "R56") (pin "2") (pinfunction "2_2") (pintype "passive"))
    )
    (net (code "171") (name "Net-(LED11-PadA)") (class "Default")
      (node (ref "LED11") (pin "A") (pinfunction "A_A") (pintype "passive"))
      (node (ref "R57") (pin "2") (pinfunction "2_2") (pintype "passive"))
    )
    (net (code "172") (name "Net-(LED12-PadA)") (class "Default")
      (node (ref "LED12") (pin "A") (pinfunction "A_A") (pintype "passive"))
      (node (ref "R58") (pin "2") (pinfunction "2_2") (pintype "passive"))
    )
    (net (code "173") (name "Net-(LEDA1-A)") (class "Default")
      (node (ref "LEDA1") (pin "2") (pinfunction "A_2") (pintype "bidirectional"))
      (node (ref "LEDB1") (pin "A") (pinfunction "A_A") (pintype "passive"))
      (node (ref "LEDC1") (pin "2") (pinfunction "A_2") (pintype "bidirectional"))
      (node (ref "LEDD1") (pin "A") (pinfunction "A_A") (pintype "passive"))
      (node (ref "RLED1") (pin "1") (pinfunction "1_1") (pintype "passive"))
    )
    (net (code "174") (name "Net-(LEDA3-A)") (class "Default")
      (node (ref "LEDA3") (pin "2") (pinfunction "A_2") (pintype "bidirectional"))
      (node (ref "LEDB3") (pin "A") (pinfunction "A_A") (pintype "passive"))
      (node (ref "LEDC3") (pin "2") (pinfunction "A_2") (pintype "bidirectional"))
      (node (ref "LEDD3") (pin "A") (pinfunction "A_A") (pintype "passive"))
      (node (ref "RLED3") (pin "1") (pinfunction "1_1") (pintype "passive"))
    )
    (net (code "175") (name "Net-(LEDA5-A)") (class "Default")
      (node (ref "LEDA5") (pin "2") (pinfunction "A_2") (pintype "bidirectional"))
      (node (ref "LEDB5") (pin "A") (pinfunction "A_A") (pintype "passive"))
      (node (ref "LEDC5") (pin "2") (pinfunction "A_2") (pintype "bidirectional"))
      (node (ref "LEDD5") (pin "A") (pinfunction "A_A") (pintype "passive"))
      (node (ref "RLED5") (pin "1") (pinfunction "1_1") (pintype "passive"))
    )
    (net (code "176") (name "Net-(LEDA7-A)") (class "Default")
      (node (ref "LEDA7") (pin "2") (pinfunction "A_2") (pintype "bidirectional"))
      (node (ref "LEDB7") (pin "A") (pinfunction "A_A") (pintype "passive"))
      (node (ref "LEDC7") (pin "2") (pinfunction "A_2") (pintype "bidirectional"))
      (node (ref "LEDD7") (pin "A") (pinfunction "A_A") (pintype "passive"))
      (node (ref "RLED7") (pin "1") (pinfunction "1_1") (pintype "passive"))
    )
    (net (code "177") (name "Net-(LEDA9-A)") (class "Default")
      (node (ref "LEDA9") (pin "2") (pinfunction "A_2") (pintype "bidirectional"))
      (node (ref "LEDB9") (pin "A") (pinfunction "A_A") (pintype "passive"))
      (node (ref "LEDC9") (pin "2") (pinfunction "A_2") (pintype "bidirectional"))
      (node (ref "LEDD9") (pin "A") (pinfunction "A_A") (pintype "passive"))
      (node (ref "RLED9") (pin "1") (pinfunction "1_1") (pintype "passive"))
    )
    (net (code "178") (name "Net-(LEDA11-A)") (class "Default")
      (node (ref "LEDA11") (pin "2") (pinfunction "A_2") (pintype "bidirectional"))
      (node (ref "LEDB11") (pin "A") (pinfunction "A_A") (pintype "passive"))
      (node (ref "LEDC11") (pin "2") (pinfunction "A_2") (pintype "bidirectional"))
      (node (ref "LEDD11") (pin "A") (pinfunction "A_A") (pintype "passive"))
      (node (ref "RLED11") (pin "1") (pinfunction "1_1") (pintype "passive"))
    )
    (net (code "179") (name "Net-(LEDA13-A)") (class "Default")
      (node (ref "LEDA13") (pin "2") (pinfunction "A_2") (pintype "bidirectional"))
      (node (ref "LEDB13") (pin "A") (pinfunction "A_A") (pintype "passive"))
      (node (ref "LEDC13") (pin "2") (pinfunction "A_2") (pintype "bidirectional"))
      (node (ref "LEDD13") (pin "A") (pinfunction "A_A") (pintype "passive"))
      (node (ref "RLED13") (pin "1") (pinfunction "1_1") (pintype "passive"))
    )
    (net (code "180") (name "Net-(LEDA15-A)") (class "Default")
      (node (ref "LEDA15") (pin "2") (pinfunction "A_2") (pintype "bidirectional"))
      (node (ref "LEDB15") (pin "A") (pinfunction "A_A") (pintype "passive"))
      (node (ref "LEDC15") (pin "2") (pinfunction "A_2") (pintype "bidirectional"))
      (node (ref "LEDD15") (pin "A") (pinfunction "A_A") (pintype "passive"))
      (node (ref "RLED15") (pin "1") (pinfunction "1_1") (pintype "passive"))
    )
    (net (code "181") (name "Net-(LEDA17-A)") (class "Default")
      (node (ref "LEDA17") (pin "2") (pinfunction "A_2") (pintype "bidirectional"))
      (node (ref "LEDB17") (pin "A") (pinfunction "A_A") (pintype "passive"))
      (node (ref "LEDC17") (pin "2") (pinfunction "A_2") (pintype "bidirectional"))
      (node (ref "LEDD17") (pin "A") (pinfunction "A_A") (pintype "passive"))
      (node (ref "RLED17") (pin "1") (pinfunction "1_1") (pintype "passive"))
    )
    (net (code "182") (name "Net-(R7-Pad2)") (class "Default")
      (node (ref "R7") (pin "2") (pinfunction "2_2") (pintype "passive"))
      (node (ref "U$2") (pin "LED") (pinfunction "LED_LED") (pintype "bidirectional"))
    )
    (net (code "183") (name "Net-(R43-Pad2)") (class "Default")
      (node (ref "R43") (pin "2") (pinfunction "2_2") (pintype "passive"))
      (node (ref "R48") (pin "2") (pinfunction "2_2") (pintype "passive"))
      (node (ref "R7") (pin "1") (pinfunction "1_1") (pintype "passive"))
      (node (ref "U$2") (pin "VDD") (pinfunction "VDD_VDD") (pintype "bidirectional"))
    )
    (net (code "184") (name "Net-(U1A-PB14)") (class "Default")
      (node (ref "R64") (pin "2") (pinfunction "2_2") (pintype "passive"))
      (node (ref "U1") (pin "53") (pinfunction "PB14_53") (pintype "bidirectional"))
    )
    (net (code "185") (name "Net-(U1B-BOOT0)") (class "Default")
      (node (ref "R41") (pin "1") (pinfunction "1_1") (pintype "passive"))
      (node (ref "U1") (pin "94") (pinfunction "BOOT0_94") (pintype "input"))
    )
    (net (code "186") (name "Net-(U1B-PH0{slash}OSC_IN)") (class "Default")
      (node (ref "C78") (pin "1") (pinfunction "1_1") (pintype "passive"))
      (node (ref "Q1") (pin "2") (pinfunction "2_2") (pintype "passive"))
      (node (ref "U1") (pin "12") (pinfunction "PH0/OSC_IN_12") (pintype "bidirectional"))
    )
    (net (code "187") (name "Net-(U1B-PH1{slash}OSC_OUT)") (class "Default")
      (node (ref "C79") (pin "1") (pinfunction "1_1") (pintype "passive"))
      (node (ref "Q1") (pin "1") (pinfunction "1_1") (pintype "passive"))
      (node (ref "U1") (pin "13") (pinfunction "PH1/OSC_OUT_13") (pintype "bidirectional"))
    )
    (net (code "188") (name "Net-(U1C-VBAT)") (class "Default")
      (node (ref "C92") (pin "2") (pinfunction "2_2") (pintype "passive"))
      (node (ref "U1") (pin "6") (pinfunction "VBAT_6") (pintype "power_in"))
    )
    (net (code "189") (name "Net-(U1C-VCAP_1)") (class "Default")
      (node (ref "C91") (pin "2") (pinfunction "2_2") (pintype "passive"))
      (node (ref "U1") (pin "49") (pinfunction "VCAP_1_49") (pintype "power_in"))
    )
    (net (code "190") (name "Net-(U1C-VCAP_2)") (class "Default")
      (node (ref "C90") (pin "2") (pinfunction "2_2") (pintype "passive"))
      (node (ref "U1") (pin "73") (pinfunction "VCAP_2_73") (pintype "power_in"))
    )
    (net (code "191") (name "Net-(U1C-VDDA)") (class "Default")
      (node (ref "C93") (pin "1") (pinfunction "1_1") (pintype "passive"))
      (node (ref "C94") (pin "1") (pinfunction "1_1") (pintype "passive"))
      (node (ref "L4") (pin "1") (pinfunction "1_1") (pintype "passive"))
      (node (ref "R45") (pin "1") (pinfunction "1_1") (pintype "passive"))
      (node (ref "U1") (pin "22") (pinfunction "VDDA_22") (pintype "power_in"))
    )
    (net (code "192") (name "Net-(U1C-VREF+)") (class "Default")
      (node (ref "C95") (pin "1") (pinfunction "1_1") (pintype "passive"))
      (node (ref "C96") (pin "1") (pinfunction "1_1") (pintype "passive"))
      (node (ref "R45") (pin "2") (pinfunction "2_2") (pintype "passive"))
      (node (ref "U1") (pin "21") (pinfunction "VREF+_21") (pintype "power_in"))
    )
    (net (code "193") (name "Net-(Z5R-K)") (class "Default")
      (node (ref "J5") (pin "3") (pinfunction "3_3") (pintype "bidirectional"))
      (node (ref "R5R") (pin "2") (pinfunction "2_2") (pintype "passive"))
      (node (ref "R5RU") (pin "2") (pinfunction "2_2") (pintype "passive"))
      (node (ref "Z5R") (pin "1") (pinfunction "K_1") (pintype "bidirectional"))
    )
    (net (code "194") (name "Net-(Z6R-K)") (class "Default")
      (node (ref "J6") (pin "3") (pinfunction "3_3") (pintype "bidirectional"))
      (node (ref "R6R") (pin "2") (pinfunction "2_2") (pintype "passive"))
      (node (ref "R6RU") (pin "2") (pinfunction "2_2") (pintype "passive"))
      (node (ref "Z6R") (pin "1") (pinfunction "K_1") (pintype "bidirectional"))
    )
    (net (code "195") (name "Net-(Z7R-K)") (class "Default")
      (node (ref "J7") (pin "3") (pinfunction "3_3") (pintype "bidirectional"))
      (node (ref "R7R") (pin "2") (pinfunction "2_2") (pintype "passive"))
      (node (ref "R7RU") (pin "2") (pinfunction "2_2") (pintype "passive"))
      (node (ref "Z7R") (pin "1") (pinfunction "K_1") (pintype "bidirectional"))
    )
    (net (code "196") (name "Net-(Z8R-K)") (class "Default")
      (node (ref "J8") (pin "3") (pinfunction "3_3") (pintype "bidirectional"))
      (node (ref "R8R") (pin "2") (pinfunction "2_2") (pintype "passive"))
      (node (ref "R8RU") (pin "2") (pinfunction "2_2") (pintype "passive"))
      (node (ref "Z8R") (pin "1") (pinfunction "K_1") (pintype "bidirectional"))
    )
    (net (code "197") (name "Net-(Z9R-K)") (class "Default")
      (node (ref "J9") (pin "3") (pinfunction "3_3") (pintype "bidirectional"))
      (node (ref "R9R") (pin "2") (pinfunction "2_2") (pintype "passive"))
      (node (ref "R9RU") (pin "2") (pinfunction "2_2") (pintype "passive"))
      (node (ref "Z9R") (pin "1") (pinfunction "K_1") (pintype "bidirectional"))
    )
    (net (code "198") (name "Net-(Z9T-K)") (class "Default")
      (node (ref "J9") (pin "2") (pinfunction "2_2") (pintype "bidirectional"))
      (node (ref "R9T") (pin "2") (pinfunction "2_2") (pintype "passive"))
      (node (ref "R9TU") (pin "2") (pinfunction "2_2") (pintype "passive"))
      (node (ref "Z9T") (pin "1") (pinfunction "K_1") (pintype "bidirectional"))
    )
    (net (code "199") (name "OUT1A") (class "Default")
      (node (ref "IC7") (pin "6") (pinfunction "VINB-_6") (pintype "bidirectional"))
      (node (ref "IC7") (pin "7") (pinfunction "VOUTB_7") (pintype "bidirectional"))
      (node (ref "U1") (pin "17") (pinfunction "PC2_17") (pintype "bidirectional"))
    )
    (net (code "200") (name "OUT1B") (class "Default")
      (node (ref "IC7") (pin "1") (pinfunction "VOUTA_1") (pintype "bidirectional"))
      (node (ref "IC7") (pin "2") (pinfunction "VINA-_2") (pintype "bidirectional"))
      (node (ref "U1") (pin "16") (pinfunction "PC1_16") (pintype "bidirectional"))
    )
    (net (code "201") (name "OUT2A") (class "Default")
      (node (ref "IC7") (pin "13") (pinfunction "VIND-_13") (pintype "bidirectional"))
      (node (ref "IC7") (pin "14") (pinfunction "VOUTD_14") (pintype "bidirectional"))
      (node (ref "U1") (pin "18") (pinfunction "PC3_18") (pintype "bidirectional"))
    )
    (net (code "202") (name "OUT2B") (class "Default")
      (node (ref "IC7") (pin "8") (pinfunction "VOUTC_8") (pintype "bidirectional"))
      (node (ref "IC7") (pin "9") (pinfunction "VINC-_9") (pintype "bidirectional"))
      (node (ref "U1") (pin "23") (pinfunction "PA0/WKUP_23") (pintype "bidirectional"))
    )
    (net (code "203") (name "OUT3A") (class "Default")
      (node (ref "IC9") (pin "6") (pinfunction "VINB-_6") (pintype "bidirectional"))
      (node (ref "IC9") (pin "7") (pinfunction "VOUTB_7") (pintype "bidirectional"))
      (node (ref "U1") (pin "25") (pinfunction "PA2_25") (pintype "bidirectional"))
    )
    (net (code "204") (name "OUT3B") (class "Default")
      (node (ref "IC9") (pin "1") (pinfunction "VOUTA_1") (pintype "bidirectional"))
      (node (ref "IC9") (pin "2") (pinfunction "VINA-_2") (pintype "bidirectional"))
      (node (ref "U1") (pin "24") (pinfunction "PA1_24") (pintype "bidirectional"))
    )
    (net (code "205") (name "OUT4A") (class "Default")
      (node (ref "IC9") (pin "13") (pinfunction "VIND-_13") (pintype "bidirectional"))
      (node (ref "IC9") (pin "14") (pinfunction "VOUTD_14") (pintype "bidirectional"))
      (node (ref "U1") (pin "29") (pinfunction "PA4_29") (pintype "bidirectional"))
    )
    (net (code "206") (name "OUT4B") (class "Default")
      (node (ref "IC9") (pin "8") (pinfunction "VOUTC_8") (pintype "bidirectional"))
      (node (ref "IC9") (pin "9") (pinfunction "VINC-_9") (pintype "bidirectional"))
      (node (ref "U1") (pin "26") (pinfunction "PA3_26") (pintype "bidirectional"))
    )
    (net (code "207") (name "OUT5A") (class "Default")
      (node (ref "IC13") (pin "1") (pinfunction "VOUTA_1") (pintype "bidirectional"))
      (node (ref "IC13") (pin "2") (pinfunction "VINA-_2") (pintype "bidirectional"))
      (node (ref "U1") (pin "31") (pinfunction "PA6_31") (pintype "bidirectional"))
    )
    (net (code "208") (name "OUT5B") (class "Default")
      (node (ref "C5R") (pin "1") (pinfunction "1_1") (pintype "passive"))
      (node (ref "R5R") (pin "1") (pinfunction "1_1") (pintype "passive"))
      (node (ref "U1") (pin "41") (pinfunction "PE10_41") (pintype "bidirectional"))
    )
    (net (code "209") (name "OUT6A") (class "Default")
      (node (ref "IC13") (pin "6") (pinfunction "VINB-_6") (pintype "bidirectional"))
      (node (ref "IC13") (pin "7") (pinfunction "VOUTB_7") (pintype "bidirectional"))
      (node (ref "U1") (pin "30") (pinfunction "PA5_30") (pintype "bidirectional"))
    )
    (net (code "210") (name "OUT6B") (class "Default")
      (node (ref "C6R") (pin "1") (pinfunction "1_1") (pintype "passive"))
      (node (ref "R6R") (pin "1") (pinfunction "1_1") (pintype "passive"))
      (node (ref "U1") (pin "42") (pinfunction "PE11_42") (pintype "bidirectional"))
    )
    (net (code "211") (name "OUT7A") (class "Default")
      (node (ref "IC13") (pin "8") (pinfunction "VOUTC_8") (pintype "bidirectional"))
      (node (ref "IC13") (pin "9") (pinfunction "VINC-_9") (pintype "bidirectional"))
      (node (ref "U1") (pin "33") (pinfunction "PC4_33") (pintype "bidirectional"))
    )
    (net (code "212") (name "OUT7B") (class "Default")
      (node (ref "C7R") (pin "1") (pinfunction "1_1") (pintype "passive"))
      (node (ref "R7R") (pin "1") (pinfunction "1_1") (pintype "passive"))
      (node (ref "U1") (pin "43") (pinfunction "PE12_43") (pintype "bidirectional"))
    )
    (net (code "213") (name "OUT8A") (class "Default")
      (node (ref "IC13") (pin "13") (pinfunction "VIND-_13") (pintype "bidirectional"))
      (node (ref "IC13") (pin "14") (pinfunction "VOUTD_14") (pintype "bidirectional"))
      (node (ref "U1") (pin "32") (pinfunction "PA7_32") (pintype "bidirectional"))
    )
    (net (code "214") (name "OUT8B") (class "Default")
      (node (ref "C8R") (pin "1") (pinfunction "1_1") (pintype "passive"))
      (node (ref "R8R") (pin "1") (pinfunction "1_1") (pintype "passive"))
      (node (ref "U1") (pin "44") (pinfunction "PE13_44") (pintype "bidirectional"))
    )
    (net (code "215") (name "OUT9A") (class "Default")
      (node (ref "C9T") (pin "1") (pinfunction "1_1") (pintype "passive"))
      (node (ref "R9T") (pin "1") (pinfunction "1_1") (pintype "passive"))
      (node (ref "U1") (pin "45") (pinfunction "PE14_45") (pintype "bidirectional"))
    )
    (net (code "216") (name "OUT9B") (class "Default")
      (node (ref "C9R") (pin "1") (pinfunction "1_1") (pintype "passive"))
      (node (ref "R9R") (pin "1") (pinfunction "1_1") (pintype "passive"))
      (node (ref "U1") (pin "46") (pinfunction "PE15_46") (pintype "bidirectional"))
    )
    (net (code "217") (name "PD8") (class "Default")
      (node (ref "U1") (pin "55") (pinfunction "PD8_55") (pintype "bidirectional"))
      (node (ref "X4") (pin "1") (pinfunction "1_1") (pintype "passive"))
    )
    (net (code "218") (name "PD9") (class "Default")
      (node (ref "U1") (pin "56") (pinfunction "PD9_56") (pintype "bidirectional"))
      (node (ref "X4") (pin "2") (pinfunction "1_2") (pintype "passive"))
    )
    (net (code "219") (name "PD10") (class "Default")
      (node (ref "U1") (pin "57") (pinfunction "PD10_57") (pintype "bidirectional"))
      (node (ref "X4") (pin "3") (pinfunction "1_3") (pintype "passive"))
    )
    (net (code "220") (name "PD11") (class "Default")
      (node (ref "U1") (pin "58") (pinfunction "PD11_58") (pintype "bidirectional"))
      (node (ref "X4") (pin "4") (pinfunction "1_4") (pintype "passive"))
    )
    (net (code "221") (name "PD12") (class "Default")
      (node (ref "U1") (pin "59") (pinfunction "PD12_59") (pintype "bidirectional"))
      (node (ref "X4") (pin "5") (pinfunction "1_5") (pintype "passive"))
    )
    (net (code "222") (name "PD13") (class "Default")
      (node (ref "U1") (pin "60") (pinfunction "PD13_60") (pintype "bidirectional"))
      (node (ref "X4") (pin "6") (pinfunction "1_6") (pintype "passive"))
    )
    (net (code "223") (name "PD14") (class "Default")
      (node (ref "U1") (pin "61") (pinfunction "PD14_61") (pintype "bidirectional"))
      (node (ref "X4") (pin "7") (pinfunction "1_7") (pintype "passive"))
    )
    (net (code "224") (name "PD15") (class "Default")
      (node (ref "U1") (pin "62") (pinfunction "PD15_62") (pintype "bidirectional"))
      (node (ref "X4") (pin "8") (pinfunction "1_8") (pintype "passive"))
    )
    (net (code "225") (name "RAM2_CS") (class "Default")
      (node (ref "U$2") (pin "CS_F") (pinfunction "F_CS_CS_F") (pintype "bidirectional"))
      (node (ref "U1") (pin "81") (pinfunction "PD0_81") (pintype "bidirectional"))
    )
    (net (code "226") (name "RAM_CS") (class "Default")
      (node (ref "IC12") (pin "1") (pinfunction "~{CS}_1") (pintype "bidirectional"))
      (node (ref "U1") (pin "82") (pinfunction "PD1_82") (pintype "bidirectional"))
    )
    (net (code "227") (name "SD2_CS") (class "Default")
      (node (ref "U$2") (pin "CS_SD") (pinfunction "SD_CS_CS_SD") (pintype "bidirectional"))
      (node (ref "U1") (pin "83") (pinfunction "PD2_83") (pintype "bidirectional"))
    )
    (net (code "228") (name "SD_CS") (class "Default")
      (node (ref "J12") (pin "1") (pinfunction "CD/DAT3_1") (pintype "bidirectional"))
      (node (ref "U1") (pin "79") (pinfunction "PC11_79") (pintype "bidirectional"))
    )
    (net (code "229") (name "SPKR{slash}HP") (class "Default")
      (node (ref "IC1") (pin "31") (pinfunction "SPKR/HP_31") (pintype "bidirectional"))
      (node (ref "R3") (pin "1") (pinfunction "1_1") (pintype "passive"))
      (node (ref "R64") (pin "1") (pinfunction "1_1") (pintype "passive"))
      (node (ref "X2") (pin "2") (pinfunction "1_2") (pintype "passive"))
    )
    (net (code "230") (name "TFT_CS") (class "Default")
      (node (ref "IC6") (pin "38") (pinfunction "PA15_38") (pintype "bidirectional"))
      (node (ref "U$2") (pin "CS") (pinfunction "CS_CS") (pintype "bidirectional"))
    )
    (net (code "231") (name "TFT_DC") (class "Default")
      (node (ref "IC6") (pin "46") (pinfunction "PB9_46") (pintype "bidirectional"))
      (node (ref "U$2") (pin "DC") (pinfunction "DC_DC") (pintype "bidirectional"))
    )
    (net (code "232") (name "TFT_RST") (class "Default")
      (node (ref "IC6") (pin "45") (pinfunction "PB8_45") (pintype "bidirectional"))
      (node (ref "U$2") (pin "RST") (pinfunction "RST_RST") (pintype "bidirectional"))
    )
    (net (code "233") (name "UART1_RX") (class "Default")
      (node (ref "IC6") (pin "31") (pinfunction "PA10_31") (pintype "bidirectional"))
      (node (ref "U1") (pin "47") (pinfunction "PB10_47") (pintype "bidirectional"))
    )
    (net (code "234") (name "UART1_TX") (class "Default")
      (node (ref "IC6") (pin "30") (pinfunction "PA9_30") (pintype "bidirectional"))
      (node (ref "U1") (pin "48") (pinfunction "PB11_48") (pintype "bidirectional"))
    )
    (net (code "235") (name "UART3_RX") (class "Default")
      (node (ref "IC6") (pin "22") (pinfunction "PB11_22") (pintype "bidirectional"))
      (node (ref "U1") (pin "92") (pinfunction "PB6_92") (pintype "bidirectional"))
    )
    (net (code "236") (name "UART3_TX") (class "Default")
      (node (ref "IC6") (pin "21") (pinfunction "PB10_21") (pintype "bidirectional"))
      (node (ref "U1") (pin "93") (pinfunction "PB7_93") (pintype "bidirectional"))
    )
    (net (code "237") (name "USBV_EN") (class "Default")
      (node (ref "R6") (pin "2") (pinfunction "2_2") (pintype "passive"))
      (node (ref "S10") (pin "4") (pinfunction "EN_4") (pintype "bidirectional"))
      (node (ref "U1") (pin "66") (pinfunction "PC9_66") (pintype "bidirectional"))
    )
    (net (code "238") (name "USBV_FAULT") (class "Default")
      (node (ref "S10") (pin "3") (pinfunction "FAULT_3") (pintype "bidirectional"))
      (node (ref "U1") (pin "67") (pinfunction "PA8_67") (pintype "bidirectional"))
    )
    (net (code "239") (name "USB_D+") (class "Default")
      (node (ref "U1") (pin "71") (pinfunction "PA12_71") (pintype "bidirectional"))
      (node (ref "USBHA") (pin "3") (pinfunction "D+_3") (pintype "bidirectional"))
      (node (ref "USBHB") (pin "3") (pinfunction "D+_3") (pintype "bidirectional"))
    )
    (net (code "240") (name "USB_D-") (class "Default")
      (node (ref "U1") (pin "70") (pinfunction "PA11_70") (pintype "bidirectional"))
      (node (ref "USBHA") (pin "2") (pinfunction "D-_2") (pintype "bidirectional"))
      (node (ref "USBHB") (pin "2") (pinfunction "D-_2") (pintype "bidirectional"))
    )
    (net (code "241") (name "USB_ID") (class "Default")
      (node (ref "U1") (pin "69") (pinfunction "PA10_69") (pintype "bidirectional"))
      (node (ref "USBHA") (pin "4") (pinfunction "ID_4") (pintype "bidirectional"))
    )
    (net (code "242") (name "VBUS_FS") (class "Default")
      (node (ref "C74") (pin "1") (pinfunction "1_1") (pintype "passive"))
      (node (ref "R56") (pin "1") (pinfunction "1_1") (pintype "passive"))
      (node (ref "S10") (pin "1") (pinfunction "OUT_1") (pintype "bidirectional"))
      (node (ref "U1") (pin "68") (pinfunction "PA9_68") (pintype "bidirectional"))
      (node (ref "USBHA") (pin "1") (pinfunction "VCC_1") (pintype "power_in"))
      (node (ref "USBHB") (pin "1") (pinfunction "VDD_1") (pintype "bidirectional"))
    )
    (net (code "243") (name "VIN") (class "Default")
      (node (ref "C34") (pin "2") (pinfunction "2_2") (pintype "passive"))
      (node (ref "C38") (pin "1") (pinfunction "1_1") (pintype "passive"))
      (node (ref "C64") (pin "1") (pinfunction "1_1") (pintype "passive"))
      (node (ref "C89") (pin "+") (pinfunction "+_+") (pintype "passive"))
      (node (ref "D1R1") (pin "1") (pinfunction "K_1") (pintype "bidirectional"))
      (node (ref "IC10") (pin "1") (pinfunction "VIN_1") (pintype "bidirectional"))
      (node (ref "IC10") (pin "3") (pinfunction "EN_3") (pintype "bidirectional"))
      (node (ref "IC11") (pin "5") (pinfunction "EN_5") (pintype "bidirectional"))
      (node (ref "IC11") (pin "7") (pinfunction "VIN_1_7") (pintype "bidirectional"))
      (node (ref "IC11") (pin "8") (pinfunction "VIN_2_8") (pintype "bidirectional"))
      (node (ref "IC14") (pin "2") (pinfunction "OUT_2") (pintype "bidirectional"))
      (node (ref "IC14") (pin "4") (pinfunction "VOUT_4") (pintype "bidirectional"))
      (node (ref "IC4") (pin "5") (pinfunction "EN_5") (pintype "bidirectional"))
      (node (ref "IC4") (pin "7") (pinfunction "VIN_1_7") (pintype "bidirectional"))
      (node (ref "IC4") (pin "8") (pinfunction "VIN_2_8") (pintype "bidirectional"))
      (node (ref "R48") (pin "1") (pinfunction "1_1") (pintype "passive"))
      (node (ref "S10") (pin "5") (pinfunction "IN_5") (pintype "bidirectional"))
    )
    (net (code "244") (name "VMID") (class "Default")
      (node (ref "C41") (pin "1") (pinfunction "1_1") (pintype "passive"))
      (node (ref "C42") (pin "1") (pinfunction "1_1") (pintype "passive"))
      (node (ref "IC5") (pin "10") (pinfunction "VMID_10") (pintype "bidirectional"))
      (node (ref "R27") (pin "2") (pinfunction "2_2") (pintype "passive"))
    )
    (net (code "245") (name "unconnected-(IC1-TSTO_1-Pad20)") (class "Default")
      (node (ref "IC1") (pin "20") (pinfunction "TSTO_1_20") (pintype "bidirectional"))
    )
    (net (code "246") (name "unconnected-(IC1-TSTO_2-Pad36)") (class "Default")
      (node (ref "IC1") (pin "36") (pinfunction "TSTO_2_36") (pintype "bidirectional"))
    )
    (net (code "247") (name "unconnected-(J12-DAT1-Pad8)") (class "Default")
      (node (ref "J12") (pin "8") (pinfunction "DAT1_8") (pintype "bidirectional"))
    )
    (net (code "248") (name "unconnected-(J12-DAT2-Pad9)") (class "Default")
      (node (ref "J12") (pin "9") (pinfunction "DAT2_9") (pintype "bidirectional"))
    )
    (net (code "249") (name "unconnected-(J12-Pad10)") (class "Default")
      (node (ref "J12") (pin "10") (pinfunction "10_10") (pintype "bidirectional"))
    )
    (net (code "250") (name "unconnected-(J12-Pad11)") (class "Default")
      (node (ref "J12") (pin "11") (pinfunction "11_11") (pintype "bidirectional"))
    )
    (net (code "251") (name "unconnected-(J13-Pad1)") (class "Default")
      (node (ref "J13") (pin "1") (pinfunction "1_1") (pintype "bidirectional"))
    )
    (net (code "252") (name "unconnected-(J13-Pad6)") (class "Default")
      (node (ref "J13") (pin "6") (pinfunction "6_6") (pintype "bidirectional"))
    )
    (net (code "253") (name "unconnected-(J13-Pad7)") (class "Default")
      (node (ref "J13") (pin "7") (pinfunction "7_7") (pintype "bidirectional"))
    )
    (net (code "254") (name "unconnected-(J13-Pad8)") (class "Default")
      (node (ref "J13") (pin "8") (pinfunction "8_8") (pintype "bidirectional"))
    )
    (net (code "255") (name "unconnected-(J14-Pad1)") (class "Default")
      (node (ref "J14") (pin "1") (pinfunction "1_1") (pintype "bidirectional"))
    )
    (net (code "256") (name "unconnected-(J14-Pad6)") (class "Default")
      (node (ref "J14") (pin "6") (pinfunction "6_6") (pintype "bidirectional"))
    )
    (net (code "257") (name "unconnected-(J14-Pad7)") (class "Default")
      (node (ref "J14") (pin "7") (pinfunction "7_7") (pintype "bidirectional"))
    )
    (net (code "258") (name "unconnected-(J14-Pad8)") (class "Default")
      (node (ref "J14") (pin "8") (pinfunction "8_8") (pintype "bidirectional"))
    )
    (net (code "259") (name "unconnected-(R61-Pad1)") (class "Default")
      (node (ref "R61") (pin "1") (pinfunction "1_1") (pintype "passive"))
    )
    (net (code "260") (name "unconnected-(U1A-PB2{slash}BOOT1-Pad37)") (class "Default")
      (node (ref "U1") (pin "37") (pinfunction "PB2/BOOT1_37") (pintype "bidirectional"))
    )
    (net (code "261") (name "unconnected-(U1A-PC13-Pad7)") (class "Default")
      (node (ref "U1") (pin "7") (pinfunction "PC13_7") (pintype "bidirectional"))
    )
    (net (code "262") (name "unconnected-(U1A-PC14{slash}OSC32_IN-Pad8)") (class "Default")
      (node (ref "U1") (pin "8") (pinfunction "PC14/OSC32_IN_8") (pintype "bidirectional"))
    )
    (net (code "263") (name "unconnected-(U1A-PC15{slash}OSC32_OUT-Pad9)") (class "Default")
      (node (ref "U1") (pin "9") (pinfunction "PC15/OSC32_OUT_9") (pintype "bidirectional"))
    )
    (net (code "264") (name "unconnected-(U1A-PD7-Pad88)") (class "Default")
      (node (ref "U1") (pin "88") (pinfunction "PD7_88") (pintype "bidirectional"))
    )
    (net (code "265") (name "unconnected-(U1B-PE0-Pad97)") (class "Default")
      (node (ref "U1") (pin "97") (pinfunction "PE0_97") (pintype "bidirectional"))
    )
    (net (code "266") (name "unconnected-(U1B-PE1-Pad98)") (class "Default")
      (node (ref "U1") (pin "98") (pinfunction "PE1_98") (pintype "bidirectional"))
    )
    (net (code "267") (name "unconnected-(U1B-PE2-Pad1)") (class "Default")
      (node (ref "U1") (pin "1") (pinfunction "PE2_1") (pintype "bidirectional"))
    )
    (net (code "268") (name "unconnected-(U1B-PE3-Pad2)") (class "Default")
      (node (ref "U1") (pin "2") (pinfunction "PE3_2") (pintype "bidirectional"))
    )
    (net (code "269") (name "unconnected-(U1B-PE4-Pad3)") (class "Default")
      (node (ref "U1") (pin "3") (pinfunction "PE4_3") (pintype "bidirectional"))
    )
    (net (code "270") (name "unconnected-(U1B-PE5-Pad4)") (class "Default")
      (node (ref "U1") (pin "4") (pinfunction "PE5_4") (pintype "bidirectional"))
    )
    (net (code "271") (name "unconnected-(U1B-PE6-Pad5)") (class "Default")
      (node (ref "U1") (pin "5") (pinfunction "PE6_5") (pintype "bidirectional"))
    )
    (net (code "272") (name "unconnected-(U1B-PE7-Pad38)") (class "Default")
      (node (ref "U1") (pin "38") (pinfunction "PE7_38") (pintype "bidirectional"))
    )
    (net (code "273") (name "unconnected-(U1B-PE8-Pad39)") (class "Default")
      (node (ref "U1") (pin "39") (pinfunction "PE8_39") (pintype "bidirectional"))
    )
    (net (code "274") (name "unconnected-(U1B-PE9-Pad40)") (class "Default")
      (node (ref "U1") (pin "40") (pinfunction "PE9_40") (pintype "bidirectional"))
    )
  )
)
